# Jupiter_Ace_build026.net
KiCad netlist of a schematic drawn in EAGLE
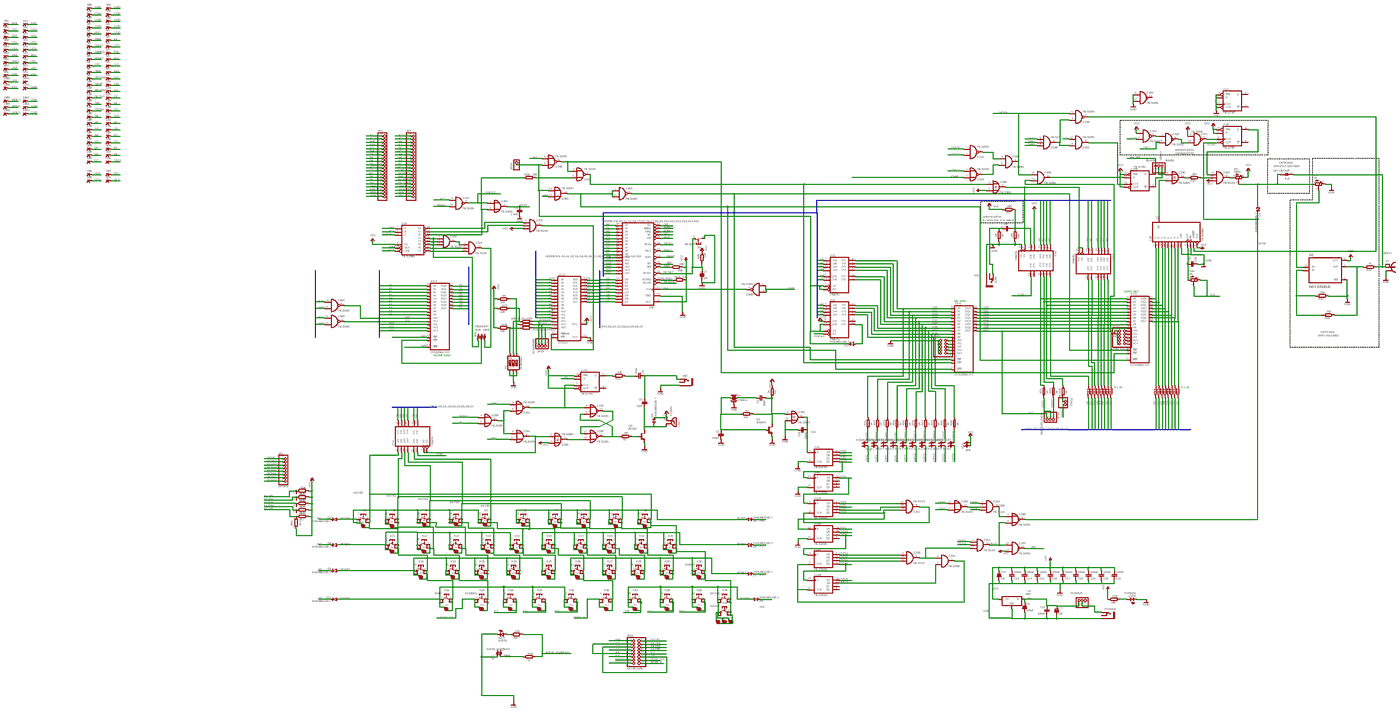
[diagram p0: schematic, sheet 1, overview]
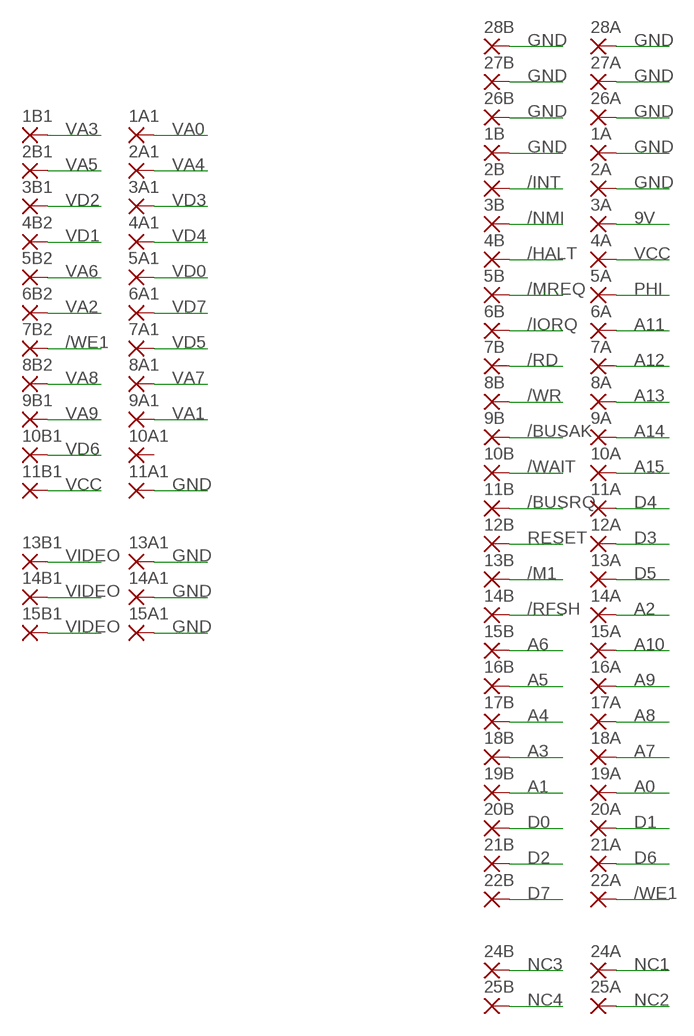
[diagram p1: schematic, sheet 1, part 1 of 4]
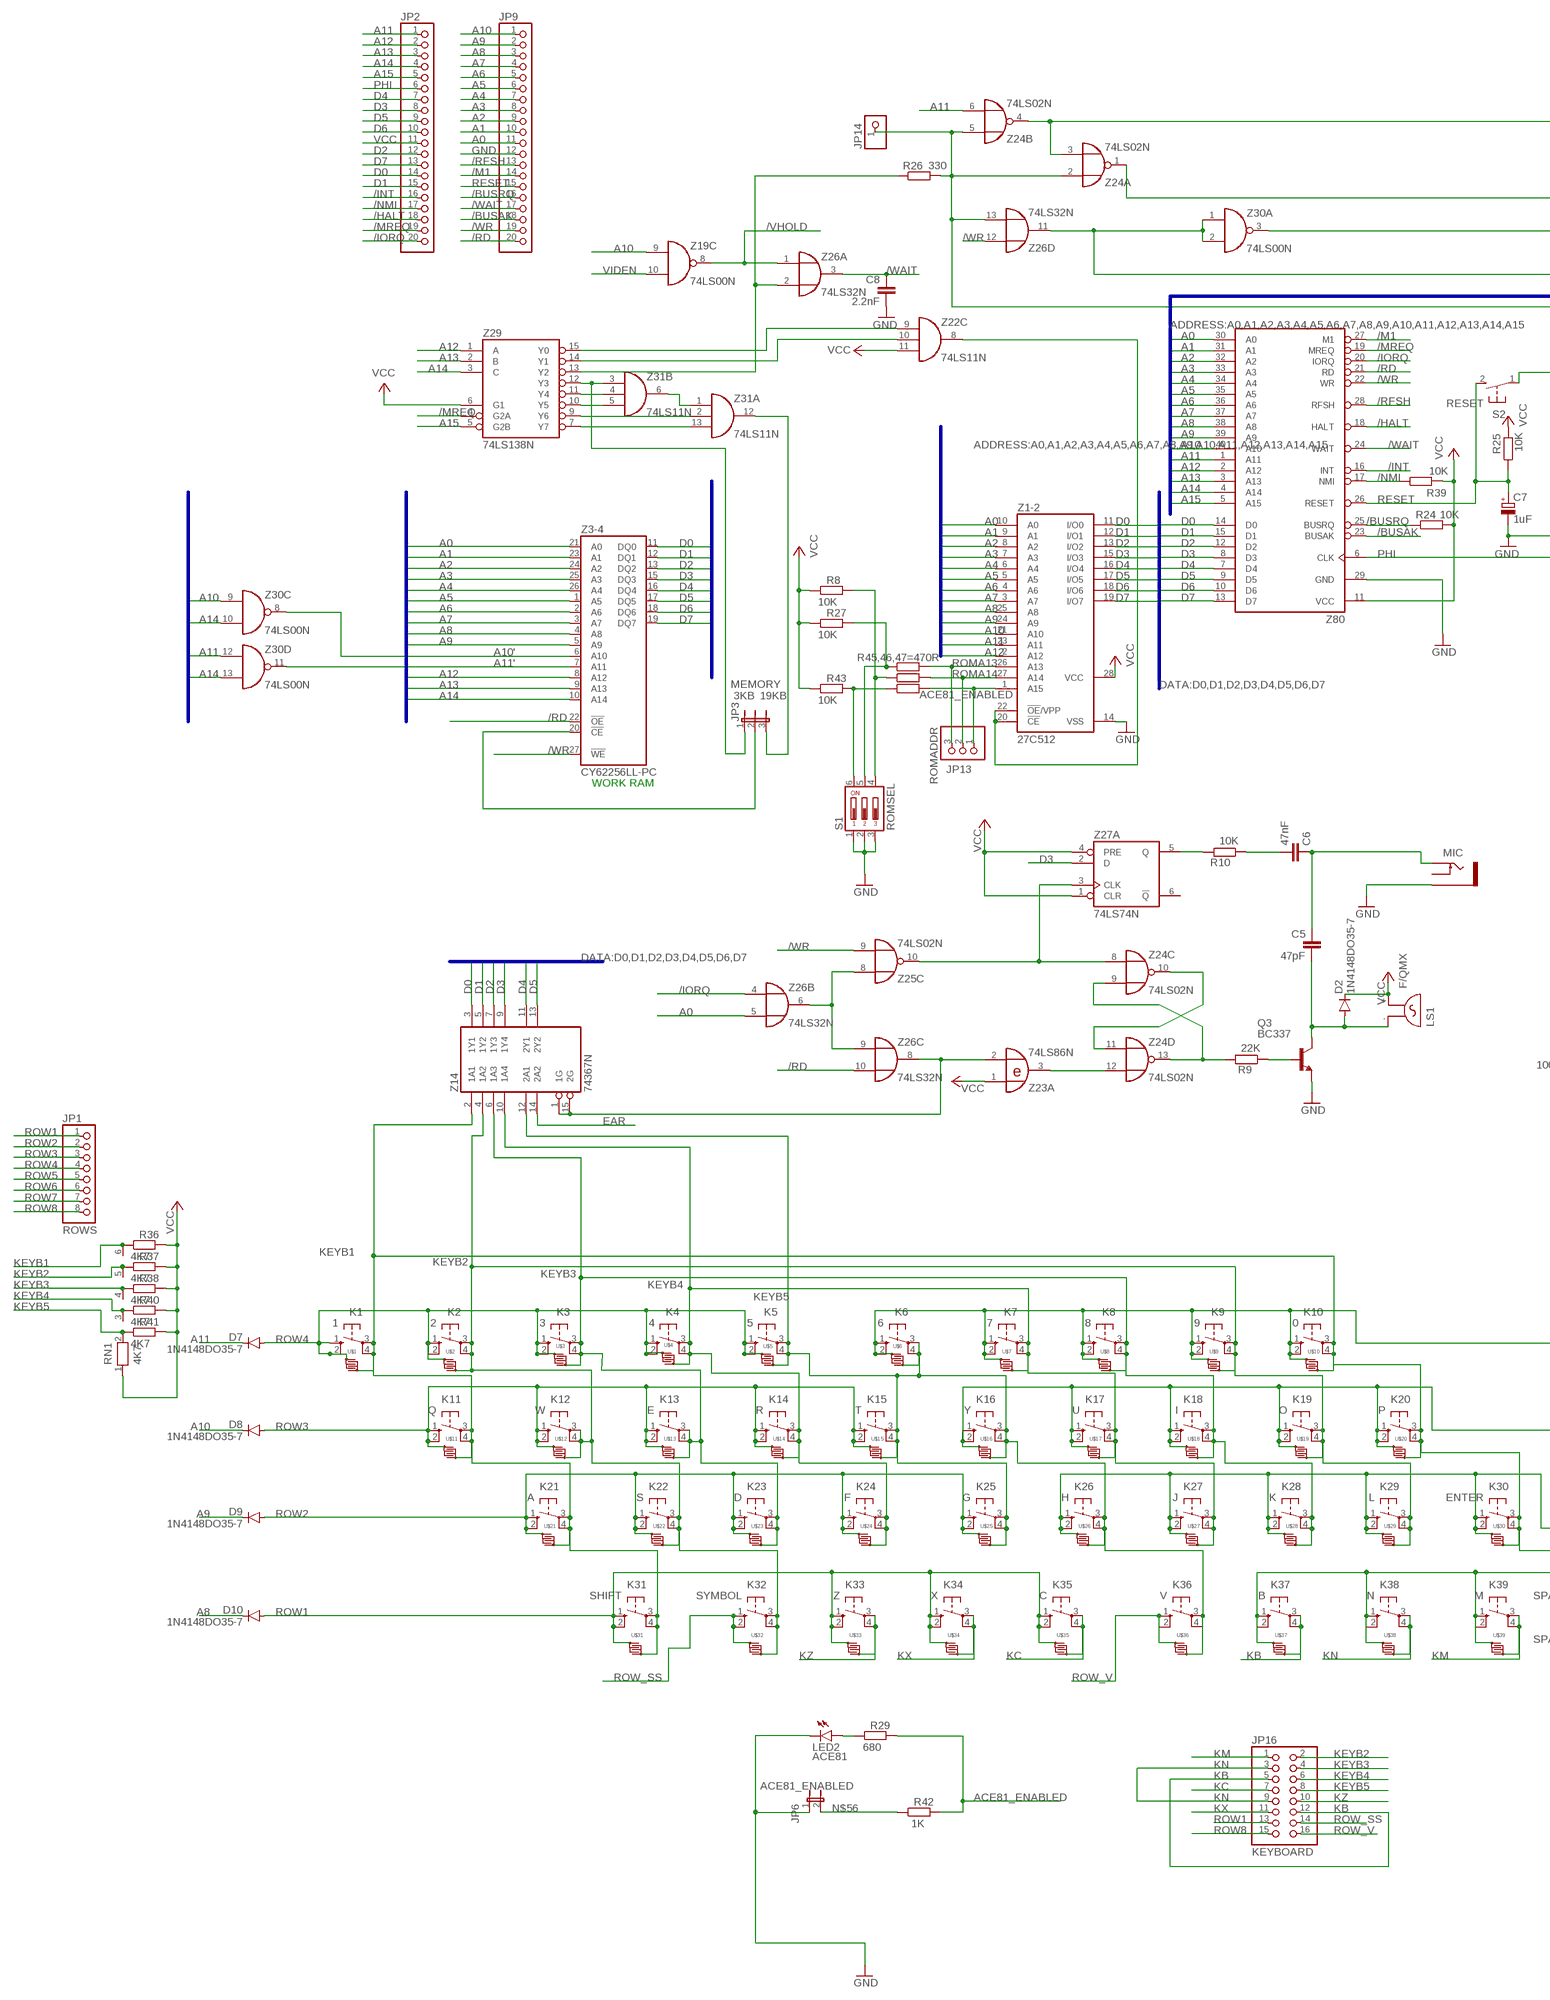
[diagram p2: schematic, sheet 1, part 2 of 4]
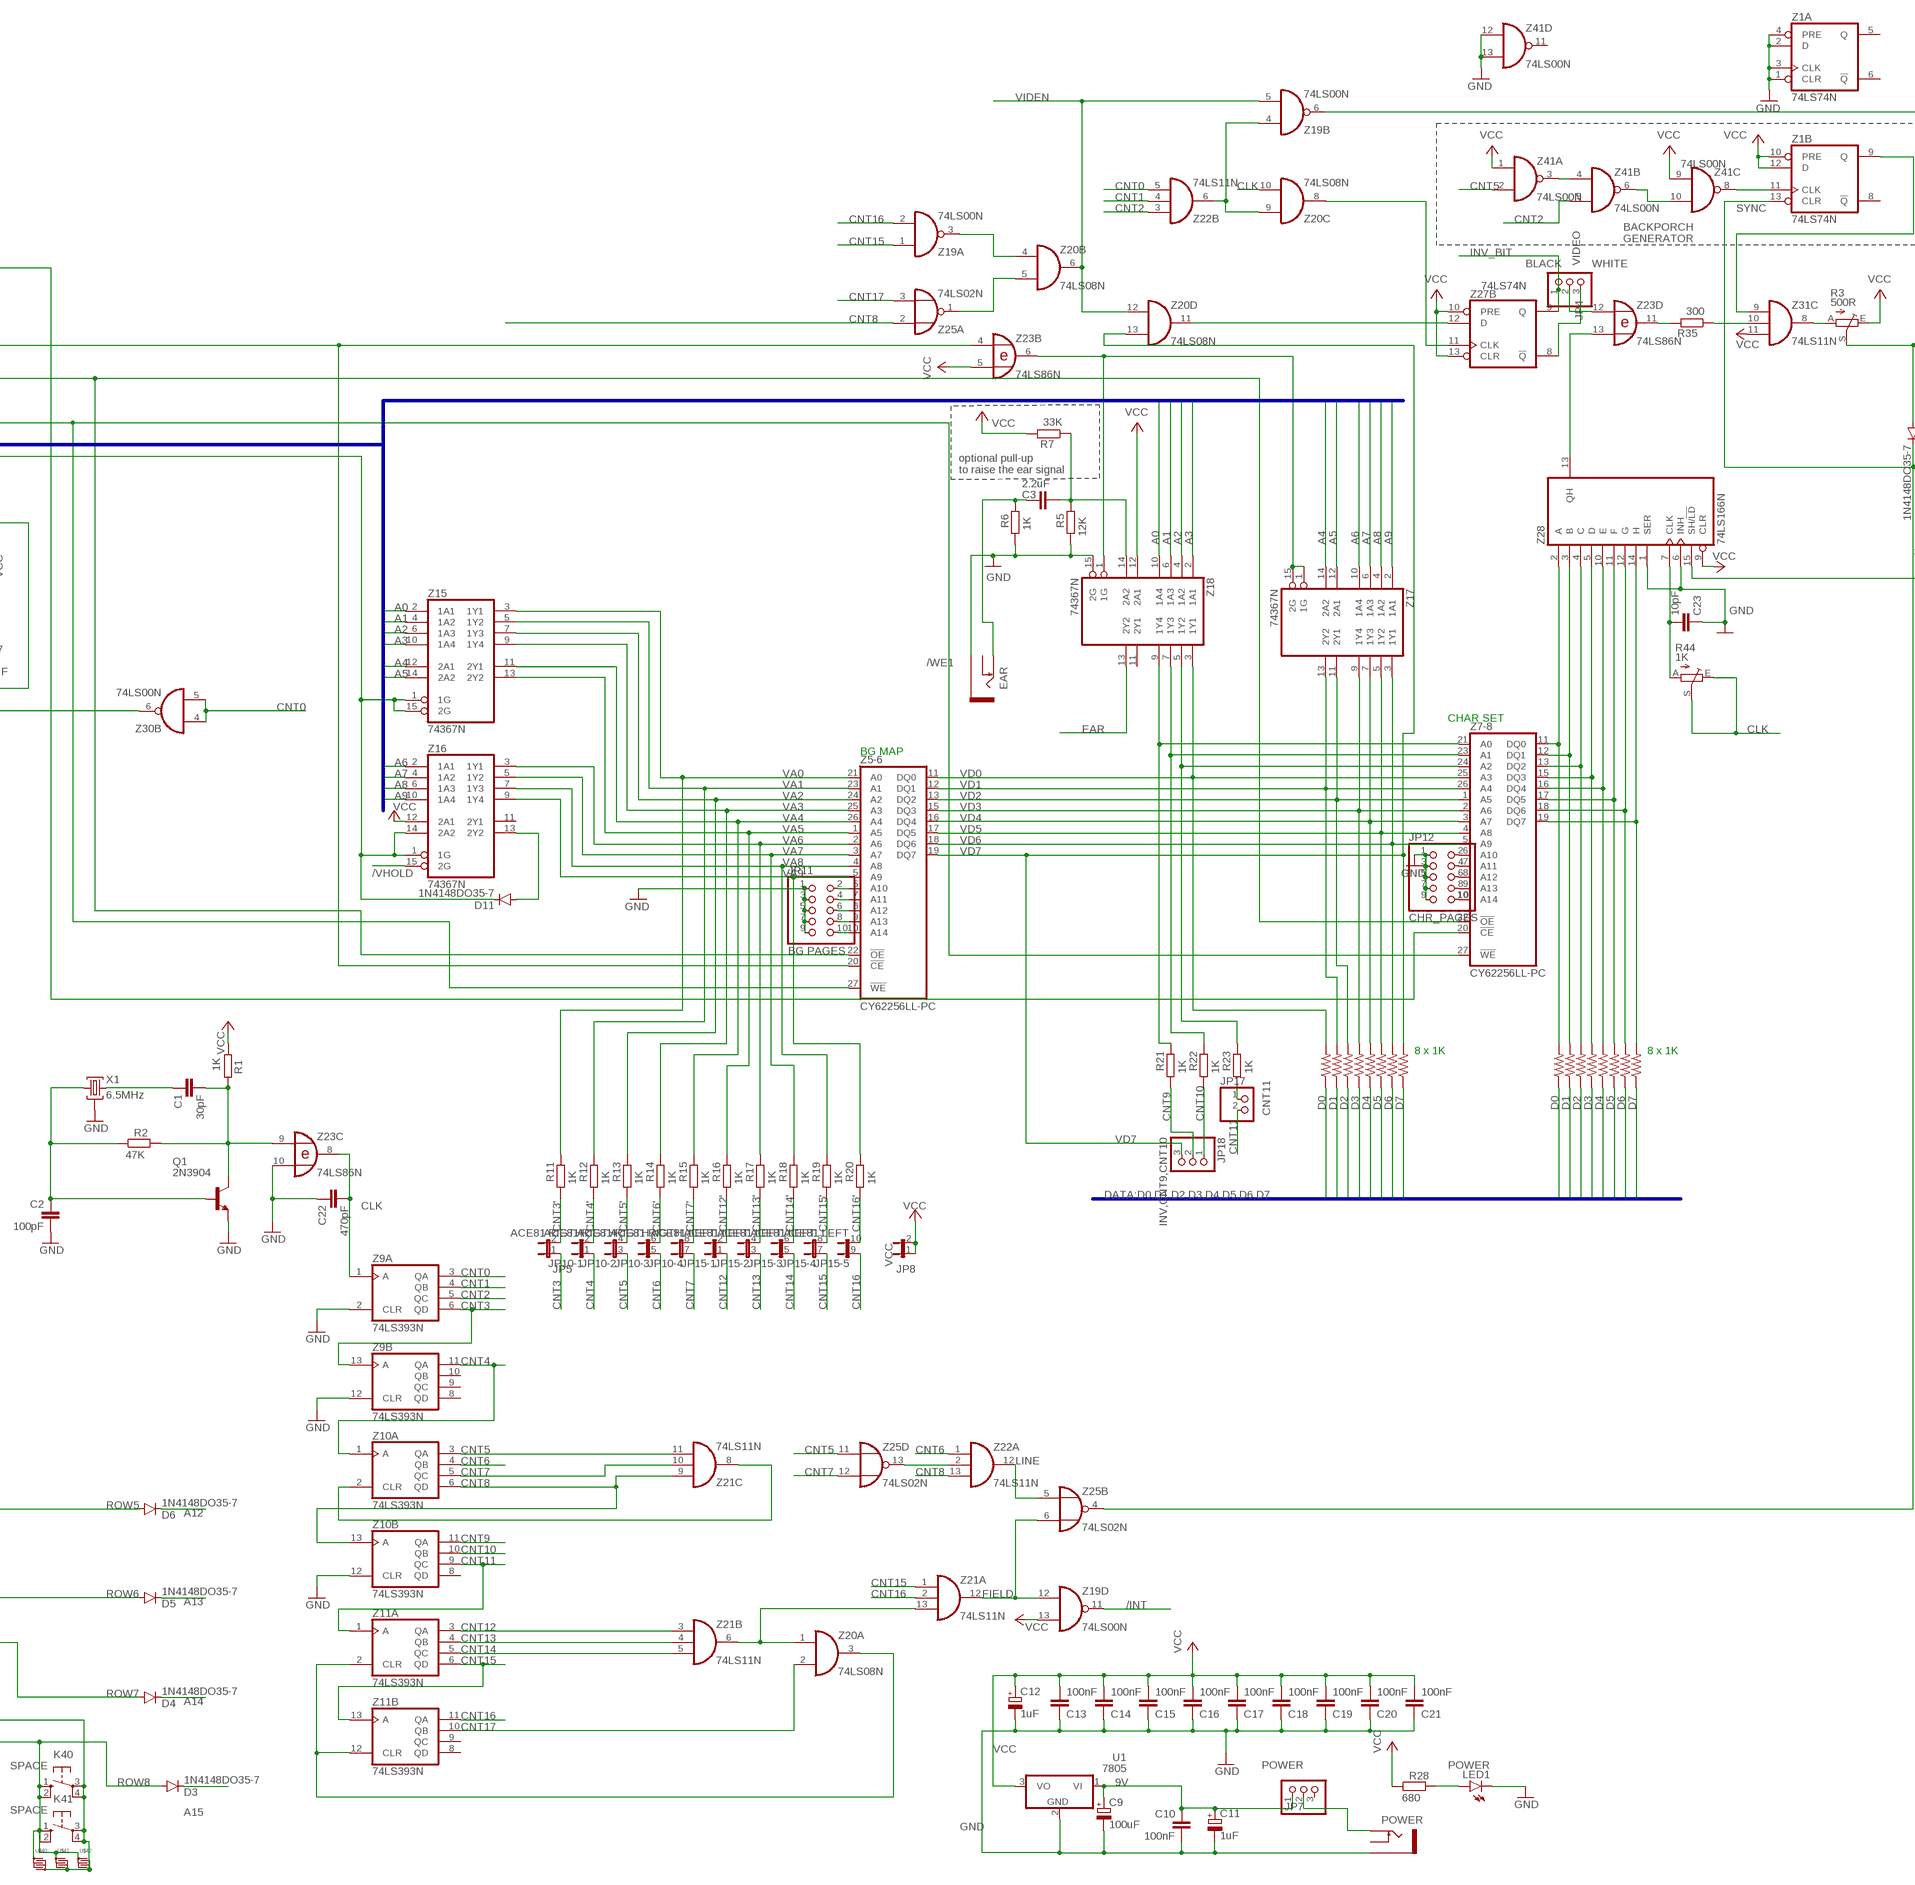
[diagram p3: schematic, sheet 1, part 3 of 4]
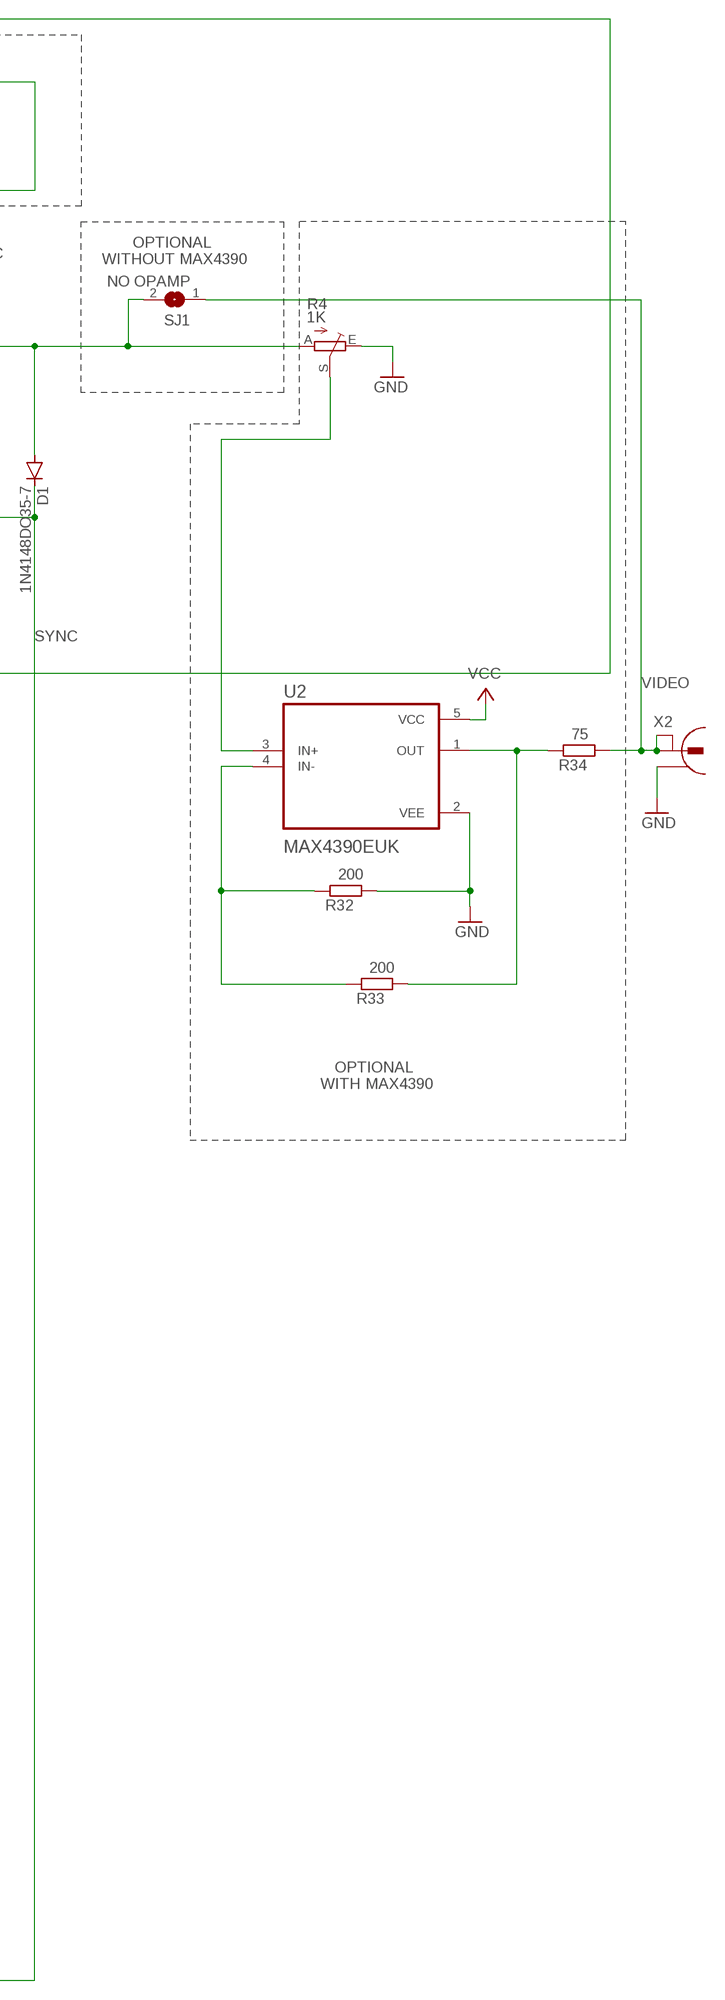
[diagram p4: schematic, sheet 1, part 4 of 4]

(export (version "E")
  (design (tool "Eeschema 10.0.6"))
  (components
    (comp (ref "1A")
      (value "SMD2EDGEPIN")
      (footprint "eagle-import:EDGEPIN")
      (libsource (lib "eagle-import") (part "SMD2EDGEPIN"))
    )
    (comp (ref "1A1")
      (value "SMD2EDGEPIN")
      (footprint "eagle-import:EDGEPIN")
      (libsource (lib "eagle-import") (part "SMD2EDGEPIN"))
    )
    (comp (ref "1B")
      (value "SMD2EDGEPIN")
      (footprint "eagle-import:EDGEPIN")
      (libsource (lib "eagle-import") (part "SMD2EDGEPIN"))
    )
    (comp (ref "1B1")
      (value "SMD2EDGEPIN")
      (footprint "eagle-import:EDGEPIN")
      (libsource (lib "eagle-import") (part "SMD2EDGEPIN"))
    )
    (comp (ref "2A")
      (value "SMD2EDGEPIN")
      (footprint "eagle-import:EDGEPIN")
      (libsource (lib "eagle-import") (part "SMD2EDGEPIN"))
    )
    (comp (ref "2A1")
      (value "SMD2EDGEPIN")
      (footprint "eagle-import:EDGEPIN")
      (libsource (lib "eagle-import") (part "SMD2EDGEPIN"))
    )
    (comp (ref "2B")
      (value "SMD2EDGEPIN")
      (footprint "eagle-import:EDGEPIN")
      (libsource (lib "eagle-import") (part "SMD2EDGEPIN"))
    )
    (comp (ref "2B1")
      (value "SMD2EDGEPIN")
      (footprint "eagle-import:EDGEPIN")
      (libsource (lib "eagle-import") (part "SMD2EDGEPIN"))
    )
    (comp (ref "3A")
      (value "SMD2EDGEPIN")
      (footprint "eagle-import:EDGEPIN")
      (libsource (lib "eagle-import") (part "SMD2EDGEPIN"))
    )
    (comp (ref "3A1")
      (value "SMD2EDGEPIN")
      (footprint "eagle-import:EDGEPIN")
      (libsource (lib "eagle-import") (part "SMD2EDGEPIN"))
    )
    (comp (ref "3B")
      (value "SMD2EDGEPIN")
      (footprint "eagle-import:EDGEPIN")
      (libsource (lib "eagle-import") (part "SMD2EDGEPIN"))
    )
    (comp (ref "3B1")
      (value "SMD2EDGEPIN")
      (footprint "eagle-import:EDGEPIN")
      (libsource (lib "eagle-import") (part "SMD2EDGEPIN"))
    )
    (comp (ref "4A")
      (value "SMD2EDGEPIN")
      (footprint "eagle-import:EDGEPIN")
      (libsource (lib "eagle-import") (part "SMD2EDGEPIN"))
    )
    (comp (ref "4A1")
      (value "SMD2EDGEPIN")
      (footprint "eagle-import:EDGEPIN")
      (libsource (lib "eagle-import") (part "SMD2EDGEPIN"))
    )
    (comp (ref "4B")
      (value "SMD2EDGEPIN")
      (footprint "eagle-import:EDGEPIN")
      (libsource (lib "eagle-import") (part "SMD2EDGEPIN"))
    )
    (comp (ref "4B2")
      (value "SMD2EDGEPIN")
      (footprint "eagle-import:EDGEPIN")
      (libsource (lib "eagle-import") (part "SMD2EDGEPIN"))
    )
    (comp (ref "5A")
      (value "SMD2EDGEPIN")
      (footprint "eagle-import:EDGEPIN")
      (libsource (lib "eagle-import") (part "SMD2EDGEPIN"))
    )
    (comp (ref "5A1")
      (value "SMD2EDGEPIN")
      (footprint "eagle-import:EDGEPIN")
      (libsource (lib "eagle-import") (part "SMD2EDGEPIN"))
    )
    (comp (ref "5B")
      (value "SMD2EDGEPIN")
      (footprint "eagle-import:EDGEPIN")
      (libsource (lib "eagle-import") (part "SMD2EDGEPIN"))
    )
    (comp (ref "5B2")
      (value "SMD2EDGEPIN")
      (footprint "eagle-import:EDGEPIN")
      (libsource (lib "eagle-import") (part "SMD2EDGEPIN"))
    )
    (comp (ref "6A")
      (value "SMD2EDGEPIN")
      (footprint "eagle-import:EDGEPIN")
      (libsource (lib "eagle-import") (part "SMD2EDGEPIN"))
    )
    (comp (ref "6A1")
      (value "SMD2EDGEPIN")
      (footprint "eagle-import:EDGEPIN")
      (libsource (lib "eagle-import") (part "SMD2EDGEPIN"))
    )
    (comp (ref "6B")
      (value "SMD2EDGEPIN")
      (footprint "eagle-import:EDGEPIN")
      (libsource (lib "eagle-import") (part "SMD2EDGEPIN"))
    )
    (comp (ref "6B2")
      (value "SMD2EDGEPIN")
      (footprint "eagle-import:EDGEPIN")
      (libsource (lib "eagle-import") (part "SMD2EDGEPIN"))
    )
    (comp (ref "7A")
      (value "SMD2EDGEPIN")
      (footprint "eagle-import:EDGEPIN")
      (libsource (lib "eagle-import") (part "SMD2EDGEPIN"))
    )
    (comp (ref "7A1")
      (value "SMD2EDGEPIN")
      (footprint "eagle-import:EDGEPIN")
      (libsource (lib "eagle-import") (part "SMD2EDGEPIN"))
    )
    (comp (ref "7B")
      (value "SMD2EDGEPIN")
      (footprint "eagle-import:EDGEPIN")
      (libsource (lib "eagle-import") (part "SMD2EDGEPIN"))
    )
    (comp (ref "7B2")
      (value "SMD2EDGEPIN")
      (footprint "eagle-import:EDGEPIN")
      (libsource (lib "eagle-import") (part "SMD2EDGEPIN"))
    )
    (comp (ref "8A")
      (value "SMD2EDGEPIN")
      (footprint "eagle-import:EDGEPIN")
      (libsource (lib "eagle-import") (part "SMD2EDGEPIN"))
    )
    (comp (ref "8A1")
      (value "SMD2EDGEPIN")
      (footprint "eagle-import:EDGEPIN")
      (libsource (lib "eagle-import") (part "SMD2EDGEPIN"))
    )
    (comp (ref "8B")
      (value "SMD2EDGEPIN")
      (footprint "eagle-import:EDGEPIN")
      (libsource (lib "eagle-import") (part "SMD2EDGEPIN"))
    )
    (comp (ref "8B2")
      (value "SMD2EDGEPIN")
      (footprint "eagle-import:EDGEPIN")
      (libsource (lib "eagle-import") (part "SMD2EDGEPIN"))
    )
    (comp (ref "9A")
      (value "SMD2EDGEPIN")
      (footprint "eagle-import:EDGEPIN")
      (libsource (lib "eagle-import") (part "SMD2EDGEPIN"))
    )
    (comp (ref "9A1")
      (value "SMD2EDGEPIN")
      (footprint "eagle-import:EDGEPIN")
      (libsource (lib "eagle-import") (part "SMD2EDGEPIN"))
    )
    (comp (ref "9B")
      (value "SMD2EDGEPIN")
      (footprint "eagle-import:EDGEPIN")
      (libsource (lib "eagle-import") (part "SMD2EDGEPIN"))
    )
    (comp (ref "9B1")
      (value "SMD2EDGEPIN")
      (footprint "eagle-import:EDGEPIN")
      (libsource (lib "eagle-import") (part "SMD2EDGEPIN"))
    )
    (comp (ref "10A")
      (value "SMD2EDGEPIN")
      (footprint "eagle-import:EDGEPIN")
      (libsource (lib "eagle-import") (part "SMD2EDGEPIN"))
    )
    (comp (ref "10A1")
      (value "SMD2EDGEPIN")
      (footprint "eagle-import:EDGEPIN")
      (libsource (lib "eagle-import") (part "SMD2EDGEPIN"))
    )
    (comp (ref "10B")
      (value "SMD2EDGEPIN")
      (footprint "eagle-import:EDGEPIN")
      (libsource (lib "eagle-import") (part "SMD2EDGEPIN"))
    )
    (comp (ref "10B1")
      (value "SMD2EDGEPIN")
      (footprint "eagle-import:EDGEPIN")
      (libsource (lib "eagle-import") (part "SMD2EDGEPIN"))
    )
    (comp (ref "11A")
      (value "SMD2EDGEPIN")
      (footprint "eagle-import:EDGEPIN")
      (libsource (lib "eagle-import") (part "SMD2EDGEPIN"))
    )
    (comp (ref "11A1")
      (value "SMD2EDGEPIN")
      (footprint "eagle-import:EDGEPIN")
      (libsource (lib "eagle-import") (part "SMD2EDGEPIN"))
    )
    (comp (ref "11B")
      (value "SMD2EDGEPIN")
      (footprint "eagle-import:EDGEPIN")
      (libsource (lib "eagle-import") (part "SMD2EDGEPIN"))
    )
    (comp (ref "11B1")
      (value "SMD2EDGEPIN")
      (footprint "eagle-import:EDGEPIN")
      (libsource (lib "eagle-import") (part "SMD2EDGEPIN"))
    )
    (comp (ref "12A")
      (value "SMD2EDGEPIN")
      (footprint "eagle-import:EDGEPIN")
      (libsource (lib "eagle-import") (part "SMD2EDGEPIN"))
    )
    (comp (ref "12B")
      (value "SMD2EDGEPIN")
      (footprint "eagle-import:EDGEPIN")
      (libsource (lib "eagle-import") (part "SMD2EDGEPIN"))
    )
    (comp (ref "13A")
      (value "SMD2EDGEPIN")
      (footprint "eagle-import:EDGEPIN")
      (libsource (lib "eagle-import") (part "SMD2EDGEPIN"))
    )
    (comp (ref "13A1")
      (value "SMD2EDGEPIN")
      (footprint "eagle-import:EDGEPIN")
      (libsource (lib "eagle-import") (part "SMD2EDGEPIN"))
    )
    (comp (ref "13B")
      (value "SMD2EDGEPIN")
      (footprint "eagle-import:EDGEPIN")
      (libsource (lib "eagle-import") (part "SMD2EDGEPIN"))
    )
    (comp (ref "13B1")
      (value "SMD2EDGEPIN")
      (footprint "eagle-import:EDGEPIN")
      (libsource (lib "eagle-import") (part "SMD2EDGEPIN"))
    )
    (comp (ref "14A")
      (value "SMD2EDGEPIN")
      (footprint "eagle-import:EDGEPIN")
      (libsource (lib "eagle-import") (part "SMD2EDGEPIN"))
    )
    (comp (ref "14A1")
      (value "SMD2EDGEPIN")
      (footprint "eagle-import:EDGEPIN")
      (libsource (lib "eagle-import") (part "SMD2EDGEPIN"))
    )
    (comp (ref "14B")
      (value "SMD2EDGEPIN")
      (footprint "eagle-import:EDGEPIN")
      (libsource (lib "eagle-import") (part "SMD2EDGEPIN"))
    )
    (comp (ref "14B1")
      (value "SMD2EDGEPIN")
      (footprint "eagle-import:EDGEPIN")
      (libsource (lib "eagle-import") (part "SMD2EDGEPIN"))
    )
    (comp (ref "15A")
      (value "SMD2EDGEPIN")
      (footprint "eagle-import:EDGEPIN")
      (libsource (lib "eagle-import") (part "SMD2EDGEPIN"))
    )
    (comp (ref "15A1")
      (value "SMD2EDGEPIN")
      (footprint "eagle-import:EDGEPIN")
      (libsource (lib "eagle-import") (part "SMD2EDGEPIN"))
    )
    (comp (ref "15B")
      (value "SMD2EDGEPIN")
      (footprint "eagle-import:EDGEPIN")
      (libsource (lib "eagle-import") (part "SMD2EDGEPIN"))
    )
    (comp (ref "15B1")
      (value "SMD2EDGEPIN")
      (footprint "eagle-import:EDGEPIN")
      (libsource (lib "eagle-import") (part "SMD2EDGEPIN"))
    )
    (comp (ref "16A")
      (value "SMD2EDGEPIN")
      (footprint "eagle-import:EDGEPIN")
      (libsource (lib "eagle-import") (part "SMD2EDGEPIN"))
    )
    (comp (ref "16B")
      (value "SMD2EDGEPIN")
      (footprint "eagle-import:EDGEPIN")
      (libsource (lib "eagle-import") (part "SMD2EDGEPIN"))
    )
    (comp (ref "17A")
      (value "SMD2EDGEPIN")
      (footprint "eagle-import:EDGEPIN")
      (libsource (lib "eagle-import") (part "SMD2EDGEPIN"))
    )
    (comp (ref "17B")
      (value "SMD2EDGEPIN")
      (footprint "eagle-import:EDGEPIN")
      (libsource (lib "eagle-import") (part "SMD2EDGEPIN"))
    )
    (comp (ref "18A")
      (value "SMD2EDGEPIN")
      (footprint "eagle-import:EDGEPIN")
      (libsource (lib "eagle-import") (part "SMD2EDGEPIN"))
    )
    (comp (ref "18B")
      (value "SMD2EDGEPIN")
      (footprint "eagle-import:EDGEPIN")
      (libsource (lib "eagle-import") (part "SMD2EDGEPIN"))
    )
    (comp (ref "19A")
      (value "SMD2EDGEPIN")
      (footprint "eagle-import:EDGEPIN")
      (libsource (lib "eagle-import") (part "SMD2EDGEPIN"))
    )
    (comp (ref "19B")
      (value "SMD2EDGEPIN")
      (footprint "eagle-import:EDGEPIN")
      (libsource (lib "eagle-import") (part "SMD2EDGEPIN"))
    )
    (comp (ref "20A")
      (value "SMD2EDGEPIN")
      (footprint "eagle-import:EDGEPIN")
      (libsource (lib "eagle-import") (part "SMD2EDGEPIN"))
    )
    (comp (ref "20B")
      (value "SMD2EDGEPIN")
      (footprint "eagle-import:EDGEPIN")
      (libsource (lib "eagle-import") (part "SMD2EDGEPIN"))
    )
    (comp (ref "21A")
      (value "SMD2EDGEPIN")
      (footprint "eagle-import:EDGEPIN")
      (libsource (lib "eagle-import") (part "SMD2EDGEPIN"))
    )
    (comp (ref "21B")
      (value "SMD2EDGEPIN")
      (footprint "eagle-import:EDGEPIN")
      (libsource (lib "eagle-import") (part "SMD2EDGEPIN"))
    )
    (comp (ref "22A")
      (value "SMD2EDGEPIN")
      (footprint "eagle-import:EDGEPIN")
      (libsource (lib "eagle-import") (part "SMD2EDGEPIN"))
    )
    (comp (ref "22B")
      (value "SMD2EDGEPIN")
      (footprint "eagle-import:EDGEPIN")
      (libsource (lib "eagle-import") (part "SMD2EDGEPIN"))
    )
    (comp (ref "24A")
      (value "SMD2EDGEPIN")
      (footprint "eagle-import:EDGEPIN")
      (libsource (lib "eagle-import") (part "SMD2EDGEPIN"))
    )
    (comp (ref "24B")
      (value "SMD2EDGEPIN")
      (footprint "eagle-import:EDGEPIN")
      (libsource (lib "eagle-import") (part "SMD2EDGEPIN"))
    )
    (comp (ref "25A")
      (value "SMD2EDGEPIN")
      (footprint "eagle-import:EDGEPIN")
      (libsource (lib "eagle-import") (part "SMD2EDGEPIN"))
    )
    (comp (ref "25B")
      (value "SMD2EDGEPIN")
      (footprint "eagle-import:EDGEPIN")
      (libsource (lib "eagle-import") (part "SMD2EDGEPIN"))
    )
    (comp (ref "26A")
      (value "SMD2EDGEPIN")
      (footprint "eagle-import:EDGEPIN")
      (libsource (lib "eagle-import") (part "SMD2EDGEPIN"))
    )
    (comp (ref "26B")
      (value "SMD2EDGEPIN")
      (footprint "eagle-import:EDGEPIN")
      (libsource (lib "eagle-import") (part "SMD2EDGEPIN"))
    )
    (comp (ref "27A")
      (value "SMD2EDGEPIN")
      (footprint "eagle-import:EDGEPIN")
      (libsource (lib "eagle-import") (part "SMD2EDGEPIN"))
    )
    (comp (ref "27B")
      (value "SMD2EDGEPIN")
      (footprint "eagle-import:EDGEPIN")
      (libsource (lib "eagle-import") (part "SMD2EDGEPIN"))
    )
    (comp (ref "28A")
      (value "SMD2EDGEPIN")
      (footprint "eagle-import:EDGEPIN")
      (libsource (lib "eagle-import") (part "SMD2EDGEPIN"))
    )
    (comp (ref "28B")
      (value "SMD2EDGEPIN")
      (footprint "eagle-import:EDGEPIN")
      (libsource (lib "eagle-import") (part "SMD2EDGEPIN"))
    )
    (comp (ref "C1")
      (value "30pF")
      (footprint "eagle-import:C025-025X050")
      (libsource (lib "eagle-import") (part "C-EU025-025X050"))
    )
    (comp (ref "C2")
      (value "100pF")
      (footprint "eagle-import:C025-025X050")
      (libsource (lib "eagle-import") (part "C-EU025-025X050"))
    )
    (comp (ref "C3")
      (value "2.2uF")
      (footprint "eagle-import:C025-025X050")
      (libsource (lib "eagle-import") (part "C-EU025-025X050"))
    )
    (comp (ref "C5")
      (value "47pF")
      (footprint "eagle-import:C025-025X050")
      (libsource (lib "eagle-import") (part "C-EU025-025X050"))
    )
    (comp (ref "C6")
      (value "47nF")
      (footprint "eagle-import:C025-025X050")
      (libsource (lib "eagle-import") (part "C-EU025-025X050"))
    )
    (comp (ref "C7")
      (value "1uF")
      (footprint "eagle-import:E1,8-4")
      (libsource (lib "eagle-import") (part "CPOL-EUE1.8-4"))
    )
    (comp (ref "C8")
      (value "2.2nF")
      (footprint "eagle-import:C025-025X050")
      (libsource (lib "eagle-import") (part "C-EU025-025X050"))
    )
    (comp (ref "C9")
      (value "100uF")
      (footprint "eagle-import:E1,8-4")
      (libsource (lib "eagle-import") (part "CPOL-EUE1.8-4"))
    )
    (comp (ref "C10")
      (value "100nF")
      (footprint "eagle-import:C025-025X050")
      (libsource (lib "eagle-import") (part "C-EU025-025X050"))
    )
    (comp (ref "C11")
      (value "1uF")
      (footprint "eagle-import:E1,8-4")
      (libsource (lib "eagle-import") (part "CPOL-EUE1.8-4"))
    )
    (comp (ref "C12")
      (value "1uF")
      (footprint "eagle-import:E1,8-4")
      (libsource (lib "eagle-import") (part "CPOL-EUE1.8-4"))
    )
    (comp (ref "C13")
      (value "100nF")
      (footprint "eagle-import:C025-025X050")
      (libsource (lib "eagle-import") (part "C-EU025-025X050"))
    )
    (comp (ref "C14")
      (value "100nF")
      (footprint "eagle-import:C025-025X050")
      (libsource (lib "eagle-import") (part "C-EU025-025X050"))
    )
    (comp (ref "C15")
      (value "100nF")
      (footprint "eagle-import:C025-025X050")
      (libsource (lib "eagle-import") (part "C-EU025-025X050"))
    )
    (comp (ref "C16")
      (value "100nF")
      (footprint "eagle-import:C025-025X050")
      (libsource (lib "eagle-import") (part "C-EU025-025X050"))
    )
    (comp (ref "C17")
      (value "100nF")
      (footprint "eagle-import:C025-025X050")
      (libsource (lib "eagle-import") (part "C-EU025-025X050"))
    )
    (comp (ref "C18")
      (value "100nF")
      (footprint "eagle-import:C025-025X050")
      (libsource (lib "eagle-import") (part "C-EU025-025X050"))
    )
    (comp (ref "C19")
      (value "100nF")
      (footprint "eagle-import:C025-025X050")
      (libsource (lib "eagle-import") (part "C-EU025-025X050"))
    )
    (comp (ref "C20")
      (value "100nF")
      (footprint "eagle-import:C025-025X050")
      (libsource (lib "eagle-import") (part "C-EU025-025X050"))
    )
    (comp (ref "C21")
      (value "100nF")
      (footprint "eagle-import:C025-025X050")
      (libsource (lib "eagle-import") (part "C-EU025-025X050"))
    )
    (comp (ref "C22")
      (value "470pF")
      (footprint "eagle-import:C025-025X050")
      (libsource (lib "eagle-import") (part "C-EU025-025X050"))
    )
    (comp (ref "C23")
      (value "10pF")
      (footprint "eagle-import:C025-025X050")
      (libsource (lib "eagle-import") (part "C-EU025-025X050"))
    )
    (comp (ref "D1")
      (value "1N4148DO35-7")
      (footprint "eagle-import:DO35-7")
      (libsource (lib "eagle-import") (part "1N4148DO35-7"))
    )
    (comp (ref "D2")
      (value "1N4148DO35-7")
      (footprint "eagle-import:DO35-7")
      (libsource (lib "eagle-import") (part "1N4148DO35-7"))
    )
    (comp (ref "D3")
      (value "1N4148DO35-7")
      (footprint "eagle-import:DO35-7")
      (libsource (lib "eagle-import") (part "1N4148DO35-7"))
    )
    (comp (ref "D4")
      (value "1N4148DO35-7")
      (footprint "eagle-import:DO35-7")
      (libsource (lib "eagle-import") (part "1N4148DO35-7"))
    )
    (comp (ref "D5")
      (value "1N4148DO35-7")
      (footprint "eagle-import:DO35-7")
      (libsource (lib "eagle-import") (part "1N4148DO35-7"))
    )
    (comp (ref "D6")
      (value "1N4148DO35-7")
      (footprint "eagle-import:DO35-7")
      (libsource (lib "eagle-import") (part "1N4148DO35-7"))
    )
    (comp (ref "D7")
      (value "1N4148DO35-7")
      (footprint "eagle-import:DO35-7")
      (libsource (lib "eagle-import") (part "1N4148DO35-7"))
    )
    (comp (ref "D8")
      (value "1N4148DO35-7")
      (footprint "eagle-import:DO35-7")
      (libsource (lib "eagle-import") (part "1N4148DO35-7"))
    )
    (comp (ref "D9")
      (value "1N4148DO35-7")
      (footprint "eagle-import:DO35-7")
      (libsource (lib "eagle-import") (part "1N4148DO35-7"))
    )
    (comp (ref "D10")
      (value "1N4148DO35-7")
      (footprint "eagle-import:DO35-7")
      (libsource (lib "eagle-import") (part "1N4148DO35-7"))
    )
    (comp (ref "D11")
      (value "1N4148DO35-7")
      (footprint "eagle-import:DO35-7")
      (libsource (lib "eagle-import") (part "1N4148DO35-7"))
    )
    (comp (ref "EAR")
      (value "PJ302M")
      (footprint "eagle-import:PJ302M")
      (libsource (lib "eagle-import") (part "PJ302M"))
    )
    (comp (ref "JP1")
      (value "ROWS")
      (footprint "eagle-import:1X08")
      (libsource (lib "eagle-import") (part "PINHD-1X8"))
    )
    (comp (ref "JP2")
      (value "PINHD-1X20")
      (footprint "eagle-import:1X20")
      (libsource (lib "eagle-import") (part "PINHD-1X20"))
    )
    (comp (ref "JP3")
      (value "MEMORY")
      (footprint "eagle-import:JP2")
      (libsource (lib "eagle-import") (part "JP2E"))
    )
    (comp (ref "JP4")
      (value "VIDEO")
      (footprint "eagle-import:1X03")
      (libsource (lib "eagle-import") (part "PINHD-1X3"))
    )
    (comp (ref "JP5")
      (value "JP1E1Q")
      (footprint "eagle-import:JP1Q")
      (libsource (lib "eagle-import") (part "JP1E1Q"))
    )
    (comp (ref "JP6")
      (value "ACE81_ENABLED")
      (footprint "eagle-import:JP1Q")
      (libsource (lib "eagle-import") (part "JP1E1Q"))
    )
    (comp (ref "JP7")
      (value "POWER")
      (footprint "eagle-import:1X03")
      (libsource (lib "eagle-import") (part "PINHD-1X3"))
    )
    (comp (ref "JP8")
      (value "VCC")
      (footprint "eagle-import:JP1Q")
      (libsource (lib "eagle-import") (part "JP1E1Q"))
    )
    (comp (ref "JP9")
      (value "PINHD-1X20")
      (footprint "eagle-import:1X20")
      (libsource (lib "eagle-import") (part "PINHD-1X20"))
    )
    (comp (ref "JP10")
      (value "ACE81 RIGTH")
      (footprint "eagle-import:JP4Q")
      (libsource (lib "eagle-import") (part "JP4QE"))
    )
    (comp (ref "JP11")
      (value "BG PAGES")
      (footprint "eagle-import:2X05")
      (libsource (lib "eagle-import") (part "PINHD-2X5"))
    )
    (comp (ref "JP12")
      (value "CHR_PAGES")
      (footprint "eagle-import:2X05")
      (libsource (lib "eagle-import") (part "PINHD-2X5"))
    )
    (comp (ref "JP13")
      (value "ROMADDR")
      (footprint "eagle-import:1X03")
      (libsource (lib "eagle-import") (part "PINHD-1X3"))
    )
    (comp (ref "JP14")
      (value "PINHD-1X1")
      (footprint "eagle-import:1X01")
      (libsource (lib "eagle-import") (part "PINHD-1X1"))
    )
    (comp (ref "JP15")
      (value "ACE81 LEFT")
      (footprint "eagle-import:JP5Q")
      (libsource (lib "eagle-import") (part "JP5QE"))
    )
    (comp (ref "JP16")
      (value "KEYBOARD")
      (footprint "eagle-import:2X08")
      (libsource (lib "eagle-import") (part "PINHD-2X8"))
    )
    (comp (ref "JP17")
      (value "CNT11")
      (footprint "eagle-import:1X02")
      (libsource (lib "eagle-import") (part "PINHD-1X2"))
    )
    (comp (ref "JP18")
      (value "INV,CNT9,CNT10")
      (footprint "eagle-import:1X03")
      (libsource (lib "eagle-import") (part "pinhead_44166543_PINHD-1X3"))
    )
    (comp (ref "K1")
      (value "1")
      (footprint "eagle-import:B3F-40XXNOHOLE")
      (libsource (lib "eagle-import") (part "40-XXNOHOLES"))
    )
    (comp (ref "K2")
      (value "2")
      (footprint "eagle-import:B3F-40XXNOHOLE")
      (libsource (lib "eagle-import") (part "40-XXNOHOLES"))
    )
    (comp (ref "K3")
      (value "3")
      (footprint "eagle-import:B3F-40XXNOHOLE")
      (libsource (lib "eagle-import") (part "40-XXNOHOLES"))
    )
    (comp (ref "K4")
      (value "4")
      (footprint "eagle-import:B3F-40XXNOHOLE")
      (libsource (lib "eagle-import") (part "40-XXNOHOLES"))
    )
    (comp (ref "K5")
      (value "5")
      (footprint "eagle-import:B3F-40XXNOHOLE")
      (libsource (lib "eagle-import") (part "40-XXNOHOLES"))
    )
    (comp (ref "K6")
      (value "6")
      (footprint "eagle-import:B3F-40XXNOHOLE")
      (libsource (lib "eagle-import") (part "40-XXNOHOLES"))
    )
    (comp (ref "K7")
      (value "7")
      (footprint "eagle-import:B3F-40XXNOHOLE")
      (libsource (lib "eagle-import") (part "40-XXNOHOLES"))
    )
    (comp (ref "K8")
      (value "8")
      (footprint "eagle-import:B3F-40XXNOHOLE")
      (libsource (lib "eagle-import") (part "40-XXNOHOLES"))
    )
    (comp (ref "K9")
      (value "9")
      (footprint "eagle-import:B3F-40XXNOHOLE")
      (libsource (lib "eagle-import") (part "40-XXNOHOLES"))
    )
    (comp (ref "K10")
      (value "0")
      (footprint "eagle-import:B3F-40XXNOHOLE")
      (libsource (lib "eagle-import") (part "40-XXNOHOLES"))
    )
    (comp (ref "K11")
      (value "Q")
      (footprint "eagle-import:B3F-40XXNOHOLE")
      (libsource (lib "eagle-import") (part "40-XXNOHOLES"))
    )
    (comp (ref "K12")
      (value "W")
      (footprint "eagle-import:B3F-40XXNOHOLE")
      (libsource (lib "eagle-import") (part "40-XXNOHOLES"))
    )
    (comp (ref "K13")
      (value "E")
      (footprint "eagle-import:B3F-40XXNOHOLE")
      (libsource (lib "eagle-import") (part "40-XXNOHOLES"))
    )
    (comp (ref "K14")
      (value "R")
      (footprint "eagle-import:B3F-40XXNOHOLE")
      (libsource (lib "eagle-import") (part "40-XXNOHOLES"))
    )
    (comp (ref "K15")
      (value "T")
      (footprint "eagle-import:B3F-40XXNOHOLE")
      (libsource (lib "eagle-import") (part "40-XXNOHOLES"))
    )
    (comp (ref "K16")
      (value "Y")
      (footprint "eagle-import:B3F-40XXNOHOLE")
      (libsource (lib "eagle-import") (part "40-XXNOHOLES"))
    )
    (comp (ref "K17")
      (value "U")
      (footprint "eagle-import:B3F-40XXNOHOLE")
      (libsource (lib "eagle-import") (part "40-XXNOHOLES"))
    )
    (comp (ref "K18")
      (value "I")
      (footprint "eagle-import:B3F-40XXNOHOLE")
      (libsource (lib "eagle-import") (part "40-XXNOHOLES"))
    )
    (comp (ref "K19")
      (value "O")
      (footprint "eagle-import:B3F-40XXNOHOLE")
      (libsource (lib "eagle-import") (part "40-XXNOHOLES"))
    )
    (comp (ref "K20")
      (value "P")
      (footprint "eagle-import:B3F-40XXNOHOLE")
      (libsource (lib "eagle-import") (part "40-XXNOHOLES"))
    )
    (comp (ref "K21")
      (value "A")
      (footprint "eagle-import:B3F-40XXNOHOLE")
      (libsource (lib "eagle-import") (part "40-XXNOHOLES"))
    )
    (comp (ref "K22")
      (value "S")
      (footprint "eagle-import:B3F-40XXNOHOLE")
      (libsource (lib "eagle-import") (part "40-XXNOHOLES"))
    )
    (comp (ref "K23")
      (value "D")
      (footprint "eagle-import:B3F-40XXNOHOLE")
      (libsource (lib "eagle-import") (part "40-XXNOHOLES"))
    )
    (comp (ref "K24")
      (value "F")
      (footprint "eagle-import:B3F-40XXNOHOLE")
      (libsource (lib "eagle-import") (part "40-XXNOHOLES"))
    )
    (comp (ref "K25")
      (value "G")
      (footprint "eagle-import:B3F-40XXNOHOLE")
      (libsource (lib "eagle-import") (part "40-XXNOHOLES"))
    )
    (comp (ref "K26")
      (value "H")
      (footprint "eagle-import:B3F-40XXNOHOLE")
      (libsource (lib "eagle-import") (part "40-XXNOHOLES"))
    )
    (comp (ref "K27")
      (value "J")
      (footprint "eagle-import:B3F-40XXNOHOLE")
      (libsource (lib "eagle-import") (part "40-XXNOHOLES"))
    )
    (comp (ref "K28")
      (value "K")
      (footprint "eagle-import:B3F-40XXNOHOLE")
      (libsource (lib "eagle-import") (part "40-XXNOHOLES"))
    )
    (comp (ref "K29")
      (value "L")
      (footprint "eagle-import:B3F-40XXNOHOLE")
      (libsource (lib "eagle-import") (part "40-XXNOHOLES"))
    )
    (comp (ref "K30")
      (value "ENTER")
      (footprint "eagle-import:B3F-40XXNOHOLE")
      (libsource (lib "eagle-import") (part "40-XXNOHOLES"))
    )
    (comp (ref "K31")
      (value "SHIFT")
      (footprint "eagle-import:B3F-40XXNOHOLE")
      (libsource (lib "eagle-import") (part "40-XXNOHOLES"))
    )
    (comp (ref "K32")
      (value "SYMBOL")
      (footprint "eagle-import:B3F-40XXNOHOLE")
      (libsource (lib "eagle-import") (part "40-XXNOHOLES"))
    )
    (comp (ref "K33")
      (value "Z")
      (footprint "eagle-import:B3F-40XXNOHOLE")
      (libsource (lib "eagle-import") (part "40-XXNOHOLES"))
    )
    (comp (ref "K34")
      (value "X")
      (footprint "eagle-import:B3F-40XXNOHOLE")
      (libsource (lib "eagle-import") (part "40-XXNOHOLES"))
    )
    (comp (ref "K35")
      (value "C")
      (footprint "eagle-import:B3F-40XXNOHOLE")
      (libsource (lib "eagle-import") (part "40-XXNOHOLES"))
    )
    (comp (ref "K36")
      (value "V")
      (footprint "eagle-import:B3F-40XXNOHOLE")
      (libsource (lib "eagle-import") (part "40-XXNOHOLES"))
    )
    (comp (ref "K37")
      (value "B")
      (footprint "eagle-import:B3F-40XXNOHOLE")
      (libsource (lib "eagle-import") (part "40-XXNOHOLES"))
    )
    (comp (ref "K38")
      (value "N")
      (footprint "eagle-import:B3F-40XXNOHOLE")
      (libsource (lib "eagle-import") (part "40-XXNOHOLES"))
    )
    (comp (ref "K39")
      (value "M")
      (footprint "eagle-import:B3F-40XXNOHOLE")
      (libsource (lib "eagle-import") (part "40-XXNOHOLES"))
    )
    (comp (ref "K40")
      (value "SPACE")
      (footprint "eagle-import:B3F-40XXNOHOLE")
      (libsource (lib "eagle-import") (part "40-XXNOHOLES"))
    )
    (comp (ref "K41")
      (value "SPACE")
      (footprint "eagle-import:B3F-40XXNOHOLE")
      (libsource (lib "eagle-import") (part "40-XXNOHOLES"))
    )
    (comp (ref "LED1")
      (value "POWER")
      (footprint "eagle-import:LED3MM")
      (libsource (lib "eagle-import") (part "LED3MM"))
    )
    (comp (ref "LED2")
      (value "ACE81")
      (footprint "eagle-import:LED3MM")
      (libsource (lib "eagle-import") (part "LED3MM"))
    )
    (comp (ref "LS1")
      (value "F/QMX")
      (footprint "eagle-import:F_QMX")
      (libsource (lib "eagle-import") (part "F/QMX"))
    )
    (comp (ref "MIC")
      (value "PJ302M")
      (footprint "eagle-import:PJ302M")
      (libsource (lib "eagle-import") (part "PJ302M"))
    )
    (comp (ref "POWER")
      (value "PJ302M")
      (footprint "eagle-import:PJ302M")
      (libsource (lib "eagle-import") (part "PJ302M"))
    )
    (comp (ref "Q1")
      (value "2N3904")
      (footprint "eagle-import:TO92")
      (libsource (lib "eagle-import") (part "2N3904"))
    )
    (comp (ref "Q3")
      (value "BC337")
      (footprint "eagle-import:TO92")
      (libsource (lib "eagle-import") (part "BC337"))
    )
    (comp (ref "R1")
      (value "1K")
      (footprint "eagle-import:0204_7")
      (libsource (lib "eagle-import") (part "R-EU_0204/7"))
    )
    (comp (ref "R2")
      (value "47K")
      (footprint "eagle-import:0204_7")
      (libsource (lib "eagle-import") (part "R-EU_0204/7"))
    )
    (comp (ref "R3")
      (value "500R")
      (footprint "eagle-import:B25P")
      (libsource (lib "eagle-import") (part "TRIM_EU-B25P"))
    )
    (comp (ref "R4")
      (value "1K")
      (footprint "eagle-import:B25P")
      (libsource (lib "eagle-import") (part "TRIM_EU-B25P"))
    )
    (comp (ref "R5")
      (value "12K")
      (footprint "eagle-import:0204_7")
      (libsource (lib "eagle-import") (part "R-EU_0204/7"))
    )
    (comp (ref "R6")
      (value "1K")
      (footprint "eagle-import:0204_7")
      (libsource (lib "eagle-import") (part "R-EU_0204/7"))
    )
    (comp (ref "R7")
      (value "33K")
      (footprint "eagle-import:0204_7")
      (libsource (lib "eagle-import") (part "R-EU_0204/7"))
    )
    (comp (ref "R8")
      (value "10K")
      (footprint "eagle-import:0204_7")
      (libsource (lib "eagle-import") (part "R-EU_0204/7"))
    )
    (comp (ref "R9")
      (value "22K")
      (footprint "eagle-import:0204_7")
      (libsource (lib "eagle-import") (part "R-EU_0204/7"))
    )
    (comp (ref "R10")
      (value "10K")
      (footprint "eagle-import:0204_7")
      (libsource (lib "eagle-import") (part "R-EU_0204/7"))
    )
    (comp (ref "R11")
      (value "1K")
      (footprint "eagle-import:0204_7")
      (libsource (lib "eagle-import") (part "R-EU_0204/7"))
    )
    (comp (ref "R12")
      (value "1K")
      (footprint "eagle-import:0204_7")
      (libsource (lib "eagle-import") (part "R-EU_0204/7"))
    )
    (comp (ref "R13")
      (value "1K")
      (footprint "eagle-import:0204_7")
      (libsource (lib "eagle-import") (part "R-EU_0204/7"))
    )
    (comp (ref "R14")
      (value "1K")
      (footprint "eagle-import:0204_7")
      (libsource (lib "eagle-import") (part "R-EU_0204/7"))
    )
    (comp (ref "R15")
      (value "1K")
      (footprint "eagle-import:0204_7")
      (libsource (lib "eagle-import") (part "R-EU_0204/7"))
    )
    (comp (ref "R16")
      (value "1K")
      (footprint "eagle-import:0204_7")
      (libsource (lib "eagle-import") (part "R-EU_0204/7"))
    )
    (comp (ref "R17")
      (value "1K")
      (footprint "eagle-import:0204_7")
      (libsource (lib "eagle-import") (part "R-EU_0204/7"))
    )
    (comp (ref "R18")
      (value "1K")
      (footprint "eagle-import:0204_7")
      (libsource (lib "eagle-import") (part "R-EU_0204/7"))
    )
    (comp (ref "R19")
      (value "1K")
      (footprint "eagle-import:0204_7")
      (libsource (lib "eagle-import") (part "R-EU_0204/7"))
    )
    (comp (ref "R20")
      (value "1K")
      (footprint "eagle-import:0204_7")
      (libsource (lib "eagle-import") (part "R-EU_0204/7"))
    )
    (comp (ref "R21")
      (value "1K")
      (footprint "eagle-import:0204V")
      (libsource (lib "eagle-import") (part "R-EU_0204/2V"))
    )
    (comp (ref "R22")
      (value "1K")
      (footprint "eagle-import:0204V")
      (libsource (lib "eagle-import") (part "R-EU_0204/2V"))
    )
    (comp (ref "R23")
      (value "1K")
      (footprint "eagle-import:0204V")
      (libsource (lib "eagle-import") (part "R-EU_0204/2V"))
    )
    (comp (ref "R24")
      (value "10K")
      (footprint "eagle-import:0204_7")
      (libsource (lib "eagle-import") (part "R-EU_0204/7"))
    )
    (comp (ref "R25")
      (value "10K")
      (footprint "eagle-import:0204_7")
      (libsource (lib "eagle-import") (part "R-EU_0204/7"))
    )
    (comp (ref "R26")
      (value "330")
      (footprint "eagle-import:0204_7")
      (libsource (lib "eagle-import") (part "R-EU_0204/7"))
    )
    (comp (ref "R27")
      (value "10K")
      (footprint "eagle-import:0204_7")
      (libsource (lib "eagle-import") (part "R-EU_0204/7"))
    )
    (comp (ref "R28")
      (value "680")
      (footprint "eagle-import:0204_7")
      (libsource (lib "eagle-import") (part "R-EU_0204/7"))
    )
    (comp (ref "R29")
      (value "680")
      (footprint "eagle-import:0204_7")
      (libsource (lib "eagle-import") (part "R-EU_0204/7"))
    )
    (comp (ref "R32")
      (value "200")
      (footprint "eagle-import:0204_7")
      (libsource (lib "eagle-import") (part "R-EU_0204/7"))
    )
    (comp (ref "R33")
      (value "200")
      (footprint "eagle-import:0204_7")
      (libsource (lib "eagle-import") (part "R-EU_0204/7"))
    )
    (comp (ref "R34")
      (value "75")
      (footprint "eagle-import:0204_7")
      (libsource (lib "eagle-import") (part "R-EU_0204/7"))
    )
    (comp (ref "R35")
      (value "300")
      (footprint "eagle-import:0204_7")
      (libsource (lib "eagle-import") (part "R-EU_0204/7"))
    )
    (comp (ref "R36")
      (value "4K7")
      (footprint "eagle-import:0207_10")
      (libsource (lib "eagle-import") (part "R-EU_0207/10"))
    )
    (comp (ref "R37")
      (value "4K7")
      (footprint "eagle-import:0207_10")
      (libsource (lib "eagle-import") (part "R-EU_0207/10"))
    )
    (comp (ref "R38")
      (value "4K7")
      (footprint "eagle-import:0207_10")
      (libsource (lib "eagle-import") (part "R-EU_0207/10"))
    )
    (comp (ref "R39")
      (value "10K")
      (footprint "eagle-import:0204_7")
      (libsource (lib "eagle-import") (part "R-EU_0204/7"))
    )
    (comp (ref "R40")
      (value "4K7")
      (footprint "eagle-import:0207_10")
      (libsource (lib "eagle-import") (part "R-EU_0207/10"))
    )
    (comp (ref "R41")
      (value "4K7")
      (footprint "eagle-import:0207_10")
      (libsource (lib "eagle-import") (part "R-EU_0207/10"))
    )
    (comp (ref "R42")
      (value "1K")
      (footprint "eagle-import:0204_7")
      (libsource (lib "eagle-import") (part "R-EU_0204/7"))
    )
    (comp (ref "R43")
      (value "10K")
      (footprint "eagle-import:0204_7")
      (libsource (lib "eagle-import") (part "R-EU_0204/7"))
    )
    (comp (ref "R44")
      (value "1K")
      (footprint "eagle-import:B25P")
      (libsource (lib "eagle-import") (part "TRIM_EU-B25P"))
    )
    (comp (ref "R45")
      (value "470R")
      (footprint "eagle-import:0204_7")
      (libsource (lib "eagle-import") (part "R-EU_0204/7"))
    )
    (comp (ref "R46")
      (value "470R")
      (footprint "eagle-import:0204_7")
      (libsource (lib "eagle-import") (part "R-EU_0204/7"))
    )
    (comp (ref "R47")
      (value "470R")
      (footprint "eagle-import:0204_7")
      (libsource (lib "eagle-import") (part "R-EU_0204/7"))
    )
    (comp (ref "R100")
      (value "1K")
      (footprint "eagle-import:0204V")
      (libsource (lib "eagle-import") (part "R-US_0204/2V"))
    )
    (comp (ref "R101")
      (value "1K")
      (footprint "eagle-import:0204V")
      (libsource (lib "eagle-import") (part "R-US_0204/2V"))
    )
    (comp (ref "R102")
      (value "1K")
      (footprint "eagle-import:0204V")
      (libsource (lib "eagle-import") (part "R-US_0204/2V"))
    )
    (comp (ref "R103")
      (value "1K")
      (footprint "eagle-import:0204V")
      (libsource (lib "eagle-import") (part "R-US_0204/2V"))
    )
    (comp (ref "R104")
      (value "1K")
      (footprint "eagle-import:0204V")
      (libsource (lib "eagle-import") (part "R-US_0204/2V"))
    )
    (comp (ref "R105")
      (value "1K")
      (footprint "eagle-import:0204V")
      (libsource (lib "eagle-import") (part "R-US_0204/2V"))
    )
    (comp (ref "R106")
      (value "1K")
      (footprint "eagle-import:0204V")
      (libsource (lib "eagle-import") (part "R-US_0204/2V"))
    )
    (comp (ref "R107")
      (value "1K")
      (footprint "eagle-import:0204V")
      (libsource (lib "eagle-import") (part "R-US_0204/2V"))
    )
    (comp (ref "R200")
      (value "1K")
      (footprint "eagle-import:0204V")
      (libsource (lib "eagle-import") (part "R-US_0204/2V"))
    )
    (comp (ref "R201")
      (value "1K")
      (footprint "eagle-import:0204V")
      (libsource (lib "eagle-import") (part "R-US_0204/2V"))
    )
    (comp (ref "R202")
      (value "1K")
      (footprint "eagle-import:0204V")
      (libsource (lib "eagle-import") (part "R-US_0204/2V"))
    )
    (comp (ref "R203")
      (value "1K")
      (footprint "eagle-import:0204V")
      (libsource (lib "eagle-import") (part "R-US_0204/2V"))
    )
    (comp (ref "R204")
      (value "1K")
      (footprint "eagle-import:0204V")
      (libsource (lib "eagle-import") (part "R-US_0204/2V"))
    )
    (comp (ref "R205")
      (value "1K")
      (footprint "eagle-import:0204V")
      (libsource (lib "eagle-import") (part "R-US_0204/2V"))
    )
    (comp (ref "R206")
      (value "1K")
      (footprint "eagle-import:0204V")
      (libsource (lib "eagle-import") (part "R-US_0204/2V"))
    )
    (comp (ref "R207")
      (value "1K")
      (footprint "eagle-import:0204V")
      (libsource (lib "eagle-import") (part "R-US_0204/2V"))
    )
    (comp (ref "RN1")
      (value "4K7")
      (footprint "eagle-import:RN-6")
      (libsource (lib "eagle-import") (part "RN05"))
    )
    (comp (ref "S1")
      (value "ROMSEL")
      (footprint "eagle-import:DP-03")
      (fields (field (name "MPN") "MCDP03"))
      (libsource (lib "eagle-import") (part "DP03"))
    )
    (comp (ref "S2")
      (value "RESET")
      (footprint "eagle-import:B3F-31XX")
      (fields (field (name "MPN") "B3F-3100"))
      (libsource (lib "eagle-import") (part "31-XX"))
    )
    (comp (ref "SJ1")
      (value "NO OPAMP")
      (footprint "eagle-import:SJ")
      (libsource (lib "eagle-import") (part "SJ"))
    )
    (comp (ref "U$1")
      (value "40-XX-CARBON")
      (footprint "eagle-import:CARBONB3F")
      (libsource (lib "eagle-import") (part "40-XX-CARBON"))
    )
    (comp (ref "U$2")
      (value "40-XX-CARBON")
      (footprint "eagle-import:CARBONB3F")
      (libsource (lib "eagle-import") (part "40-XX-CARBON"))
    )
    (comp (ref "U$3")
      (value "40-XX-CARBON")
      (footprint "eagle-import:CARBONB3F")
      (libsource (lib "eagle-import") (part "40-XX-CARBON"))
    )
    (comp (ref "U$4")
      (value "40-XX-CARBON")
      (footprint "eagle-import:CARBONB3F")
      (libsource (lib "eagle-import") (part "40-XX-CARBON"))
    )
    (comp (ref "U$5")
      (value "40-XX-CARBON")
      (footprint "eagle-import:CARBONB3F")
      (libsource (lib "eagle-import") (part "40-XX-CARBON"))
    )
    (comp (ref "U$6")
      (value "40-XX-CARBON")
      (footprint "eagle-import:CARBONB3F")
      (libsource (lib "eagle-import") (part "40-XX-CARBON"))
    )
    (comp (ref "U$7")
      (value "40-XX-CARBON")
      (footprint "eagle-import:CARBONB3F")
      (libsource (lib "eagle-import") (part "40-XX-CARBON"))
    )
    (comp (ref "U$8")
      (value "40-XX-CARBON")
      (footprint "eagle-import:CARBONB3F")
      (libsource (lib "eagle-import") (part "40-XX-CARBON"))
    )
    (comp (ref "U$9")
      (value "40-XX-CARBON")
      (footprint "eagle-import:CARBONB3F")
      (libsource (lib "eagle-import") (part "40-XX-CARBON"))
    )
    (comp (ref "U$10")
      (value "40-XX-CARBON")
      (footprint "eagle-import:CARBONB3F")
      (libsource (lib "eagle-import") (part "40-XX-CARBON"))
    )
    (comp (ref "U$11")
      (value "40-XX-CARBON")
      (footprint "eagle-import:CARBONB3F")
      (libsource (lib "eagle-import") (part "40-XX-CARBON"))
    )
    (comp (ref "U$12")
      (value "40-XX-CARBON")
      (footprint "eagle-import:CARBONB3F")
      (libsource (lib "eagle-import") (part "40-XX-CARBON"))
    )
    (comp (ref "U$13")
      (value "40-XX-CARBON")
      (footprint "eagle-import:CARBONB3F")
      (libsource (lib "eagle-import") (part "40-XX-CARBON"))
    )
    (comp (ref "U$14")
      (value "40-XX-CARBON")
      (footprint "eagle-import:CARBONB3F")
      (libsource (lib "eagle-import") (part "40-XX-CARBON"))
    )
    (comp (ref "U$15")
      (value "40-XX-CARBON")
      (footprint "eagle-import:CARBONB3F")
      (libsource (lib "eagle-import") (part "40-XX-CARBON"))
    )
    (comp (ref "U$16")
      (value "40-XX-CARBON")
      (footprint "eagle-import:CARBONB3F")
      (libsource (lib "eagle-import") (part "40-XX-CARBON"))
    )
    (comp (ref "U$17")
      (value "40-XX-CARBON")
      (footprint "eagle-import:CARBONB3F")
      (libsource (lib "eagle-import") (part "40-XX-CARBON"))
    )
    (comp (ref "U$18")
      (value "40-XX-CARBON")
      (footprint "eagle-import:CARBONB3F")
      (libsource (lib "eagle-import") (part "40-XX-CARBON"))
    )
    (comp (ref "U$19")
      (value "40-XX-CARBON")
      (footprint "eagle-import:CARBONB3F")
      (libsource (lib "eagle-import") (part "40-XX-CARBON"))
    )
    (comp (ref "U$20")
      (value "40-XX-CARBON")
      (footprint "eagle-import:CARBONB3F")
      (libsource (lib "eagle-import") (part "40-XX-CARBON"))
    )
    (comp (ref "U$21")
      (value "40-XX-CARBON")
      (footprint "eagle-import:CARBONB3F")
      (libsource (lib "eagle-import") (part "40-XX-CARBON"))
    )
    (comp (ref "U$22")
      (value "40-XX-CARBON")
      (footprint "eagle-import:CARBONB3F")
      (libsource (lib "eagle-import") (part "40-XX-CARBON"))
    )
    (comp (ref "U$23")
      (value "40-XX-CARBON")
      (footprint "eagle-import:CARBONB3F")
      (libsource (lib "eagle-import") (part "40-XX-CARBON"))
    )
    (comp (ref "U$24")
      (value "40-XX-CARBON")
      (footprint "eagle-import:CARBONB3F")
      (libsource (lib "eagle-import") (part "40-XX-CARBON"))
    )
    (comp (ref "U$25")
      (value "40-XX-CARBON")
      (footprint "eagle-import:CARBONB3F")
      (libsource (lib "eagle-import") (part "40-XX-CARBON"))
    )
    (comp (ref "U$26")
      (value "40-XX-CARBON")
      (footprint "eagle-import:CARBONB3F")
      (libsource (lib "eagle-import") (part "40-XX-CARBON"))
    )
    (comp (ref "U$27")
      (value "40-XX-CARBON")
      (footprint "eagle-import:CARBONB3F")
      (libsource (lib "eagle-import") (part "40-XX-CARBON"))
    )
    (comp (ref "U$28")
      (value "40-XX-CARBON")
      (footprint "eagle-import:CARBONB3F")
      (libsource (lib "eagle-import") (part "40-XX-CARBON"))
    )
    (comp (ref "U$29")
      (value "40-XX-CARBON")
      (footprint "eagle-import:CARBONB3F")
      (libsource (lib "eagle-import") (part "40-XX-CARBON"))
    )
    (comp (ref "U$30")
      (value "40-XX-CARBON")
      (footprint "eagle-import:CARBONB3F")
      (libsource (lib "eagle-import") (part "40-XX-CARBON"))
    )
    (comp (ref "U$31")
      (value "40-XX-CARBON")
      (footprint "eagle-import:CARBONB3F")
      (libsource (lib "eagle-import") (part "40-XX-CARBON"))
    )
    (comp (ref "U$32")
      (value "40-XX-CARBON")
      (footprint "eagle-import:CARBONB3F")
      (libsource (lib "eagle-import") (part "40-XX-CARBON"))
    )
    (comp (ref "U$33")
      (value "40-XX-CARBON")
      (footprint "eagle-import:CARBONB3F")
      (libsource (lib "eagle-import") (part "40-XX-CARBON"))
    )
    (comp (ref "U$34")
      (value "40-XX-CARBON")
      (footprint "eagle-import:CARBONB3F")
      (libsource (lib "eagle-import") (part "40-XX-CARBON"))
    )
    (comp (ref "U$35")
      (value "40-XX-CARBON")
      (footprint "eagle-import:CARBONB3F")
      (libsource (lib "eagle-import") (part "40-XX-CARBON"))
    )
    (comp (ref "U$36")
      (value "40-XX-CARBON")
      (footprint "eagle-import:CARBONB3F")
      (libsource (lib "eagle-import") (part "40-XX-CARBON"))
    )
    (comp (ref "U$37")
      (value "40-XX-CARBON")
      (footprint "eagle-import:CARBONB3F")
      (libsource (lib "eagle-import") (part "40-XX-CARBON"))
    )
    (comp (ref "U$38")
      (value "40-XX-CARBON")
      (footprint "eagle-import:CARBONB3F")
      (libsource (lib "eagle-import") (part "40-XX-CARBON"))
    )
    (comp (ref "U$39")
      (value "40-XX-CARBON")
      (footprint "eagle-import:CARBONB3F")
      (libsource (lib "eagle-import") (part "40-XX-CARBON"))
    )
    (comp (ref "U$40")
      (value "40-XX-CARBON")
      (footprint "eagle-import:CARBONB3F")
      (libsource (lib "eagle-import") (part "40-XX-CARBON"))
    )
    (comp (ref "U$41")
      (value "40-XX-CARBON")
      (footprint "eagle-import:CARBONB3F")
      (libsource (lib "eagle-import") (part "40-XX-CARBON"))
    )
    (comp (ref "U$42")
      (value "40-XX-CARBON")
      (footprint "eagle-import:CARBONB3F")
      (libsource (lib "eagle-import") (part "40-XX-CARBON"))
    )
    (comp (ref "U1")
      (value "7805")
      (footprint "eagle-import:TO220V")
      (libsource (lib "eagle-import") (part "78TV05"))
    )
    (comp (ref "U2")
      (value "MAX4390EUK")
      (footprint "eagle-import:SOT95P280X145-5N")
      (fields (field (name "MF") "Maxim Integrated") (field (name "MP") "MAX4390EUK+T"))
      (libsource (lib "eagle-import") (part "MAX4390EUK"))
    )
    (comp (ref "X1")
      (value "6.5MHz")
      (footprint "eagle-import:HC49U")
      (libsource (lib "eagle-import") (part "8M10AHC49T"))
    )
    (comp (ref "X2")
      (value "CON-CONRAD_736880-49")
      (footprint "eagle-import:CON-CONRAD_736880-49")
      (libsource (lib "eagle-import") (part "CON-CONRAD_736880-49"))
    )
    (comp (ref "Z0")
      (value "Z80")
      (footprint "eagle-import:DIL40")
      (libsource (lib "eagle-import") (part "Z80CPU"))
    )
    (comp (ref "Z1")
      (value "74LS74N")
      (footprint "eagle-import:DIL14")
      (libsource (lib "eagle-import") (part "7474NLS"))
    )
    (comp (ref "Z1-2")
      (value "27C512")
      (footprint "eagle-import:DIL28-6")
      (libsource (lib "eagle-import") (part "27512G"))
    )
    (comp (ref "Z3-4")
      (value "CY62256LL-PC")
      (footprint "eagle-import:DIL28-6")
      (libsource (lib "eagle-import") (part "CY62256LL-?PC"))
    )
    (comp (ref "Z5-6")
      (value "CY62256LL-PC")
      (footprint "eagle-import:DIL28-6")
      (libsource (lib "eagle-import") (part "CY62256LL-?PC"))
    )
    (comp (ref "Z7-8")
      (value "CY62256LL-PC")
      (footprint "eagle-import:DIL28-6")
      (libsource (lib "eagle-import") (part "CY62256LL-?PC"))
    )
    (comp (ref "Z9")
      (value "74LS393N")
      (footprint "eagle-import:DIL14")
      (libsource (lib "eagle-import") (part "74393NLS"))
    )
    (comp (ref "Z10")
      (value "74LS393N")
      (footprint "eagle-import:DIL14")
      (libsource (lib "eagle-import") (part "74393NLS"))
    )
    (comp (ref "Z11")
      (value "74LS393N")
      (footprint "eagle-import:DIL14")
      (libsource (lib "eagle-import") (part "74393NLS"))
    )
    (comp (ref "Z14")
      (value "74367N")
      (footprint "eagle-import:DIL16")
      (libsource (lib "eagle-import") (part "74367N"))
    )
    (comp (ref "Z15")
      (value "74367N")
      (footprint "eagle-import:DIL16")
      (libsource (lib "eagle-import") (part "74367N"))
    )
    (comp (ref "Z16")
      (value "74367N")
      (footprint "eagle-import:DIL16")
      (libsource (lib "eagle-import") (part "74367N"))
    )
    (comp (ref "Z17")
      (value "74367N")
      (footprint "eagle-import:DIL16")
      (libsource (lib "eagle-import") (part "74367N"))
    )
    (comp (ref "Z18")
      (value "74367N")
      (footprint "eagle-import:DIL16")
      (libsource (lib "eagle-import") (part "74367N"))
    )
    (comp (ref "Z19")
      (value "74LS00N")
      (footprint "eagle-import:DIL14")
      (libsource (lib "eagle-import") (part "7400NLS"))
    )
    (comp (ref "Z20")
      (value "74LS08N")
      (footprint "eagle-import:DIL14")
      (libsource (lib "eagle-import") (part "7408NLS"))
    )
    (comp (ref "Z21")
      (value "74LS11N")
      (footprint "eagle-import:DIL14")
      (libsource (lib "eagle-import") (part "7411NLS"))
    )
    (comp (ref "Z22")
      (value "74LS11N")
      (footprint "eagle-import:DIL14")
      (libsource (lib "eagle-import") (part "7411NLS"))
    )
    (comp (ref "Z23")
      (value "74LS86N")
      (footprint "eagle-import:DIL14")
      (libsource (lib "eagle-import") (part "7486NLS"))
    )
    (comp (ref "Z24")
      (value "74LS02N")
      (footprint "eagle-import:DIL14")
      (libsource (lib "eagle-import") (part "7402NLS"))
    )
    (comp (ref "Z25")
      (value "74LS02N")
      (footprint "eagle-import:DIL14")
      (libsource (lib "eagle-import") (part "7402NLS"))
    )
    (comp (ref "Z26")
      (value "74LS32N")
      (footprint "eagle-import:DIL14")
      (libsource (lib "eagle-import") (part "7432NLS"))
    )
    (comp (ref "Z27")
      (value "74LS74N")
      (footprint "eagle-import:DIL14")
      (libsource (lib "eagle-import") (part "7474NLS"))
    )
    (comp (ref "Z28")
      (value "74LS166N")
      (footprint "eagle-import:DIL16")
      (libsource (lib "eagle-import") (part "74166NLS"))
    )
    (comp (ref "Z29")
      (value "74LS138N")
      (footprint "eagle-import:DIL16")
      (libsource (lib "eagle-import") (part "74138NLS"))
    )
    (comp (ref "Z30")
      (value "74LS00N")
      (footprint "eagle-import:DIL14")
      (libsource (lib "eagle-import") (part "7400NLS"))
    )
    (comp (ref "Z31")
      (value "74LS11N")
      (footprint "eagle-import:DIL14")
      (libsource (lib "eagle-import") (part "7411NLS"))
    )
    (comp (ref "Z41")
      (value "74LS00N")
      (footprint "eagle-import:DIL14")
      (libsource (lib "eagle-import") (part "7400NLS"))
    )
  )
  (nets
    (net (code "3") (name "/9V") (class "Default")
      (node (ref "3A") (pin "1") (pinfunction "P_1") (pintype "passive"))
      (node (ref "C10") (pin "1") (pinfunction "1_1") (pintype "passive"))
      (node (ref "C11") (pin "+") (pinfunction "+_+") (pintype "passive"))
      (node (ref "C9") (pin "+") (pinfunction "+_+") (pintype "passive"))
      (node (ref "JP7") (pin "1") (pinfunction "1_1") (pintype "passive"))
      (node (ref "U1") (pin "1") (pinfunction "VI_1") (pintype "input"))
    )
    (net (code "4") (name "/A0") (class "Default")
      (node (ref "19A") (pin "1") (pinfunction "P_1") (pintype "passive"))
      (node (ref "JP9") (pin "11") (pinfunction "11_11") (pintype "passive"))
      (node (ref "Z0") (pin "30") (pinfunction "A0_30") (pintype "output"))
      (node (ref "Z1-2") (pin "10") (pinfunction "A0_10") (pintype "input"))
      (node (ref "Z15") (pin "2") (pinfunction "1A1_2") (pintype "input"))
      (node (ref "Z18") (pin "10") (pinfunction "1A4_10") (pintype "input"))
      (node (ref "Z26") (pin "5") (pinfunction "I1_5") (pintype "input"))
      (node (ref "Z3-4") (pin "21") (pinfunction "A0_21") (pintype "input"))
    )
    (net (code "5") (name "/A1") (class "Default")
      (node (ref "19B") (pin "1") (pinfunction "P_1") (pintype "passive"))
      (node (ref "JP9") (pin "10") (pinfunction "10_10") (pintype "passive"))
      (node (ref "Z0") (pin "31") (pinfunction "A1_31") (pintype "output"))
      (node (ref "Z1-2") (pin "9") (pinfunction "A1_9") (pintype "input"))
      (node (ref "Z15") (pin "4") (pinfunction "1A2_4") (pintype "input"))
      (node (ref "Z18") (pin "6") (pinfunction "1A3_6") (pintype "input"))
      (node (ref "Z3-4") (pin "23") (pinfunction "A1_23") (pintype "input"))
    )
    (net (code "6") (name "/A2") (class "Default")
      (node (ref "14A") (pin "1") (pinfunction "P_1") (pintype "passive"))
      (node (ref "JP9") (pin "9") (pinfunction "9_9") (pintype "passive"))
      (node (ref "Z0") (pin "32") (pinfunction "A2_32") (pintype "output"))
      (node (ref "Z1-2") (pin "8") (pinfunction "A2_8") (pintype "input"))
      (node (ref "Z15") (pin "6") (pinfunction "1A3_6") (pintype "input"))
      (node (ref "Z18") (pin "4") (pinfunction "1A2_4") (pintype "input"))
      (node (ref "Z3-4") (pin "24") (pinfunction "A2_24") (pintype "input"))
    )
    (net (code "7") (name "/A3") (class "Default")
      (node (ref "18B") (pin "1") (pinfunction "P_1") (pintype "passive"))
      (node (ref "JP9") (pin "8") (pinfunction "8_8") (pintype "passive"))
      (node (ref "Z0") (pin "33") (pinfunction "A3_33") (pintype "output"))
      (node (ref "Z1-2") (pin "7") (pinfunction "A3_7") (pintype "input"))
      (node (ref "Z15") (pin "10") (pinfunction "1A4_10") (pintype "input"))
      (node (ref "Z18") (pin "2") (pinfunction "1A1_2") (pintype "input"))
      (node (ref "Z3-4") (pin "25") (pinfunction "A3_25") (pintype "input"))
    )
    (net (code "8") (name "/A4") (class "Default")
      (node (ref "17B") (pin "1") (pinfunction "P_1") (pintype "passive"))
      (node (ref "JP9") (pin "7") (pinfunction "7_7") (pintype "passive"))
      (node (ref "Z0") (pin "34") (pinfunction "A4_34") (pintype "output"))
      (node (ref "Z1-2") (pin "6") (pinfunction "A4_6") (pintype "input"))
      (node (ref "Z15") (pin "12") (pinfunction "2A1_12") (pintype "input"))
      (node (ref "Z17") (pin "14") (pinfunction "2A2_14") (pintype "input"))
      (node (ref "Z3-4") (pin "26") (pinfunction "A4_26") (pintype "input"))
    )
    (net (code "9") (name "/A5") (class "Default")
      (node (ref "16B") (pin "1") (pinfunction "P_1") (pintype "passive"))
      (node (ref "JP9") (pin "6") (pinfunction "6_6") (pintype "passive"))
      (node (ref "Z0") (pin "35") (pinfunction "A5_35") (pintype "output"))
      (node (ref "Z1-2") (pin "5") (pinfunction "A5_5") (pintype "input"))
      (node (ref "Z15") (pin "14") (pinfunction "2A2_14") (pintype "input"))
      (node (ref "Z17") (pin "12") (pinfunction "2A1_12") (pintype "input"))
      (node (ref "Z3-4") (pin "1") (pinfunction "A5_1") (pintype "input"))
    )
    (net (code "10") (name "/A6") (class "Default")
      (node (ref "15B") (pin "1") (pinfunction "P_1") (pintype "passive"))
      (node (ref "JP9") (pin "5") (pinfunction "5_5") (pintype "passive"))
      (node (ref "Z0") (pin "36") (pinfunction "A6_36") (pintype "output"))
      (node (ref "Z1-2") (pin "4") (pinfunction "A6_4") (pintype "input"))
      (node (ref "Z16") (pin "2") (pinfunction "1A1_2") (pintype "input"))
      (node (ref "Z17") (pin "10") (pinfunction "1A4_10") (pintype "input"))
      (node (ref "Z3-4") (pin "2") (pinfunction "A6_2") (pintype "input"))
    )
    (net (code "11") (name "/A7") (class "Default")
      (node (ref "18A") (pin "1") (pinfunction "P_1") (pintype "passive"))
      (node (ref "JP9") (pin "4") (pinfunction "4_4") (pintype "passive"))
      (node (ref "Z0") (pin "37") (pinfunction "A7_37") (pintype "output"))
      (node (ref "Z1-2") (pin "3") (pinfunction "A7_3") (pintype "input"))
      (node (ref "Z16") (pin "4") (pinfunction "1A2_4") (pintype "input"))
      (node (ref "Z17") (pin "6") (pinfunction "1A3_6") (pintype "input"))
      (node (ref "Z3-4") (pin "3") (pinfunction "A7_3") (pintype "input"))
    )
    (net (code "12") (name "/A8") (class "Default")
      (node (ref "17A") (pin "1") (pinfunction "P_1") (pintype "passive"))
      (node (ref "D10") (pin "C") (pinfunction "C_C") (pintype "passive"))
      (node (ref "JP9") (pin "3") (pinfunction "3_3") (pintype "passive"))
      (node (ref "Z0") (pin "38") (pinfunction "A8_38") (pintype "output"))
      (node (ref "Z1-2") (pin "25") (pinfunction "A8_25") (pintype "input"))
      (node (ref "Z16") (pin "6") (pinfunction "1A3_6") (pintype "input"))
      (node (ref "Z17") (pin "4") (pinfunction "1A2_4") (pintype "input"))
      (node (ref "Z3-4") (pin "4") (pinfunction "A8_4") (pintype "input"))
    )
    (net (code "13") (name "/A9") (class "Default")
      (node (ref "16A") (pin "1") (pinfunction "P_1") (pintype "passive"))
      (node (ref "D9") (pin "C") (pinfunction "C_C") (pintype "passive"))
      (node (ref "JP9") (pin "2") (pinfunction "2_2") (pintype "passive"))
      (node (ref "Z0") (pin "39") (pinfunction "A9_39") (pintype "output"))
      (node (ref "Z1-2") (pin "24") (pinfunction "A9_24") (pintype "input"))
      (node (ref "Z16") (pin "10") (pinfunction "1A4_10") (pintype "input"))
      (node (ref "Z17") (pin "2") (pinfunction "1A1_2") (pintype "input"))
      (node (ref "Z3-4") (pin "5") (pinfunction "A9_5") (pintype "input"))
    )
    (net (code "14") (name "/A10") (class "Default")
      (node (ref "15A") (pin "1") (pinfunction "P_1") (pintype "passive"))
      (node (ref "D8") (pin "C") (pinfunction "C_C") (pintype "passive"))
      (node (ref "JP9") (pin "1") (pinfunction "1_1") (pintype "passive"))
      (node (ref "Z0") (pin "40") (pinfunction "A10_40") (pintype "output"))
      (node (ref "Z1-2") (pin "21") (pinfunction "A10_21") (pintype "input"))
      (node (ref "Z19") (pin "9") (pinfunction "I0_9") (pintype "input"))
      (node (ref "Z30") (pin "9") (pinfunction "I0_9") (pintype "input"))
    )
    (net (code "15") (name "/A10'") (class "Default")
      (node (ref "Z3-4") (pin "6") (pinfunction "A10_6") (pintype "input"))
      (node (ref "Z30") (pin "8") (pinfunction "O_8") (pintype "output"))
    )
    (net (code "16") (name "/A11") (class "Default")
      (node (ref "6A") (pin "1") (pinfunction "P_1") (pintype "passive"))
      (node (ref "D7") (pin "C") (pinfunction "C_C") (pintype "passive"))
      (node (ref "JP2") (pin "1") (pinfunction "1_1") (pintype "passive"))
      (node (ref "Z0") (pin "1") (pinfunction "A11_1") (pintype "output"))
      (node (ref "Z1-2") (pin "23") (pinfunction "A11_23") (pintype "input"))
      (node (ref "Z24") (pin "6") (pinfunction "I1_6") (pintype "input"))
      (node (ref "Z30") (pin "12") (pinfunction "I0_12") (pintype "input"))
    )
    (net (code "17") (name "/A11'") (class "Default")
      (node (ref "Z3-4") (pin "7") (pinfunction "A11_7") (pintype "input"))
      (node (ref "Z30") (pin "11") (pinfunction "O_11") (pintype "output"))
    )
    (net (code "18") (name "/A12") (class "Default")
      (node (ref "7A") (pin "1") (pinfunction "P_1") (pintype "passive"))
      (node (ref "D6") (pin "C") (pinfunction "C_C") (pintype "passive"))
      (node (ref "JP2") (pin "2") (pinfunction "2_2") (pintype "passive"))
      (node (ref "Z0") (pin "2") (pinfunction "A12_2") (pintype "output"))
      (node (ref "Z1-2") (pin "2") (pinfunction "A12_2") (pintype "input"))
      (node (ref "Z29") (pin "1") (pinfunction "A_1") (pintype "input"))
      (node (ref "Z3-4") (pin "8") (pinfunction "A12_8") (pintype "input"))
    )
    (net (code "19") (name "/A13") (class "Default")
      (node (ref "8A") (pin "1") (pinfunction "P_1") (pintype "passive"))
      (node (ref "D5") (pin "C") (pinfunction "C_C") (pintype "passive"))
      (node (ref "JP2") (pin "3") (pinfunction "3_3") (pintype "passive"))
      (node (ref "Z0") (pin "3") (pinfunction "A13_3") (pintype "output"))
      (node (ref "Z29") (pin "2") (pinfunction "B_2") (pintype "input"))
      (node (ref "Z3-4") (pin "9") (pinfunction "A13_9") (pintype "input"))
    )
    (net (code "20") (name "/A14") (class "Default")
      (node (ref "9A") (pin "1") (pinfunction "P_1") (pintype "passive"))
      (node (ref "D4") (pin "C") (pinfunction "C_C") (pintype "passive"))
      (node (ref "JP2") (pin "4") (pinfunction "4_4") (pintype "passive"))
      (node (ref "Z0") (pin "4") (pinfunction "A14_4") (pintype "output"))
      (node (ref "Z29") (pin "3") (pinfunction "C_3") (pintype "input"))
      (node (ref "Z3-4") (pin "10") (pinfunction "A14_10") (pintype "input"))
      (node (ref "Z30") (pin "10") (pinfunction "I1_10") (pintype "input"))
      (node (ref "Z30") (pin "13") (pinfunction "I1_13") (pintype "input"))
    )
    (net (code "21") (name "/A15") (class "Default")
      (node (ref "10A") (pin "1") (pinfunction "P_1") (pintype "passive"))
      (node (ref "D3") (pin "C") (pinfunction "C_C") (pintype "passive"))
      (node (ref "JP2") (pin "5") (pinfunction "5_5") (pintype "passive"))
      (node (ref "Z0") (pin "5") (pinfunction "A15_5") (pintype "output"))
      (node (ref "Z29") (pin "5") (pinfunction "G2B_5") (pintype "input"))
    )
    (net (code "22") (name "/ACE81_ENABLED") (class "Default")
      (node (ref "JP13") (pin "1") (pinfunction "1_1") (pintype "passive"))
      (node (ref "R29") (pin "2") (pinfunction "2_2") (pintype "passive"))
      (node (ref "R42") (pin "2") (pinfunction "2_2") (pintype "passive"))
      (node (ref "R47") (pin "2") (pinfunction "2_2") (pintype "passive"))
      (node (ref "Z1-2") (pin "1") (pinfunction "A15_1") (pintype "input"))
    )
    (net (code "23") (name "/CLK") (class "Default")
      (node (ref "C22") (pin "2") (pinfunction "2_2") (pintype "passive"))
      (node (ref "R44") (pin "E") (pinfunction "E_E") (pintype "passive"))
      (node (ref "R44") (pin "S") (pinfunction "S_S") (pintype "passive"))
      (node (ref "Z20") (pin "10") (pinfunction "I1_10") (pintype "input"))
      (node (ref "Z23") (pin "8") (pinfunction "O_8") (pintype "output"))
      (node (ref "Z9") (pin "1") (pinfunction "A_1") (pintype "input"))
    )
    (net (code "24") (name "/CNT0") (class "Default")
      (node (ref "Z22") (pin "5") (pinfunction "I2_5") (pintype "input"))
      (node (ref "Z30") (pin "4") (pinfunction "I0_4") (pintype "input"))
      (node (ref "Z30") (pin "5") (pinfunction "I1_5") (pintype "input"))
      (node (ref "Z9") (pin "3") (pinfunction "QA_3") (pintype "output"))
    )
    (net (code "25") (name "/CNT1") (class "Default")
      (node (ref "Z22") (pin "4") (pinfunction "I1_4") (pintype "input"))
      (node (ref "Z9") (pin "4") (pinfunction "QB_4") (pintype "output"))
    )
    (net (code "26") (name "/CNT2") (class "Default")
      (node (ref "Z22") (pin "3") (pinfunction "I0_3") (pintype "input"))
      (node (ref "Z41") (pin "5") (pinfunction "I1_5") (pintype "input"))
      (node (ref "Z9") (pin "5") (pinfunction "QC_5") (pintype "output"))
    )
    (net (code "27") (name "/CNT3") (class "Default")
      (node (ref "JP5") (pin "1") (pinfunction "1_1") (pintype "passive"))
      (node (ref "Z9") (pin "13") (pinfunction "A_13") (pintype "input"))
      (node (ref "Z9") (pin "6") (pinfunction "QD_6") (pintype "output"))
    )
    (net (code "28") (name "/CNT3'") (class "Default")
      (node (ref "JP5") (pin "2") (pinfunction "2_2") (pintype "passive"))
      (node (ref "R11") (pin "1") (pinfunction "1_1") (pintype "passive"))
    )
    (net (code "29") (name "/CNT4") (class "Default")
      (node (ref "JP10") (pin "1") (pinfunction "1_1") (pintype "passive"))
      (node (ref "Z10") (pin "1") (pinfunction "A_1") (pintype "input"))
      (node (ref "Z9") (pin "11") (pinfunction "QA_11") (pintype "output"))
    )
    (net (code "30") (name "/CNT4'") (class "Default")
      (node (ref "JP10") (pin "2") (pinfunction "2_2") (pintype "passive"))
      (node (ref "R12") (pin "1") (pinfunction "1_1") (pintype "passive"))
    )
    (net (code "31") (name "/CNT5") (class "Default")
      (node (ref "JP10") (pin "3") (pinfunction "1_3") (pintype "passive"))
      (node (ref "Z10") (pin "3") (pinfunction "QA_3") (pintype "output"))
      (node (ref "Z21") (pin "11") (pinfunction "I2_11") (pintype "input"))
      (node (ref "Z25") (pin "11") (pinfunction "I0_11") (pintype "input"))
      (node (ref "Z41") (pin "2") (pinfunction "I1_2") (pintype "input"))
    )
    (net (code "32") (name "/CNT5'") (class "Default")
      (node (ref "JP10") (pin "4") (pinfunction "2_4") (pintype "passive"))
      (node (ref "R13") (pin "1") (pinfunction "1_1") (pintype "passive"))
    )
    (net (code "33") (name "/CNT6") (class "Default")
      (node (ref "JP10") (pin "5") (pinfunction "1_5") (pintype "passive"))
      (node (ref "Z10") (pin "4") (pinfunction "QB_4") (pintype "output"))
      (node (ref "Z22") (pin "1") (pinfunction "I0_1") (pintype "input"))
    )
    (net (code "34") (name "/CNT6'") (class "Default")
      (node (ref "JP10") (pin "6") (pinfunction "2_6") (pintype "passive"))
      (node (ref "R14") (pin "1") (pinfunction "1_1") (pintype "passive"))
    )
    (net (code "35") (name "/CNT7") (class "Default")
      (node (ref "JP10") (pin "7") (pinfunction "1_7") (pintype "passive"))
      (node (ref "Z10") (pin "5") (pinfunction "QC_5") (pintype "output"))
      (node (ref "Z21") (pin "10") (pinfunction "I1_10") (pintype "input"))
      (node (ref "Z25") (pin "12") (pinfunction "I1_12") (pintype "input"))
    )
    (net (code "36") (name "/CNT7'") (class "Default")
      (node (ref "JP10") (pin "8") (pinfunction "2_8") (pintype "passive"))
      (node (ref "R15") (pin "1") (pinfunction "1_1") (pintype "passive"))
    )
    (net (code "37") (name "/CNT8") (class "Default")
      (node (ref "Z10") (pin "13") (pinfunction "A_13") (pintype "input"))
      (node (ref "Z10") (pin "6") (pinfunction "QD_6") (pintype "output"))
      (node (ref "Z21") (pin "9") (pinfunction "I0_9") (pintype "input"))
      (node (ref "Z22") (pin "13") (pinfunction "I2_13") (pintype "input"))
      (node (ref "Z25") (pin "2") (pinfunction "I0_2") (pintype "input"))
    )
    (net (code "38") (name "/CNT9") (class "Default")
      (node (ref "JP18") (pin "2") (pinfunction "2_2") (pintype "passive"))
      (node (ref "R21") (pin "1") (pinfunction "1_1") (pintype "passive"))
      (node (ref "Z10") (pin "11") (pinfunction "QA_11") (pintype "output"))
    )
    (net (code "39") (name "/CNT10") (class "Default")
      (node (ref "JP18") (pin "1") (pinfunction "1_1") (pintype "passive"))
      (node (ref "R22") (pin "1") (pinfunction "1_1") (pintype "passive"))
      (node (ref "Z10") (pin "10") (pinfunction "QB_10") (pintype "output"))
    )
    (net (code "40") (name "/CNT11") (class "Default")
      (node (ref "JP17") (pin "2") (pinfunction "2_2") (pintype "passive"))
      (node (ref "Z10") (pin "9") (pinfunction "QC_9") (pintype "output"))
      (node (ref "Z11") (pin "1") (pinfunction "A_1") (pintype "input"))
    )
    (net (code "41") (name "/CNT12") (class "Default")
      (node (ref "JP15") (pin "1") (pinfunction "1_1") (pintype "passive"))
      (node (ref "Z11") (pin "3") (pinfunction "QA_3") (pintype "output"))
      (node (ref "Z21") (pin "3") (pinfunction "I0_3") (pintype "input"))
    )
    (net (code "42") (name "/CNT12'") (class "Default")
      (node (ref "JP15") (pin "2") (pinfunction "2_2") (pintype "passive"))
      (node (ref "R16") (pin "1") (pinfunction "1_1") (pintype "passive"))
    )
    (net (code "43") (name "/CNT13") (class "Default")
      (node (ref "JP15") (pin "3") (pinfunction "1_3") (pintype "passive"))
      (node (ref "Z11") (pin "4") (pinfunction "QB_4") (pintype "output"))
      (node (ref "Z21") (pin "4") (pinfunction "I1_4") (pintype "input"))
    )
    (net (code "44") (name "/CNT13'") (class "Default")
      (node (ref "JP15") (pin "4") (pinfunction "2_4") (pintype "passive"))
      (node (ref "R17") (pin "1") (pinfunction "1_1") (pintype "passive"))
    )
    (net (code "45") (name "/CNT14") (class "Default")
      (node (ref "JP15") (pin "5") (pinfunction "1_5") (pintype "passive"))
      (node (ref "Z11") (pin "5") (pinfunction "QC_5") (pintype "output"))
      (node (ref "Z21") (pin "5") (pinfunction "I2_5") (pintype "input"))
    )
    (net (code "46") (name "/CNT14'") (class "Default")
      (node (ref "JP15") (pin "6") (pinfunction "2_6") (pintype "passive"))
      (node (ref "R18") (pin "1") (pinfunction "1_1") (pintype "passive"))
    )
    (net (code "47") (name "/CNT15") (class "Default")
      (node (ref "JP15") (pin "7") (pinfunction "1_7") (pintype "passive"))
      (node (ref "Z11") (pin "13") (pinfunction "A_13") (pintype "input"))
      (node (ref "Z11") (pin "6") (pinfunction "QD_6") (pintype "output"))
      (node (ref "Z19") (pin "1") (pinfunction "I0_1") (pintype "input"))
      (node (ref "Z21") (pin "1") (pinfunction "I0_1") (pintype "input"))
    )
    (net (code "48") (name "/CNT15'") (class "Default")
      (node (ref "JP15") (pin "8") (pinfunction "2_8") (pintype "passive"))
      (node (ref "R19") (pin "1") (pinfunction "1_1") (pintype "passive"))
    )
    (net (code "49") (name "/CNT16") (class "Default")
      (node (ref "JP15") (pin "9") (pinfunction "1_9") (pintype "passive"))
      (node (ref "Z11") (pin "11") (pinfunction "QA_11") (pintype "output"))
      (node (ref "Z19") (pin "2") (pinfunction "I1_2") (pintype "input"))
      (node (ref "Z21") (pin "2") (pinfunction "I1_2") (pintype "input"))
    )
    (net (code "50") (name "/CNT16'") (class "Default")
      (node (ref "JP15") (pin "10") (pinfunction "2_10") (pintype "passive"))
      (node (ref "R20") (pin "1") (pinfunction "1_1") (pintype "passive"))
    )
    (net (code "51") (name "/CNT17") (class "Default")
      (node (ref "Z11") (pin "10") (pinfunction "QB_10") (pintype "output"))
      (node (ref "Z20") (pin "2") (pinfunction "I1_2") (pintype "input"))
      (node (ref "Z25") (pin "3") (pinfunction "I1_3") (pintype "input"))
    )
    (net (code "52") (name "/D0") (class "Default")
      (node (ref "20B") (pin "1") (pinfunction "P_1") (pintype "passive"))
      (node (ref "JP2") (pin "14") (pinfunction "14_14") (pintype "passive"))
      (node (ref "R100") (pin "1") (pinfunction "1_1") (pintype "passive"))
      (node (ref "R200") (pin "1") (pinfunction "1_1") (pintype "passive"))
      (node (ref "Z0") (pin "14") (pinfunction "D0_14") (pintype "bidirectional"))
      (node (ref "Z1-2") (pin "11") (pinfunction "I/O0_11") (pintype "tri_state"))
      (node (ref "Z14") (pin "3") (pinfunction "1Y1_3") (pintype "tri_state"))
      (node (ref "Z3-4") (pin "11") (pinfunction "DQ0_11") (pintype "bidirectional"))
    )
    (net (code "53") (name "/D1") (class "Default")
      (node (ref "20A") (pin "1") (pinfunction "P_1") (pintype "passive"))
      (node (ref "JP2") (pin "15") (pinfunction "15_15") (pintype "passive"))
      (node (ref "R101") (pin "1") (pinfunction "1_1") (pintype "passive"))
      (node (ref "R201") (pin "1") (pinfunction "1_1") (pintype "passive"))
      (node (ref "Z0") (pin "15") (pinfunction "D1_15") (pintype "bidirectional"))
      (node (ref "Z1-2") (pin "12") (pinfunction "I/O1_12") (pintype "tri_state"))
      (node (ref "Z14") (pin "5") (pinfunction "1Y2_5") (pintype "tri_state"))
      (node (ref "Z3-4") (pin "12") (pinfunction "DQ1_12") (pintype "bidirectional"))
    )
    (net (code "54") (name "/D2") (class "Default")
      (node (ref "21B") (pin "1") (pinfunction "P_1") (pintype "passive"))
      (node (ref "JP2") (pin "12") (pinfunction "12_12") (pintype "passive"))
      (node (ref "R102") (pin "1") (pinfunction "1_1") (pintype "passive"))
      (node (ref "R202") (pin "1") (pinfunction "1_1") (pintype "passive"))
      (node (ref "Z0") (pin "12") (pinfunction "D2_12") (pintype "bidirectional"))
      (node (ref "Z1-2") (pin "13") (pinfunction "I/O2_13") (pintype "tri_state"))
      (node (ref "Z14") (pin "7") (pinfunction "1Y3_7") (pintype "tri_state"))
      (node (ref "Z3-4") (pin "13") (pinfunction "DQ2_13") (pintype "bidirectional"))
    )
    (net (code "55") (name "/D3") (class "Default")
      (node (ref "12A") (pin "1") (pinfunction "P_1") (pintype "passive"))
      (node (ref "JP2") (pin "8") (pinfunction "8_8") (pintype "passive"))
      (node (ref "R103") (pin "1") (pinfunction "1_1") (pintype "passive"))
      (node (ref "R203") (pin "1") (pinfunction "1_1") (pintype "passive"))
      (node (ref "Z0") (pin "8") (pinfunction "D3_8") (pintype "bidirectional"))
      (node (ref "Z1-2") (pin "15") (pinfunction "I/O3_15") (pintype "tri_state"))
      (node (ref "Z14") (pin "9") (pinfunction "1Y4_9") (pintype "tri_state"))
      (node (ref "Z27") (pin "2") (pinfunction "D_2") (pintype "input"))
      (node (ref "Z3-4") (pin "15") (pinfunction "DQ3_15") (pintype "bidirectional"))
    )
    (net (code "56") (name "/D4") (class "Default")
      (node (ref "11A") (pin "1") (pinfunction "P_1") (pintype "passive"))
      (node (ref "JP2") (pin "7") (pinfunction "7_7") (pintype "passive"))
      (node (ref "R104") (pin "1") (pinfunction "1_1") (pintype "passive"))
      (node (ref "R204") (pin "1") (pinfunction "1_1") (pintype "passive"))
      (node (ref "Z0") (pin "7") (pinfunction "D4_7") (pintype "bidirectional"))
      (node (ref "Z1-2") (pin "16") (pinfunction "I/O4_16") (pintype "tri_state"))
      (node (ref "Z14") (pin "11") (pinfunction "2Y1_11") (pintype "tri_state"))
      (node (ref "Z3-4") (pin "16") (pinfunction "DQ4_16") (pintype "bidirectional"))
    )
    (net (code "57") (name "/D5") (class "Default")
      (node (ref "13A") (pin "1") (pinfunction "P_1") (pintype "passive"))
      (node (ref "JP2") (pin "9") (pinfunction "9_9") (pintype "passive"))
      (node (ref "R105") (pin "1") (pinfunction "1_1") (pintype "passive"))
      (node (ref "R205") (pin "1") (pinfunction "1_1") (pintype "passive"))
      (node (ref "Z0") (pin "9") (pinfunction "D5_9") (pintype "bidirectional"))
      (node (ref "Z1-2") (pin "17") (pinfunction "I/O5_17") (pintype "tri_state"))
      (node (ref "Z14") (pin "13") (pinfunction "2Y2_13") (pintype "tri_state"))
      (node (ref "Z3-4") (pin "17") (pinfunction "DQ5_17") (pintype "bidirectional"))
    )
    (net (code "58") (name "/D6") (class "Default")
      (node (ref "21A") (pin "1") (pinfunction "P_1") (pintype "passive"))
      (node (ref "JP2") (pin "10") (pinfunction "10_10") (pintype "passive"))
      (node (ref "R106") (pin "1") (pinfunction "1_1") (pintype "passive"))
      (node (ref "R206") (pin "1") (pinfunction "1_1") (pintype "passive"))
      (node (ref "Z0") (pin "10") (pinfunction "D6_10") (pintype "bidirectional"))
      (node (ref "Z1-2") (pin "18") (pinfunction "I/O6_18") (pintype "tri_state"))
      (node (ref "Z3-4") (pin "18") (pinfunction "DQ6_18") (pintype "bidirectional"))
    )
    (net (code "59") (name "/D7") (class "Default")
      (node (ref "22B") (pin "1") (pinfunction "P_1") (pintype "passive"))
      (node (ref "JP2") (pin "13") (pinfunction "13_13") (pintype "passive"))
      (node (ref "R107") (pin "1") (pinfunction "1_1") (pintype "passive"))
      (node (ref "R207") (pin "1") (pinfunction "1_1") (pintype "passive"))
      (node (ref "Z0") (pin "13") (pinfunction "D7_13") (pintype "bidirectional"))
      (node (ref "Z1-2") (pin "19") (pinfunction "I/O7_19") (pintype "tri_state"))
      (node (ref "Z3-4") (pin "19") (pinfunction "DQ7_19") (pintype "bidirectional"))
    )
    (net (code "60") (name "/EAR") (class "Default")
      (node (ref "Z14") (pin "14") (pinfunction "2A2_14") (pintype "input"))
      (node (ref "Z18") (pin "13") (pinfunction "2Y2_13") (pintype "tri_state"))
    )
    (net (code "61") (name "/FIELD") (class "Default")
      (node (ref "Z19") (pin "12") (pinfunction "I0_12") (pintype "input"))
      (node (ref "Z21") (pin "12") (pinfunction "O_12") (pintype "output"))
      (node (ref "Z25") (pin "6") (pinfunction "I1_6") (pintype "input"))
    )
    (net (code "62") (name "/INV_BIT") (class "Default")
      (node (ref "JP4") (pin "1") (pinfunction "1_1") (pintype "passive"))
      (node (ref "Z27") (pin "9") (pinfunction "Q_9") (pintype "output"))
    )
    (net (code "63") (name "/KB") (class "Default")
      (node (ref "JP16") (pin "12") (pinfunction "12_12") (pintype "passive"))
      (node (ref "JP16") (pin "5") (pinfunction "5_5") (pintype "passive"))
      (node (ref "K37") (pin "3") (pinfunction "P_3") (pintype "passive"))
      (node (ref "K37") (pin "4") (pinfunction "P1_4") (pintype "passive"))
      (node (ref "U$37") (pin "P$2") (pinfunction "2_P$2") (pintype "passive"))
    )
    (net (code "64") (name "/KC") (class "Default")
      (node (ref "JP16") (pin "7") (pinfunction "7_7") (pintype "passive"))
      (node (ref "K35") (pin "3") (pinfunction "P_3") (pintype "passive"))
      (node (ref "K35") (pin "4") (pinfunction "P1_4") (pintype "passive"))
      (node (ref "U$35") (pin "P$2") (pinfunction "2_P$2") (pintype "passive"))
    )
    (net (code "65") (name "/KEYB1") (class "Default")
      (node (ref "K1") (pin "3") (pinfunction "P_3") (pintype "passive"))
      (node (ref "K1") (pin "4") (pinfunction "P1_4") (pintype "passive"))
      (node (ref "K10") (pin "3") (pinfunction "P_3") (pintype "passive"))
      (node (ref "K10") (pin "4") (pinfunction "P1_4") (pintype "passive"))
      (node (ref "K11") (pin "3") (pinfunction "P_3") (pintype "passive"))
      (node (ref "K11") (pin "4") (pinfunction "P1_4") (pintype "passive"))
      (node (ref "K20") (pin "3") (pinfunction "P_3") (pintype "passive"))
      (node (ref "K20") (pin "4") (pinfunction "P1_4") (pintype "passive"))
      (node (ref "K21") (pin "3") (pinfunction "P_3") (pintype "passive"))
      (node (ref "K21") (pin "4") (pinfunction "P1_4") (pintype "passive"))
      (node (ref "K30") (pin "3") (pinfunction "P_3") (pintype "passive"))
      (node (ref "K30") (pin "4") (pinfunction "P1_4") (pintype "passive"))
      (node (ref "K31") (pin "3") (pinfunction "P_3") (pintype "passive"))
      (node (ref "K31") (pin "4") (pinfunction "P1_4") (pintype "passive"))
      (node (ref "K40") (pin "3") (pinfunction "P_3") (pintype "passive"))
      (node (ref "K40") (pin "4") (pinfunction "P1_4") (pintype "passive"))
      (node (ref "K41") (pin "3") (pinfunction "P_3") (pintype "passive"))
      (node (ref "K41") (pin "4") (pinfunction "P1_4") (pintype "passive"))
      (node (ref "R36") (pin "1") (pinfunction "1_1") (pintype "passive"))
      (node (ref "RN1") (pin "6") (pinfunction "6_6") (pintype "passive"))
      (node (ref "U$1") (pin "P$2") (pinfunction "2_P$2") (pintype "passive"))
      (node (ref "U$10") (pin "P$2") (pinfunction "2_P$2") (pintype "passive"))
      (node (ref "U$11") (pin "P$2") (pinfunction "2_P$2") (pintype "passive"))
      (node (ref "U$20") (pin "P$2") (pinfunction "2_P$2") (pintype "passive"))
      (node (ref "U$21") (pin "P$2") (pinfunction "2_P$2") (pintype "passive"))
      (node (ref "U$30") (pin "P$2") (pinfunction "2_P$2") (pintype "passive"))
      (node (ref "U$31") (pin "P$2") (pinfunction "2_P$2") (pintype "passive"))
      (node (ref "U$40") (pin "P$2") (pinfunction "2_P$2") (pintype "passive"))
      (node (ref "U$41") (pin "P$2") (pinfunction "2_P$2") (pintype "passive"))
      (node (ref "U$42") (pin "P$2") (pinfunction "2_P$2") (pintype "passive"))
      (node (ref "Z14") (pin "2") (pinfunction "1A1_2") (pintype "input"))
    )
    (net (code "66") (name "/KEYB2") (class "Default")
      (node (ref "JP16") (pin "2") (pinfunction "2_2") (pintype "passive"))
      (node (ref "K12") (pin "3") (pinfunction "P_3") (pintype "passive"))
      (node (ref "K12") (pin "4") (pinfunction "P1_4") (pintype "passive"))
      (node (ref "K19") (pin "3") (pinfunction "P_3") (pintype "passive"))
      (node (ref "K19") (pin "4") (pinfunction "P1_4") (pintype "passive"))
      (node (ref "K2") (pin "3") (pinfunction "P_3") (pintype "passive"))
      (node (ref "K2") (pin "4") (pinfunction "P1_4") (pintype "passive"))
      (node (ref "K22") (pin "3") (pinfunction "P_3") (pintype "passive"))
      (node (ref "K22") (pin "4") (pinfunction "P1_4") (pintype "passive"))
      (node (ref "K29") (pin "3") (pinfunction "P_3") (pintype "passive"))
      (node (ref "K29") (pin "4") (pinfunction "P1_4") (pintype "passive"))
      (node (ref "K32") (pin "3") (pinfunction "P_3") (pintype "passive"))
      (node (ref "K32") (pin "4") (pinfunction "P1_4") (pintype "passive"))
      (node (ref "K9") (pin "3") (pinfunction "P_3") (pintype "passive"))
      (node (ref "K9") (pin "4") (pinfunction "P1_4") (pintype "passive"))
      (node (ref "R37") (pin "1") (pinfunction "1_1") (pintype "passive"))
      (node (ref "RN1") (pin "5") (pinfunction "5_5") (pintype "passive"))
      (node (ref "U$12") (pin "P$2") (pinfunction "2_P$2") (pintype "passive"))
      (node (ref "U$19") (pin "P$2") (pinfunction "2_P$2") (pintype "passive"))
      (node (ref "U$2") (pin "P$2") (pinfunction "2_P$2") (pintype "passive"))
      (node (ref "U$22") (pin "P$2") (pinfunction "2_P$2") (pintype "passive"))
      (node (ref "U$29") (pin "P$2") (pinfunction "2_P$2") (pintype "passive"))
      (node (ref "U$32") (pin "P$2") (pinfunction "2_P$2") (pintype "passive"))
      (node (ref "U$9") (pin "P$2") (pinfunction "2_P$2") (pintype "passive"))
      (node (ref "Z14") (pin "4") (pinfunction "1A2_4") (pintype "input"))
    )
    (net (code "67") (name "/KEYB3") (class "Default")
      (node (ref "JP16") (pin "4") (pinfunction "4_4") (pintype "passive"))
      (node (ref "K13") (pin "3") (pinfunction "P_3") (pintype "passive"))
      (node (ref "K13") (pin "4") (pinfunction "P1_4") (pintype "passive"))
      (node (ref "K18") (pin "3") (pinfunction "P_3") (pintype "passive"))
      (node (ref "K18") (pin "4") (pinfunction "P1_4") (pintype "passive"))
      (node (ref "K23") (pin "3") (pinfunction "P_3") (pintype "passive"))
      (node (ref "K23") (pin "4") (pinfunction "P1_4") (pintype "passive"))
      (node (ref "K28") (pin "3") (pinfunction "P_3") (pintype "passive"))
      (node (ref "K28") (pin "4") (pinfunction "P1_4") (pintype "passive"))
      (node (ref "K3") (pin "3") (pinfunction "P_3") (pintype "passive"))
      (node (ref "K3") (pin "4") (pinfunction "P1_4") (pintype "passive"))
      (node (ref "K8") (pin "3") (pinfunction "P_3") (pintype "passive"))
      (node (ref "K8") (pin "4") (pinfunction "P1_4") (pintype "passive"))
      (node (ref "R38") (pin "1") (pinfunction "1_1") (pintype "passive"))
      (node (ref "RN1") (pin "4") (pinfunction "4_4") (pintype "passive"))
      (node (ref "U$13") (pin "P$2") (pinfunction "2_P$2") (pintype "passive"))
      (node (ref "U$18") (pin "P$2") (pinfunction "2_P$2") (pintype "passive"))
      (node (ref "U$23") (pin "P$2") (pinfunction "2_P$2") (pintype "passive"))
      (node (ref "U$28") (pin "P$2") (pinfunction "2_P$2") (pintype "passive"))
      (node (ref "U$3") (pin "P$2") (pinfunction "2_P$2") (pintype "passive"))
      (node (ref "U$8") (pin "P$2") (pinfunction "2_P$2") (pintype "passive"))
      (node (ref "Z14") (pin "6") (pinfunction "1A3_6") (pintype "input"))
    )
    (net (code "68") (name "/KEYB4") (class "Default")
      (node (ref "JP16") (pin "6") (pinfunction "6_6") (pintype "passive"))
      (node (ref "K14") (pin "3") (pinfunction "P_3") (pintype "passive"))
      (node (ref "K14") (pin "4") (pinfunction "P1_4") (pintype "passive"))
      (node (ref "K17") (pin "3") (pinfunction "P_3") (pintype "passive"))
      (node (ref "K17") (pin "4") (pinfunction "P1_4") (pintype "passive"))
      (node (ref "K24") (pin "3") (pinfunction "P_3") (pintype "passive"))
      (node (ref "K24") (pin "4") (pinfunction "P1_4") (pintype "passive"))
      (node (ref "K27") (pin "3") (pinfunction "P_3") (pintype "passive"))
      (node (ref "K27") (pin "4") (pinfunction "P1_4") (pintype "passive"))
      (node (ref "K4") (pin "3") (pinfunction "P_3") (pintype "passive"))
      (node (ref "K4") (pin "4") (pinfunction "P1_4") (pintype "passive"))
      (node (ref "K7") (pin "3") (pinfunction "P_3") (pintype "passive"))
      (node (ref "K7") (pin "4") (pinfunction "P1_4") (pintype "passive"))
      (node (ref "R40") (pin "1") (pinfunction "1_1") (pintype "passive"))
      (node (ref "RN1") (pin "3") (pinfunction "3_3") (pintype "passive"))
      (node (ref "U$14") (pin "P$2") (pinfunction "2_P$2") (pintype "passive"))
      (node (ref "U$17") (pin "P$2") (pinfunction "2_P$2") (pintype "passive"))
      (node (ref "U$24") (pin "P$2") (pinfunction "2_P$2") (pintype "passive"))
      (node (ref "U$27") (pin "P$2") (pinfunction "2_P$2") (pintype "passive"))
      (node (ref "U$4") (pin "P$2") (pinfunction "2_P$2") (pintype "passive"))
      (node (ref "U$7") (pin "P$2") (pinfunction "2_P$2") (pintype "passive"))
      (node (ref "Z14") (pin "10") (pinfunction "1A4_10") (pintype "input"))
    )
    (net (code "69") (name "/KEYB5") (class "Default")
      (node (ref "JP16") (pin "8") (pinfunction "8_8") (pintype "passive"))
      (node (ref "K15") (pin "3") (pinfunction "P_3") (pintype "passive"))
      (node (ref "K15") (pin "4") (pinfunction "P1_4") (pintype "passive"))
      (node (ref "K16") (pin "3") (pinfunction "P_3") (pintype "passive"))
      (node (ref "K16") (pin "4") (pinfunction "P1_4") (pintype "passive"))
      (node (ref "K25") (pin "3") (pinfunction "P_3") (pintype "passive"))
      (node (ref "K25") (pin "4") (pinfunction "P1_4") (pintype "passive"))
      (node (ref "K26") (pin "3") (pinfunction "P_3") (pintype "passive"))
      (node (ref "K26") (pin "4") (pinfunction "P1_4") (pintype "passive"))
      (node (ref "K36") (pin "3") (pinfunction "P_3") (pintype "passive"))
      (node (ref "K36") (pin "4") (pinfunction "P1_4") (pintype "passive"))
      (node (ref "K5") (pin "3") (pinfunction "P_3") (pintype "passive"))
      (node (ref "K5") (pin "4") (pinfunction "P1_4") (pintype "passive"))
      (node (ref "K6") (pin "3") (pinfunction "P_3") (pintype "passive"))
      (node (ref "K6") (pin "4") (pinfunction "P1_4") (pintype "passive"))
      (node (ref "R41") (pin "1") (pinfunction "1_1") (pintype "passive"))
      (node (ref "RN1") (pin "2") (pinfunction "2_2") (pintype "passive"))
      (node (ref "U$15") (pin "P$2") (pinfunction "2_P$2") (pintype "passive"))
      (node (ref "U$16") (pin "P$2") (pinfunction "2_P$2") (pintype "passive"))
      (node (ref "U$25") (pin "P$2") (pinfunction "2_P$2") (pintype "passive"))
      (node (ref "U$26") (pin "P$2") (pinfunction "2_P$2") (pintype "passive"))
      (node (ref "U$36") (pin "P$2") (pinfunction "2_P$2") (pintype "passive"))
      (node (ref "U$5") (pin "P$2") (pinfunction "2_P$2") (pintype "passive"))
      (node (ref "U$6") (pin "P$2") (pinfunction "2_P$2") (pintype "passive"))
      (node (ref "Z14") (pin "12") (pinfunction "2A1_12") (pintype "input"))
    )
    (net (code "70") (name "/KM") (class "Default")
      (node (ref "JP16") (pin "1") (pinfunction "1_1") (pintype "passive"))
      (node (ref "K39") (pin "3") (pinfunction "P_3") (pintype "passive"))
      (node (ref "K39") (pin "4") (pinfunction "P1_4") (pintype "passive"))
      (node (ref "U$39") (pin "P$2") (pinfunction "2_P$2") (pintype "passive"))
    )
    (net (code "71") (name "/KN") (class "Default")
      (node (ref "JP16") (pin "3") (pinfunction "3_3") (pintype "passive"))
      (node (ref "JP16") (pin "9") (pinfunction "9_9") (pintype "passive"))
      (node (ref "K38") (pin "3") (pinfunction "P_3") (pintype "passive"))
      (node (ref "K38") (pin "4") (pinfunction "P1_4") (pintype "passive"))
      (node (ref "U$38") (pin "P$2") (pinfunction "2_P$2") (pintype "passive"))
    )
    (net (code "72") (name "/KX") (class "Default")
      (node (ref "JP16") (pin "11") (pinfunction "11_11") (pintype "passive"))
      (node (ref "K34") (pin "3") (pinfunction "P_3") (pintype "passive"))
      (node (ref "K34") (pin "4") (pinfunction "P1_4") (pintype "passive"))
      (node (ref "U$34") (pin "P$2") (pinfunction "2_P$2") (pintype "passive"))
    )
    (net (code "73") (name "/KZ") (class "Default")
      (node (ref "JP16") (pin "10") (pinfunction "10_10") (pintype "passive"))
      (node (ref "K33") (pin "3") (pinfunction "P_3") (pintype "passive"))
      (node (ref "K33") (pin "4") (pinfunction "P1_4") (pintype "passive"))
      (node (ref "U$33") (pin "P$2") (pinfunction "2_P$2") (pintype "passive"))
    )
    (net (code "74") (name "/LINE") (class "Default")
      (node (ref "Z22") (pin "12") (pinfunction "O_12") (pintype "output"))
      (node (ref "Z25") (pin "5") (pinfunction "I0_5") (pintype "input"))
    )
    (net (code "75") (name "/N$56") (class "Default")
      (node (ref "JP6") (pin "2") (pinfunction "2_2") (pintype "passive"))
      (node (ref "R42") (pin "1") (pinfunction "1_1") (pintype "passive"))
    )
    (net (code "76") (name "/NC1") (class "Default")
      (node (ref "24A") (pin "1") (pinfunction "P_1") (pintype "passive"))
    )
    (net (code "77") (name "/NC2") (class "Default")
      (node (ref "25A") (pin "1") (pinfunction "P_1") (pintype "passive"))
    )
    (net (code "78") (name "/NC3") (class "Default")
      (node (ref "24B") (pin "1") (pinfunction "P_1") (pintype "passive"))
    )
    (net (code "79") (name "/NC4") (class "Default")
      (node (ref "25B") (pin "1") (pinfunction "P_1") (pintype "passive"))
    )
    (net (code "80") (name "/PHI") (class "Default")
      (node (ref "5A") (pin "1") (pinfunction "P_1") (pintype "passive"))
      (node (ref "JP2") (pin "6") (pinfunction "6_6") (pintype "passive"))
      (node (ref "Z0") (pin "6") (pinfunction "CLK_6") (pintype "input"))
      (node (ref "Z30") (pin "6") (pinfunction "O_6") (pintype "output"))
    )
    (net (code "81") (name "/RESET") (class "Default")
      (node (ref "12B") (pin "1") (pinfunction "P_1") (pintype "passive"))
      (node (ref "C7") (pin "+") (pinfunction "+_+") (pintype "passive"))
      (node (ref "JP9") (pin "15") (pinfunction "15_15") (pintype "passive"))
      (node (ref "R25") (pin "1") (pinfunction "1_1") (pintype "passive"))
      (node (ref "S2") (pin "2") (pinfunction "S_2") (pintype "passive"))
      (node (ref "Z0") (pin "26") (pinfunction "RESET_26") (pintype "input"))
    )
    (net (code "82") (name "/ROMA13") (class "Default")
      (node (ref "JP13") (pin "3") (pinfunction "3_3") (pintype "passive"))
      (node (ref "R45") (pin "2") (pinfunction "2_2") (pintype "passive"))
      (node (ref "Z1-2") (pin "26") (pinfunction "A13_26") (pintype "input"))
    )
    (net (code "83") (name "/ROMA14") (class "Default")
      (node (ref "JP13") (pin "2") (pinfunction "2_2") (pintype "passive"))
      (node (ref "R46") (pin "2") (pinfunction "2_2") (pintype "passive"))
      (node (ref "Z1-2") (pin "27") (pinfunction "A14_27") (pintype "input"))
    )
    (net (code "84") (name "/ROW1") (class "Default")
      (node (ref "D10") (pin "A") (pinfunction "A_A") (pintype "passive"))
      (node (ref "JP1") (pin "1") (pinfunction "1_1") (pintype "passive"))
      (node (ref "JP16") (pin "13") (pinfunction "13_13") (pintype "passive"))
      (node (ref "K31") (pin "1") (pinfunction "S_1") (pintype "passive"))
      (node (ref "K31") (pin "2") (pinfunction "S1_2") (pintype "passive"))
      (node (ref "K33") (pin "1") (pinfunction "S_1") (pintype "passive"))
      (node (ref "K33") (pin "2") (pinfunction "S1_2") (pintype "passive"))
      (node (ref "K34") (pin "1") (pinfunction "S_1") (pintype "passive"))
      (node (ref "K34") (pin "2") (pinfunction "S1_2") (pintype "passive"))
      (node (ref "K35") (pin "1") (pinfunction "S_1") (pintype "passive"))
      (node (ref "K35") (pin "2") (pinfunction "S1_2") (pintype "passive"))
      (node (ref "U$31") (pin "P$1") (pinfunction "1_P$1") (pintype "passive"))
      (node (ref "U$33") (pin "P$1") (pinfunction "1_P$1") (pintype "passive"))
      (node (ref "U$34") (pin "P$1") (pinfunction "1_P$1") (pintype "passive"))
      (node (ref "U$35") (pin "P$1") (pinfunction "1_P$1") (pintype "passive"))
    )
    (net (code "85") (name "/ROW2") (class "Default")
      (node (ref "D9") (pin "A") (pinfunction "A_A") (pintype "passive"))
      (node (ref "JP1") (pin "2") (pinfunction "2_2") (pintype "passive"))
      (node (ref "K21") (pin "1") (pinfunction "S_1") (pintype "passive"))
      (node (ref "K21") (pin "2") (pinfunction "S1_2") (pintype "passive"))
      (node (ref "K22") (pin "1") (pinfunction "S_1") (pintype "passive"))
      (node (ref "K22") (pin "2") (pinfunction "S1_2") (pintype "passive"))
      (node (ref "K23") (pin "1") (pinfunction "S_1") (pintype "passive"))
      (node (ref "K23") (pin "2") (pinfunction "S1_2") (pintype "passive"))
      (node (ref "K24") (pin "1") (pinfunction "S_1") (pintype "passive"))
      (node (ref "K24") (pin "2") (pinfunction "S1_2") (pintype "passive"))
      (node (ref "K25") (pin "1") (pinfunction "S_1") (pintype "passive"))
      (node (ref "K25") (pin "2") (pinfunction "S1_2") (pintype "passive"))
      (node (ref "U$21") (pin "P$1") (pinfunction "1_P$1") (pintype "passive"))
      (node (ref "U$22") (pin "P$1") (pinfunction "1_P$1") (pintype "passive"))
      (node (ref "U$23") (pin "P$1") (pinfunction "1_P$1") (pintype "passive"))
      (node (ref "U$24") (pin "P$1") (pinfunction "1_P$1") (pintype "passive"))
      (node (ref "U$25") (pin "P$1") (pinfunction "1_P$1") (pintype "passive"))
    )
    (net (code "86") (name "/ROW3") (class "Default")
      (node (ref "D8") (pin "A") (pinfunction "A_A") (pintype "passive"))
      (node (ref "JP1") (pin "3") (pinfunction "3_3") (pintype "passive"))
      (node (ref "K11") (pin "1") (pinfunction "S_1") (pintype "passive"))
      (node (ref "K11") (pin "2") (pinfunction "S1_2") (pintype "passive"))
      (node (ref "K12") (pin "1") (pinfunction "S_1") (pintype "passive"))
      (node (ref "K12") (pin "2") (pinfunction "S1_2") (pintype "passive"))
      (node (ref "K13") (pin "1") (pinfunction "S_1") (pintype "passive"))
      (node (ref "K13") (pin "2") (pinfunction "S1_2") (pintype "passive"))
      (node (ref "K14") (pin "1") (pinfunction "S_1") (pintype "passive"))
      (node (ref "K14") (pin "2") (pinfunction "S1_2") (pintype "passive"))
      (node (ref "K15") (pin "1") (pinfunction "S_1") (pintype "passive"))
      (node (ref "K15") (pin "2") (pinfunction "S1_2") (pintype "passive"))
      (node (ref "U$11") (pin "P$1") (pinfunction "1_P$1") (pintype "passive"))
      (node (ref "U$12") (pin "P$1") (pinfunction "1_P$1") (pintype "passive"))
      (node (ref "U$13") (pin "P$1") (pinfunction "1_P$1") (pintype "passive"))
      (node (ref "U$14") (pin "P$1") (pinfunction "1_P$1") (pintype "passive"))
      (node (ref "U$15") (pin "P$1") (pinfunction "1_P$1") (pintype "passive"))
    )
    (net (code "87") (name "/ROW4") (class "Default")
      (node (ref "D7") (pin "A") (pinfunction "A_A") (pintype "passive"))
      (node (ref "JP1") (pin "4") (pinfunction "4_4") (pintype "passive"))
      (node (ref "K1") (pin "1") (pinfunction "S_1") (pintype "passive"))
      (node (ref "K1") (pin "2") (pinfunction "S1_2") (pintype "passive"))
      (node (ref "K2") (pin "1") (pinfunction "S_1") (pintype "passive"))
      (node (ref "K2") (pin "2") (pinfunction "S1_2") (pintype "passive"))
      (node (ref "K3") (pin "1") (pinfunction "S_1") (pintype "passive"))
      (node (ref "K3") (pin "2") (pinfunction "S1_2") (pintype "passive"))
      (node (ref "K4") (pin "1") (pinfunction "S_1") (pintype "passive"))
      (node (ref "K4") (pin "2") (pinfunction "S1_2") (pintype "passive"))
      (node (ref "K5") (pin "1") (pinfunction "S_1") (pintype "passive"))
      (node (ref "K5") (pin "2") (pinfunction "S1_2") (pintype "passive"))
      (node (ref "U$1") (pin "P$1") (pinfunction "1_P$1") (pintype "passive"))
      (node (ref "U$2") (pin "P$1") (pinfunction "1_P$1") (pintype "passive"))
      (node (ref "U$3") (pin "P$1") (pinfunction "1_P$1") (pintype "passive"))
      (node (ref "U$4") (pin "P$1") (pinfunction "1_P$1") (pintype "passive"))
      (node (ref "U$5") (pin "P$1") (pinfunction "1_P$1") (pintype "passive"))
    )
    (net (code "88") (name "/ROW5") (class "Default")
      (node (ref "D6") (pin "A") (pinfunction "A_A") (pintype "passive"))
      (node (ref "JP1") (pin "5") (pinfunction "5_5") (pintype "passive"))
      (node (ref "K10") (pin "1") (pinfunction "S_1") (pintype "passive"))
      (node (ref "K10") (pin "2") (pinfunction "S1_2") (pintype "passive"))
      (node (ref "K6") (pin "1") (pinfunction "S_1") (pintype "passive"))
      (node (ref "K6") (pin "2") (pinfunction "S1_2") (pintype "passive"))
      (node (ref "K7") (pin "1") (pinfunction "S_1") (pintype "passive"))
      (node (ref "K7") (pin "2") (pinfunction "S1_2") (pintype "passive"))
      (node (ref "K8") (pin "1") (pinfunction "S_1") (pintype "passive"))
      (node (ref "K8") (pin "2") (pinfunction "S1_2") (pintype "passive"))
      (node (ref "K9") (pin "1") (pinfunction "S_1") (pintype "passive"))
      (node (ref "K9") (pin "2") (pinfunction "S1_2") (pintype "passive"))
      (node (ref "U$10") (pin "P$1") (pinfunction "1_P$1") (pintype "passive"))
      (node (ref "U$6") (pin "P$1") (pinfunction "1_P$1") (pintype "passive"))
      (node (ref "U$7") (pin "P$1") (pinfunction "1_P$1") (pintype "passive"))
      (node (ref "U$8") (pin "P$1") (pinfunction "1_P$1") (pintype "passive"))
      (node (ref "U$9") (pin "P$1") (pinfunction "1_P$1") (pintype "passive"))
    )
    (net (code "89") (name "/ROW6") (class "Default")
      (node (ref "D5") (pin "A") (pinfunction "A_A") (pintype "passive"))
      (node (ref "JP1") (pin "6") (pinfunction "6_6") (pintype "passive"))
      (node (ref "K16") (pin "1") (pinfunction "S_1") (pintype "passive"))
      (node (ref "K16") (pin "2") (pinfunction "S1_2") (pintype "passive"))
      (node (ref "K17") (pin "1") (pinfunction "S_1") (pintype "passive"))
      (node (ref "K17") (pin "2") (pinfunction "S1_2") (pintype "passive"))
      (node (ref "K18") (pin "1") (pinfunction "S_1") (pintype "passive"))
      (node (ref "K18") (pin "2") (pinfunction "S1_2") (pintype "passive"))
      (node (ref "K19") (pin "1") (pinfunction "S_1") (pintype "passive"))
      (node (ref "K19") (pin "2") (pinfunction "S1_2") (pintype "passive"))
      (node (ref "K20") (pin "1") (pinfunction "S_1") (pintype "passive"))
      (node (ref "K20") (pin "2") (pinfunction "S1_2") (pintype "passive"))
      (node (ref "U$16") (pin "P$1") (pinfunction "1_P$1") (pintype "passive"))
      (node (ref "U$17") (pin "P$1") (pinfunction "1_P$1") (pintype "passive"))
      (node (ref "U$18") (pin "P$1") (pinfunction "1_P$1") (pintype "passive"))
      (node (ref "U$19") (pin "P$1") (pinfunction "1_P$1") (pintype "passive"))
      (node (ref "U$20") (pin "P$1") (pinfunction "1_P$1") (pintype "passive"))
    )
    (net (code "90") (name "/ROW7") (class "Default")
      (node (ref "D4") (pin "A") (pinfunction "A_A") (pintype "passive"))
      (node (ref "JP1") (pin "7") (pinfunction "7_7") (pintype "passive"))
      (node (ref "K26") (pin "1") (pinfunction "S_1") (pintype "passive"))
      (node (ref "K26") (pin "2") (pinfunction "S1_2") (pintype "passive"))
      (node (ref "K27") (pin "1") (pinfunction "S_1") (pintype "passive"))
      (node (ref "K27") (pin "2") (pinfunction "S1_2") (pintype "passive"))
      (node (ref "K28") (pin "1") (pinfunction "S_1") (pintype "passive"))
      (node (ref "K28") (pin "2") (pinfunction "S1_2") (pintype "passive"))
      (node (ref "K29") (pin "1") (pinfunction "S_1") (pintype "passive"))
      (node (ref "K29") (pin "2") (pinfunction "S1_2") (pintype "passive"))
      (node (ref "K30") (pin "1") (pinfunction "S_1") (pintype "passive"))
      (node (ref "K30") (pin "2") (pinfunction "S1_2") (pintype "passive"))
      (node (ref "U$26") (pin "P$1") (pinfunction "1_P$1") (pintype "passive"))
      (node (ref "U$27") (pin "P$1") (pinfunction "1_P$1") (pintype "passive"))
      (node (ref "U$28") (pin "P$1") (pinfunction "1_P$1") (pintype "passive"))
      (node (ref "U$29") (pin "P$1") (pinfunction "1_P$1") (pintype "passive"))
      (node (ref "U$30") (pin "P$1") (pinfunction "1_P$1") (pintype "passive"))
    )
    (net (code "91") (name "/ROW8") (class "Default")
      (node (ref "D3") (pin "A") (pinfunction "A_A") (pintype "passive"))
      (node (ref "JP1") (pin "8") (pinfunction "8_8") (pintype "passive"))
      (node (ref "JP16") (pin "15") (pinfunction "15_15") (pintype "passive"))
      (node (ref "K37") (pin "1") (pinfunction "S_1") (pintype "passive"))
      (node (ref "K37") (pin "2") (pinfunction "S1_2") (pintype "passive"))
      (node (ref "K38") (pin "1") (pinfunction "S_1") (pintype "passive"))
      (node (ref "K38") (pin "2") (pinfunction "S1_2") (pintype "passive"))
      (node (ref "K39") (pin "1") (pinfunction "S_1") (pintype "passive"))
      (node (ref "K39") (pin "2") (pinfunction "S1_2") (pintype "passive"))
      (node (ref "K40") (pin "1") (pinfunction "S_1") (pintype "passive"))
      (node (ref "K40") (pin "2") (pinfunction "S1_2") (pintype "passive"))
      (node (ref "K41") (pin "1") (pinfunction "S_1") (pintype "passive"))
      (node (ref "K41") (pin "2") (pinfunction "S1_2") (pintype "passive"))
      (node (ref "U$37") (pin "P$1") (pinfunction "1_P$1") (pintype "passive"))
      (node (ref "U$38") (pin "P$1") (pinfunction "1_P$1") (pintype "passive"))
      (node (ref "U$39") (pin "P$1") (pinfunction "1_P$1") (pintype "passive"))
      (node (ref "U$40") (pin "P$1") (pinfunction "1_P$1") (pintype "passive"))
      (node (ref "U$41") (pin "P$1") (pinfunction "1_P$1") (pintype "passive"))
      (node (ref "U$42") (pin "P$1") (pinfunction "1_P$1") (pintype "passive"))
    )
    (net (code "92") (name "/ROW_SS") (class "Default")
      (node (ref "JP16") (pin "14") (pinfunction "14_14") (pintype "passive"))
      (node (ref "K32") (pin "1") (pinfunction "S_1") (pintype "passive"))
      (node (ref "K32") (pin "2") (pinfunction "S1_2") (pintype "passive"))
      (node (ref "U$32") (pin "P$1") (pinfunction "1_P$1") (pintype "passive"))
    )
    (net (code "93") (name "/ROW_V") (class "Default")
      (node (ref "JP16") (pin "16") (pinfunction "16_16") (pintype "passive"))
      (node (ref "K36") (pin "1") (pinfunction "S_1") (pintype "passive"))
      (node (ref "K36") (pin "2") (pinfunction "S1_2") (pintype "passive"))
      (node (ref "U$36") (pin "P$1") (pinfunction "1_P$1") (pintype "passive"))
    )
    (net (code "94") (name "/SYNC") (class "Default")
      (node (ref "D1") (pin "C") (pinfunction "C_C") (pintype "passive"))
      (node (ref "Z1") (pin "13") (pinfunction "CLR_13") (pintype "input"))
      (node (ref "Z25") (pin "4") (pinfunction "O_4") (pintype "output"))
    )
    (net (code "95") (name "/VA0") (class "Default")
      (node (ref "1A1") (pin "1") (pinfunction "P_1") (pintype "passive"))
      (node (ref "R11") (pin "2") (pinfunction "2_2") (pintype "passive"))
      (node (ref "Z15") (pin "3") (pinfunction "1Y1_3") (pintype "tri_state"))
      (node (ref "Z5-6") (pin "21") (pinfunction "A0_21") (pintype "input"))
    )
    (net (code "96") (name "/VA1") (class "Default")
      (node (ref "9A1") (pin "1") (pinfunction "P_1") (pintype "passive"))
      (node (ref "R12") (pin "2") (pinfunction "2_2") (pintype "passive"))
      (node (ref "Z15") (pin "5") (pinfunction "1Y2_5") (pintype "tri_state"))
      (node (ref "Z5-6") (pin "23") (pinfunction "A1_23") (pintype "input"))
    )
    (net (code "97") (name "/VA2") (class "Default")
      (node (ref "6B2") (pin "1") (pinfunction "P_1") (pintype "passive"))
      (node (ref "R13") (pin "2") (pinfunction "2_2") (pintype "passive"))
      (node (ref "Z15") (pin "7") (pinfunction "1Y3_7") (pintype "tri_state"))
      (node (ref "Z5-6") (pin "24") (pinfunction "A2_24") (pintype "input"))
    )
    (net (code "98") (name "/VA3") (class "Default")
      (node (ref "1B1") (pin "1") (pinfunction "P_1") (pintype "passive"))
      (node (ref "R14") (pin "2") (pinfunction "2_2") (pintype "passive"))
      (node (ref "Z15") (pin "9") (pinfunction "1Y4_9") (pintype "tri_state"))
      (node (ref "Z5-6") (pin "25") (pinfunction "A3_25") (pintype "input"))
    )
    (net (code "99") (name "/VA4") (class "Default")
      (node (ref "2A1") (pin "1") (pinfunction "P_1") (pintype "passive"))
      (node (ref "R15") (pin "2") (pinfunction "2_2") (pintype "passive"))
      (node (ref "Z15") (pin "11") (pinfunction "2Y1_11") (pintype "tri_state"))
      (node (ref "Z5-6") (pin "26") (pinfunction "A4_26") (pintype "input"))
    )
    (net (code "100") (name "/VA5") (class "Default")
      (node (ref "2B1") (pin "1") (pinfunction "P_1") (pintype "passive"))
      (node (ref "R16") (pin "2") (pinfunction "2_2") (pintype "passive"))
      (node (ref "Z15") (pin "13") (pinfunction "2Y2_13") (pintype "tri_state"))
      (node (ref "Z5-6") (pin "1") (pinfunction "A5_1") (pintype "input"))
    )
    (net (code "101") (name "/VA6") (class "Default")
      (node (ref "5B2") (pin "1") (pinfunction "P_1") (pintype "passive"))
      (node (ref "R17") (pin "2") (pinfunction "2_2") (pintype "passive"))
      (node (ref "Z16") (pin "3") (pinfunction "1Y1_3") (pintype "tri_state"))
      (node (ref "Z5-6") (pin "2") (pinfunction "A6_2") (pintype "input"))
    )
    (net (code "102") (name "/VA7") (class "Default")
      (node (ref "8A1") (pin "1") (pinfunction "P_1") (pintype "passive"))
      (node (ref "R18") (pin "2") (pinfunction "2_2") (pintype "passive"))
      (node (ref "Z16") (pin "5") (pinfunction "1Y2_5") (pintype "tri_state"))
      (node (ref "Z5-6") (pin "3") (pinfunction "A7_3") (pintype "input"))
    )
    (net (code "103") (name "/VA8") (class "Default")
      (node (ref "8B2") (pin "1") (pinfunction "P_1") (pintype "passive"))
      (node (ref "R19") (pin "2") (pinfunction "2_2") (pintype "passive"))
      (node (ref "Z16") (pin "7") (pinfunction "1Y3_7") (pintype "tri_state"))
      (node (ref "Z5-6") (pin "4") (pinfunction "A8_4") (pintype "input"))
    )
    (net (code "104") (name "/VA9") (class "Default")
      (node (ref "9B1") (pin "1") (pinfunction "P_1") (pintype "passive"))
      (node (ref "R20") (pin "2") (pinfunction "2_2") (pintype "passive"))
      (node (ref "Z16") (pin "9") (pinfunction "1Y4_9") (pintype "tri_state"))
      (node (ref "Z5-6") (pin "5") (pinfunction "A9_5") (pintype "input"))
    )
    (net (code "105") (name "/VD0") (class "Default")
      (node (ref "5A1") (pin "1") (pinfunction "P_1") (pintype "passive"))
      (node (ref "R100") (pin "2") (pinfunction "2_2") (pintype "passive"))
      (node (ref "Z18") (pin "3") (pinfunction "1Y1_3") (pintype "tri_state"))
      (node (ref "Z5-6") (pin "11") (pinfunction "DQ0_11") (pintype "bidirectional"))
      (node (ref "Z7-8") (pin "25") (pinfunction "A3_25") (pintype "input"))
    )
    (net (code "106") (name "/VD1") (class "Default")
      (node (ref "4B2") (pin "1") (pinfunction "P_1") (pintype "passive"))
      (node (ref "R101") (pin "2") (pinfunction "2_2") (pintype "passive"))
      (node (ref "Z17") (pin "13") (pinfunction "2Y2_13") (pintype "tri_state"))
      (node (ref "Z5-6") (pin "12") (pinfunction "DQ1_12") (pintype "bidirectional"))
      (node (ref "Z7-8") (pin "26") (pinfunction "A4_26") (pintype "input"))
    )
    (net (code "107") (name "/VD2") (class "Default")
      (node (ref "3B1") (pin "1") (pinfunction "P_1") (pintype "passive"))
      (node (ref "R102") (pin "2") (pinfunction "2_2") (pintype "passive"))
      (node (ref "Z17") (pin "11") (pinfunction "2Y1_11") (pintype "tri_state"))
      (node (ref "Z5-6") (pin "13") (pinfunction "DQ2_13") (pintype "bidirectional"))
      (node (ref "Z7-8") (pin "1") (pinfunction "A5_1") (pintype "input"))
    )
    (net (code "108") (name "/VD3") (class "Default")
      (node (ref "3A1") (pin "1") (pinfunction "P_1") (pintype "passive"))
      (node (ref "R103") (pin "2") (pinfunction "2_2") (pintype "passive"))
      (node (ref "Z17") (pin "9") (pinfunction "1Y4_9") (pintype "tri_state"))
      (node (ref "Z5-6") (pin "15") (pinfunction "DQ3_15") (pintype "bidirectional"))
      (node (ref "Z7-8") (pin "2") (pinfunction "A6_2") (pintype "input"))
    )
    (net (code "109") (name "/VD4") (class "Default")
      (node (ref "4A1") (pin "1") (pinfunction "P_1") (pintype "passive"))
      (node (ref "R104") (pin "2") (pinfunction "2_2") (pintype "passive"))
      (node (ref "Z17") (pin "7") (pinfunction "1Y3_7") (pintype "tri_state"))
      (node (ref "Z5-6") (pin "16") (pinfunction "DQ4_16") (pintype "bidirectional"))
      (node (ref "Z7-8") (pin "3") (pinfunction "A7_3") (pintype "input"))
    )
    (net (code "110") (name "/VD5") (class "Default")
      (node (ref "7A1") (pin "1") (pinfunction "P_1") (pintype "passive"))
      (node (ref "R105") (pin "2") (pinfunction "2_2") (pintype "passive"))
      (node (ref "Z17") (pin "5") (pinfunction "1Y2_5") (pintype "tri_state"))
      (node (ref "Z5-6") (pin "17") (pinfunction "DQ5_17") (pintype "bidirectional"))
      (node (ref "Z7-8") (pin "4") (pinfunction "A8_4") (pintype "input"))
    )
    (net (code "111") (name "/VD6") (class "Default")
      (node (ref "10B1") (pin "1") (pinfunction "P_1") (pintype "passive"))
      (node (ref "R106") (pin "2") (pinfunction "2_2") (pintype "passive"))
      (node (ref "Z17") (pin "3") (pinfunction "1Y1_3") (pintype "tri_state"))
      (node (ref "Z5-6") (pin "18") (pinfunction "DQ6_18") (pintype "bidirectional"))
      (node (ref "Z7-8") (pin "5") (pinfunction "A9_5") (pintype "input"))
    )
    (net (code "112") (name "/VD7") (class "Default")
      (node (ref "6A1") (pin "1") (pinfunction "P_1") (pintype "passive"))
      (node (ref "JP18") (pin "3") (pinfunction "3_3") (pintype "passive"))
      (node (ref "R107") (pin "2") (pinfunction "2_2") (pintype "passive"))
      (node (ref "Z20") (pin "13") (pinfunction "I1_13") (pintype "input"))
      (node (ref "Z5-6") (pin "19") (pinfunction "DQ7_19") (pintype "bidirectional"))
    )
    (net (code "113") (name "/VIDEN") (class "Default")
      (node (ref "Z19") (pin "10") (pinfunction "I1_10") (pintype "input"))
      (node (ref "Z19") (pin "5") (pinfunction "I1_5") (pintype "input"))
      (node (ref "Z20") (pin "12") (pinfunction "I0_12") (pintype "input"))
      (node (ref "Z20") (pin "6") (pinfunction "O_6") (pintype "output"))
    )
    (net (code "114") (name "/VIDEO") (class "Default")
      (node (ref "13B1") (pin "1") (pinfunction "P_1") (pintype "passive"))
      (node (ref "14B1") (pin "1") (pinfunction "P_1") (pintype "passive"))
      (node (ref "15B1") (pin "1") (pinfunction "P_1") (pintype "passive"))
      (node (ref "R34") (pin "1") (pinfunction "1_1") (pintype "passive"))
      (node (ref "SJ1") (pin "1") (pinfunction "1_1") (pintype "passive"))
      (node (ref "X2") (pin "2") (pinfunction "1_2") (pintype "passive"))
      (node (ref "X2") (pin "2@2") (pinfunction "2_2@2") (pintype "passive"))
    )
    (net (code "117") (name "/{slash}BUSAK") (class "Default")
      (node (ref "9B") (pin "1") (pinfunction "P_1") (pintype "passive"))
      (node (ref "JP9") (pin "18") (pinfunction "18_18") (pintype "passive"))
      (node (ref "Z0") (pin "23") (pinfunction "BUSAK_23") (pintype "output"))
    )
    (net (code "118") (name "/{slash}BUSRQ") (class "Default")
      (node (ref "11B") (pin "1") (pinfunction "P_1") (pintype "passive"))
      (node (ref "JP9") (pin "16") (pinfunction "16_16") (pintype "passive"))
      (node (ref "R24") (pin "1") (pinfunction "1_1") (pintype "passive"))
      (node (ref "Z0") (pin "25") (pinfunction "BUSRQ_25") (pintype "input"))
    )
    (net (code "119") (name "/{slash}HALT") (class "Default")
      (node (ref "4B") (pin "1") (pinfunction "P_1") (pintype "passive"))
      (node (ref "JP2") (pin "18") (pinfunction "18_18") (pintype "passive"))
      (node (ref "Z0") (pin "18") (pinfunction "HALT_18") (pintype "output"))
    )
    (net (code "120") (name "/{slash}INT") (class "Default")
      (node (ref "2B") (pin "1") (pinfunction "P_1") (pintype "passive"))
      (node (ref "JP2") (pin "16") (pinfunction "16_16") (pintype "passive"))
      (node (ref "Z0") (pin "16") (pinfunction "INT_16") (pintype "input"))
      (node (ref "Z19") (pin "11") (pinfunction "O_11") (pintype "output"))
    )
    (net (code "121") (name "/{slash}IORQ") (class "Default")
      (node (ref "6B") (pin "1") (pinfunction "P_1") (pintype "passive"))
      (node (ref "JP2") (pin "20") (pinfunction "20_20") (pintype "passive"))
      (node (ref "Z0") (pin "20") (pinfunction "IORQ_20") (pintype "output"))
      (node (ref "Z26") (pin "4") (pinfunction "I0_4") (pintype "input"))
    )
    (net (code "122") (name "/{slash}M1") (class "Default")
      (node (ref "13B") (pin "1") (pinfunction "P_1") (pintype "passive"))
      (node (ref "JP9") (pin "14") (pinfunction "14_14") (pintype "passive"))
      (node (ref "Z0") (pin "27") (pinfunction "M1_27") (pintype "output"))
    )
    (net (code "123") (name "/{slash}MREQ") (class "Default")
      (node (ref "5B") (pin "1") (pinfunction "P_1") (pintype "passive"))
      (node (ref "JP2") (pin "19") (pinfunction "19_19") (pintype "passive"))
      (node (ref "Z0") (pin "19") (pinfunction "MREQ_19") (pintype "output"))
      (node (ref "Z29") (pin "4") (pinfunction "G2A_4") (pintype "input"))
    )
    (net (code "124") (name "/{slash}NMI") (class "Default")
      (node (ref "3B") (pin "1") (pinfunction "P_1") (pintype "passive"))
      (node (ref "JP2") (pin "17") (pinfunction "17_17") (pintype "passive"))
      (node (ref "R39") (pin "1") (pinfunction "1_1") (pintype "passive"))
      (node (ref "Z0") (pin "17") (pinfunction "NMI_17") (pintype "input"))
    )
    (net (code "125") (name "/{slash}RD") (class "Default")
      (node (ref "7B") (pin "1") (pinfunction "P_1") (pintype "passive"))
      (node (ref "JP9") (pin "20") (pinfunction "20_20") (pintype "passive"))
      (node (ref "Z0") (pin "21") (pinfunction "RD_21") (pintype "output"))
      (node (ref "Z26") (pin "10") (pinfunction "I1_10") (pintype "input"))
      (node (ref "Z3-4") (pin "22") (pinfunction "~{OE}_22") (pintype "input"))
    )
    (net (code "126") (name "/{slash}RFSH") (class "Default")
      (node (ref "14B") (pin "1") (pinfunction "P_1") (pintype "passive"))
      (node (ref "JP9") (pin "13") (pinfunction "13_13") (pintype "passive"))
      (node (ref "Z0") (pin "28") (pinfunction "RFSH_28") (pintype "output"))
    )
    (net (code "127") (name "/{slash}VHOLD") (class "Default")
      (node (ref "Z16") (pin "15") (pinfunction "2G_15") (pintype "input"))
      (node (ref "Z19") (pin "8") (pinfunction "O_8") (pintype "output"))
      (node (ref "Z26") (pin "1") (pinfunction "I0_1") (pintype "input"))
    )
    (net (code "128") (name "/{slash}WAIT") (class "Default")
      (node (ref "10B") (pin "1") (pinfunction "P_1") (pintype "passive"))
      (node (ref "C8") (pin "1") (pinfunction "1_1") (pintype "passive"))
      (node (ref "JP9") (pin "17") (pinfunction "17_17") (pintype "passive"))
      (node (ref "Z0") (pin "24") (pinfunction "WAIT_24") (pintype "input"))
      (node (ref "Z26") (pin "3") (pinfunction "O_3") (pintype "output"))
    )
    (net (code "129") (name "/{slash}WE1") (class "Default")
      (node (ref "22A") (pin "1") (pinfunction "P_1") (pintype "passive"))
      (node (ref "7B2") (pin "1") (pinfunction "P_1") (pintype "passive"))
      (node (ref "Z26") (pin "11") (pinfunction "O_11") (pintype "output"))
      (node (ref "Z30") (pin "1") (pinfunction "I0_1") (pintype "input"))
      (node (ref "Z30") (pin "2") (pinfunction "I1_2") (pintype "input"))
      (node (ref "Z5-6") (pin "27") (pinfunction "~{WE}_27") (pintype "input"))
      (node (ref "Z7-8") (pin "27") (pinfunction "~{WE}_27") (pintype "input"))
    )
    (net (code "130") (name "/{slash}WR") (class "Default")
      (node (ref "8B") (pin "1") (pinfunction "P_1") (pintype "passive"))
      (node (ref "JP9") (pin "19") (pinfunction "19_19") (pintype "passive"))
      (node (ref "Z0") (pin "22") (pinfunction "WR_22") (pintype "output"))
      (node (ref "Z25") (pin "9") (pinfunction "I1_9") (pintype "input"))
      (node (ref "Z26") (pin "12") (pinfunction "I0_12") (pintype "input"))
      (node (ref "Z3-4") (pin "27") (pinfunction "~{WE}_27") (pintype "input"))
    )
    (net (code "131") (name "GND") (class "Default")
      (node (ref "11A1") (pin "1") (pinfunction "P_1") (pintype "passive"))
      (node (ref "13A1") (pin "1") (pinfunction "P_1") (pintype "passive"))
      (node (ref "14A1") (pin "1") (pinfunction "P_1") (pintype "passive"))
      (node (ref "15A1") (pin "1") (pinfunction "P_1") (pintype "passive"))
      (node (ref "1A") (pin "1") (pinfunction "P_1") (pintype "passive"))
      (node (ref "1B") (pin "1") (pinfunction "P_1") (pintype "passive"))
      (node (ref "26A") (pin "1") (pinfunction "P_1") (pintype "passive"))
      (node (ref "26B") (pin "1") (pinfunction "P_1") (pintype "passive"))
      (node (ref "27A") (pin "1") (pinfunction "P_1") (pintype "passive"))
      (node (ref "27B") (pin "1") (pinfunction "P_1") (pintype "passive"))
      (node (ref "28A") (pin "1") (pinfunction "P_1") (pintype "passive"))
      (node (ref "28B") (pin "1") (pinfunction "P_1") (pintype "passive"))
      (node (ref "2A") (pin "1") (pinfunction "P_1") (pintype "passive"))
      (node (ref "C10") (pin "2") (pinfunction "2_2") (pintype "passive"))
      (node (ref "C11") (pin "-") (pinfunction "-_-") (pintype "passive"))
      (node (ref "C12") (pin "-") (pinfunction "-_-") (pintype "passive"))
      (node (ref "C13") (pin "1") (pinfunction "1_1") (pintype "passive"))
      (node (ref "C14") (pin "1") (pinfunction "1_1") (pintype "passive"))
      (node (ref "C15") (pin "1") (pinfunction "1_1") (pintype "passive"))
      (node (ref "C16") (pin "1") (pinfunction "1_1") (pintype "passive"))
      (node (ref "C17") (pin "1") (pinfunction "1_1") (pintype "passive"))
      (node (ref "C18") (pin "1") (pinfunction "1_1") (pintype "passive"))
      (node (ref "C19") (pin "1") (pinfunction "1_1") (pintype "passive"))
      (node (ref "C2") (pin "2") (pinfunction "2_2") (pintype "passive"))
      (node (ref "C20") (pin "1") (pinfunction "1_1") (pintype "passive"))
      (node (ref "C21") (pin "1") (pinfunction "1_1") (pintype "passive"))
      (node (ref "C22") (pin "1") (pinfunction "1_1") (pintype "passive"))
      (node (ref "C23") (pin "1") (pinfunction "1_1") (pintype "passive"))
      (node (ref "C7") (pin "-") (pinfunction "-_-") (pintype "passive"))
      (node (ref "C8") (pin "2") (pinfunction "2_2") (pintype "passive"))
      (node (ref "C9") (pin "-") (pinfunction "-_-") (pintype "passive"))
      (node (ref "EAR") (pin "GND") (pinfunction "SLEEVE_GND") (pintype "passive"))
      (node (ref "JP11") (pin "1") (pinfunction "1_1") (pintype "passive"))
      (node (ref "JP11") (pin "3") (pinfunction "3_3") (pintype "passive"))
      (node (ref "JP11") (pin "5") (pinfunction "5_5") (pintype "passive"))
      (node (ref "JP11") (pin "7") (pinfunction "7_7") (pintype "passive"))
      (node (ref "JP11") (pin "9") (pinfunction "9_9") (pintype "passive"))
      (node (ref "JP12") (pin "1") (pinfunction "1_1") (pintype "passive"))
      (node (ref "JP12") (pin "3") (pinfunction "3_3") (pintype "passive"))
      (node (ref "JP12") (pin "5") (pinfunction "5_5") (pintype "passive"))
      (node (ref "JP12") (pin "7") (pinfunction "7_7") (pintype "passive"))
      (node (ref "JP12") (pin "9") (pinfunction "9_9") (pintype "passive"))
      (node (ref "JP6") (pin "1") (pinfunction "1_1") (pintype "passive"))
      (node (ref "JP9") (pin "12") (pinfunction "12_12") (pintype "passive"))
      (node (ref "LED1") (pin "K") (pinfunction "C_K") (pintype "passive"))
      (node (ref "LED2") (pin "K") (pinfunction "C_K") (pintype "passive"))
      (node (ref "MIC") (pin "GND") (pinfunction "SLEEVE_GND") (pintype "passive"))
      (node (ref "POWER") (pin "GND") (pinfunction "SLEEVE_GND") (pintype "passive"))
      (node (ref "Q1") (pin "3") (pinfunction "E_3") (pintype "passive"))
      (node (ref "Q3") (pin "1") (pinfunction "E_1") (pintype "passive"))
      (node (ref "R32") (pin "1") (pinfunction "1_1") (pintype "passive"))
      (node (ref "R4") (pin "E") (pinfunction "E_E") (pintype "passive"))
      (node (ref "R5") (pin "1") (pinfunction "1_1") (pintype "passive"))
      (node (ref "R6") (pin "1") (pinfunction "1_1") (pintype "passive"))
      (node (ref "S1") (pin "1") (pinfunction "1_1") (pintype "passive"))
      (node (ref "S1") (pin "2") (pinfunction "2_2") (pintype "passive"))
      (node (ref "S1") (pin "3") (pinfunction "3_3") (pintype "passive"))
      (node (ref "S2") (pin "1") (pinfunction "P_1") (pintype "passive"))
      (node (ref "U1") (pin "2") (pinfunction "GND_2") (pintype "passive"))
      (node (ref "U2") (pin "2") (pinfunction "VEE_2") (pintype "power_in"))
      (node (ref "X1") (pin "2") (pinfunction "2_2") (pintype "passive"))
      (node (ref "X2") (pin "1") (pinfunction "2_1") (pintype "passive"))
      (node (ref "Z0") (pin "29") (pinfunction "GND_29") (pintype "power_in"))
      (node (ref "Z1") (pin "1") (pinfunction "CLR_1") (pintype "input"))
      (node (ref "Z1") (pin "2") (pinfunction "D_2") (pintype "input"))
      (node (ref "Z1") (pin "3") (pinfunction "CLK_3") (pintype "input"))
      (node (ref "Z1") (pin "4") (pinfunction "PRE_4") (pintype "input"))
      (node (ref "Z1-2") (pin "14") (pinfunction "VSS_14") (pintype "power_in"))
      (node (ref "Z10") (pin "12") (pinfunction "CLR_12") (pintype "input"))
      (node (ref "Z18") (pin "15") (pinfunction "2G_15") (pintype "input"))
      (node (ref "Z23") (pin "10") (pinfunction "I1_10") (pintype "input"))
      (node (ref "Z28") (pin "1") (pinfunction "SER_1") (pintype "input"))
      (node (ref "Z28") (pin "6") (pinfunction "INH_6") (pintype "input"))
      (node (ref "Z41") (pin "12") (pinfunction "I0_12") (pintype "input"))
      (node (ref "Z41") (pin "13") (pinfunction "I1_13") (pintype "input"))
      (node (ref "Z9") (pin "12") (pinfunction "CLR_12") (pintype "input"))
      (node (ref "Z9") (pin "2") (pinfunction "CLR_2") (pintype "input"))
    )
    (net (code "132") (name "Net-(C1-Pad1)") (class "Default")
      (node (ref "C1") (pin "1") (pinfunction "1_1") (pintype "passive"))
      (node (ref "X1") (pin "3") (pinfunction "3_3") (pintype "passive"))
    )
    (net (code "133") (name "Net-(C3-Pad1)") (class "Default")
      (node (ref "C3") (pin "1") (pinfunction "1_1") (pintype "passive"))
      (node (ref "EAR") (pin "TIP") (pinfunction "TIP_TIP") (pintype "passive"))
      (node (ref "R6") (pin "2") (pinfunction "2_2") (pintype "passive"))
    )
    (net (code "134") (name "Net-(C5-Pad1)") (class "Default")
      (node (ref "C5") (pin "1") (pinfunction "1_1") (pintype "passive"))
      (node (ref "C6") (pin "1") (pinfunction "1_1") (pintype "passive"))
      (node (ref "MIC") (pin "TIP") (pinfunction "TIP_TIP") (pintype "passive"))
    )
    (net (code "135") (name "Net-(C6-Pad2)") (class "Default")
      (node (ref "C6") (pin "2") (pinfunction "2_2") (pintype "passive"))
      (node (ref "R10") (pin "1") (pinfunction "1_1") (pintype "passive"))
    )
    (net (code "136") (name "Net-(D1-PadA)") (class "Default")
      (node (ref "D1") (pin "A") (pinfunction "A_A") (pintype "passive"))
      (node (ref "R3") (pin "S") (pinfunction "S_S") (pintype "passive"))
      (node (ref "R4") (pin "A") (pinfunction "A_A") (pintype "passive"))
      (node (ref "SJ1") (pin "2") (pinfunction "2_2") (pintype "passive"))
    )
    (net (code "137") (name "Net-(JP7-Pad2)") (class "Default")
      (node (ref "JP7") (pin "2") (pinfunction "2_2") (pintype "passive"))
      (node (ref "POWER") (pin "TIP") (pinfunction "TIP_TIP") (pintype "passive"))
    )
    (net (code "138") (name "Net-(JP17-Pad1)") (class "Default")
      (node (ref "JP17") (pin "1") (pinfunction "1_1") (pintype "passive"))
      (node (ref "R23") (pin "1") (pinfunction "1_1") (pintype "passive"))
    )
    (net (code "139") (name "Net-(LED1-PadA)") (class "Default")
      (node (ref "LED1") (pin "A") (pinfunction "A_A") (pintype "passive"))
      (node (ref "R28") (pin "2") (pinfunction "2_2") (pintype "passive"))
    )
    (net (code "140") (name "Net-(LED2-PadA)") (class "Default")
      (node (ref "LED2") (pin "A") (pinfunction "A_A") (pintype "passive"))
      (node (ref "R29") (pin "1") (pinfunction "1_1") (pintype "passive"))
    )
    (net (code "141") (name "Net-(LS1-1)") (class "Default")
      (node (ref "C5") (pin "2") (pinfunction "2_2") (pintype "passive"))
      (node (ref "D2") (pin "A") (pinfunction "A_A") (pintype "passive"))
      (node (ref "LS1") (pin "-") (pinfunction "1_-") (pintype "passive"))
      (node (ref "Q3") (pin "3") (pinfunction "C_3") (pintype "passive"))
    )
    (net (code "142") (name "Net-(Q1-B)") (class "Default")
      (node (ref "C2") (pin "1") (pinfunction "1_1") (pintype "passive"))
      (node (ref "Q1") (pin "2") (pinfunction "B_2") (pintype "passive"))
      (node (ref "R2") (pin "1") (pinfunction "1_1") (pintype "passive"))
      (node (ref "X1") (pin "1") (pinfunction "1_1") (pintype "passive"))
    )
    (net (code "143") (name "Net-(Q1-C)") (class "Default")
      (node (ref "C1") (pin "2") (pinfunction "2_2") (pintype "passive"))
      (node (ref "Q1") (pin "1") (pinfunction "C_1") (pintype "passive"))
      (node (ref "R1") (pin "2") (pinfunction "2_2") (pintype "passive"))
      (node (ref "R2") (pin "2") (pinfunction "2_2") (pintype "passive"))
      (node (ref "Z23") (pin "9") (pinfunction "I0_9") (pintype "input"))
    )
    (net (code "144") (name "Net-(Q3-B)") (class "Default")
      (node (ref "Q3") (pin "2") (pinfunction "B_2") (pintype "passive"))
      (node (ref "R9") (pin "1") (pinfunction "1_1") (pintype "passive"))
    )
    (net (code "145") (name "Net-(R27-Pad2)") (class "Default")
      (node (ref "R27") (pin "2") (pinfunction "2_2") (pintype "passive"))
      (node (ref "R45") (pin "1") (pinfunction "1_1") (pintype "passive"))
      (node (ref "S1") (pin "5") (pinfunction "5_5") (pintype "passive"))
    )
    (net (code "146") (name "Net-(R43-Pad2)") (class "Default")
      (node (ref "R43") (pin "2") (pinfunction "2_2") (pintype "passive"))
      (node (ref "R47") (pin "1") (pinfunction "1_1") (pintype "passive"))
      (node (ref "S1") (pin "6") (pinfunction "6_6") (pintype "passive"))
    )
    (net (code "147") (name "Net-(R46-Pad1)") (class "Default")
      (node (ref "R46") (pin "1") (pinfunction "1_1") (pintype "passive"))
      (node (ref "R8") (pin "2") (pinfunction "2_2") (pintype "passive"))
      (node (ref "S1") (pin "4") (pinfunction "4_4") (pintype "passive"))
    )
    (net (code "148") (name "Net-(U2-IN+)") (class "Default")
      (node (ref "R4") (pin "S") (pinfunction "S_S") (pintype "passive"))
      (node (ref "U2") (pin "3") (pinfunction "IN+_3") (pintype "input"))
    )
    (net (code "149") (name "Net-(U2-IN-)") (class "Default")
      (node (ref "R32") (pin "2") (pinfunction "2_2") (pintype "passive"))
      (node (ref "R33") (pin "2") (pinfunction "2_2") (pintype "passive"))
      (node (ref "U2") (pin "4") (pinfunction "IN-_4") (pintype "input"))
    )
    (net (code "150") (name "Net-(U2-OUT)") (class "Default")
      (node (ref "R33") (pin "1") (pinfunction "1_1") (pintype "passive"))
      (node (ref "R34") (pin "2") (pinfunction "2_2") (pintype "passive"))
      (node (ref "U2") (pin "1") (pinfunction "OUT_1") (pintype "output"))
    )
    (net (code "151") (name "Net-(Z1-2-~{CE})") (class "Default")
      (node (ref "Z1-2") (pin "20") (pinfunction "~{CE}_20") (pintype "input"))
      (node (ref "Z1-2") (pin "22") (pinfunction "~{OE}/VPP_22") (pintype "input"))
      (node (ref "Z22") (pin "8") (pinfunction "O_8") (pintype "output"))
    )
    (net (code "152") (name "Net-(Z1B-CLK)") (class "Default")
      (node (ref "Z1") (pin "11") (pinfunction "CLK_11") (pintype "input"))
      (node (ref "Z41") (pin "8") (pinfunction "O_8") (pintype "output"))
    )
    (net (code "153") (name "Net-(Z1B-Q)") (class "Default")
      (node (ref "Z1") (pin "9") (pinfunction "Q_9") (pintype "output"))
      (node (ref "Z31") (pin "9") (pinfunction "I0_9") (pintype "input"))
    )
    (net (code "154") (name "Net-(Z3-4A-~{CE})") (class "Default")
      (node (ref "JP3") (pin "2") (pinfunction "2_2") (pintype "passive"))
      (node (ref "Z3-4") (pin "20") (pinfunction "~{CE}_20") (pintype "input"))
    )
    (net (code "155") (name "Net-(Z5-6A-A10)") (class "Default")
      (node (ref "JP11") (pin "2") (pinfunction "2_2") (pintype "passive"))
      (node (ref "Z5-6") (pin "6") (pinfunction "A10_6") (pintype "input"))
    )
    (net (code "156") (name "Net-(Z5-6A-A11)") (class "Default")
      (node (ref "JP11") (pin "4") (pinfunction "4_4") (pintype "passive"))
      (node (ref "Z5-6") (pin "7") (pinfunction "A11_7") (pintype "input"))
    )
    (net (code "157") (name "Net-(Z5-6A-A12)") (class "Default")
      (node (ref "JP11") (pin "6") (pinfunction "6_6") (pintype "passive"))
      (node (ref "Z5-6") (pin "8") (pinfunction "A12_8") (pintype "input"))
    )
    (net (code "158") (name "Net-(Z5-6A-A13)") (class "Default")
      (node (ref "JP11") (pin "8") (pinfunction "8_8") (pintype "passive"))
      (node (ref "Z5-6") (pin "9") (pinfunction "A13_9") (pintype "input"))
    )
    (net (code "159") (name "Net-(Z5-6A-A14)") (class "Default")
      (node (ref "JP11") (pin "10") (pinfunction "10_10") (pintype "passive"))
      (node (ref "Z5-6") (pin "10") (pinfunction "A14_10") (pintype "input"))
    )
    (net (code "160") (name "Net-(Z7-8A-A10)") (class "Default")
      (node (ref "JP12") (pin "2") (pinfunction "2_2") (pintype "passive"))
      (node (ref "Z7-8") (pin "6") (pinfunction "A10_6") (pintype "input"))
    )
    (net (code "161") (name "Net-(Z7-8A-A11)") (class "Default")
      (node (ref "JP12") (pin "4") (pinfunction "4_4") (pintype "passive"))
      (node (ref "Z7-8") (pin "7") (pinfunction "A11_7") (pintype "input"))
    )
    (net (code "162") (name "Net-(Z7-8A-A12)") (class "Default")
      (node (ref "JP12") (pin "6") (pinfunction "6_6") (pintype "passive"))
      (node (ref "Z7-8") (pin "8") (pinfunction "A12_8") (pintype "input"))
    )
    (net (code "163") (name "Net-(Z7-8A-A13)") (class "Default")
      (node (ref "JP12") (pin "8") (pinfunction "8_8") (pintype "passive"))
      (node (ref "Z7-8") (pin "9") (pinfunction "A13_9") (pintype "input"))
    )
    (net (code "164") (name "Net-(Z7-8A-A14)") (class "Default")
      (node (ref "JP12") (pin "10") (pinfunction "10_10") (pintype "passive"))
      (node (ref "Z7-8") (pin "10") (pinfunction "A14_10") (pintype "input"))
    )
    (net (code "165") (name "Net-(Z10A-CLR)") (class "Default")
      (node (ref "Z10") (pin "2") (pinfunction "CLR_2") (pintype "input"))
      (node (ref "Z21") (pin "8") (pinfunction "O_8") (pintype "output"))
    )
    (net (code "166") (name "Net-(Z11A-CLR)") (class "Default")
      (node (ref "Z11") (pin "12") (pinfunction "CLR_12") (pintype "input"))
      (node (ref "Z11") (pin "2") (pinfunction "CLR_2") (pintype "input"))
      (node (ref "Z20") (pin "3") (pinfunction "O_3") (pintype "output"))
    )
    (net (code "167") (name "Net-(Z14A-1G)") (class "Default")
      (node (ref "Z14") (pin "1") (pinfunction "1G_1") (pintype "input"))
      (node (ref "Z14") (pin "15") (pinfunction "2G_15") (pintype "input"))
      (node (ref "Z23") (pin "2") (pinfunction "I1_2") (pintype "input"))
      (node (ref "Z26") (pin "8") (pinfunction "O_8") (pintype "output"))
    )
    (net (code "168") (name "Net-(Z15A-1G)") (class "Default")
      (node (ref "D11") (pin "C") (pinfunction "C_C") (pintype "passive"))
      (node (ref "JP14") (pin "1") (pinfunction "1_1") (pintype "passive"))
      (node (ref "R26") (pin "2") (pinfunction "2_2") (pintype "passive"))
      (node (ref "Z15") (pin "1") (pinfunction "1G_1") (pintype "input"))
      (node (ref "Z15") (pin "15") (pinfunction "2G_15") (pintype "input"))
      (node (ref "Z16") (pin "1") (pinfunction "1G_1") (pintype "input"))
      (node (ref "Z16") (pin "14") (pinfunction "2A2_14") (pintype "input"))
      (node (ref "Z24") (pin "2") (pinfunction "I0_2") (pintype "input"))
      (node (ref "Z24") (pin "5") (pinfunction "I0_5") (pintype "input"))
      (node (ref "Z26") (pin "13") (pinfunction "I1_13") (pintype "input"))
    )
    (net (code "169") (name "Net-(Z16A-2Y2)") (class "Default")
      (node (ref "D11") (pin "A") (pinfunction "A_A") (pintype "passive"))
      (node (ref "Z16") (pin "13") (pinfunction "2Y2_13") (pintype "tri_state"))
    )
    (net (code "170") (name "Net-(Z17A-1G)") (class "Default")
      (node (ref "Z17") (pin "1") (pinfunction "1G_1") (pintype "input"))
      (node (ref "Z17") (pin "15") (pinfunction "2G_15") (pintype "input"))
      (node (ref "Z18") (pin "1") (pinfunction "1G_1") (pintype "input"))
      (node (ref "Z23") (pin "6") (pinfunction "O_6") (pintype "output"))
    )
    (net (code "171") (name "Net-(Z18A-1Y2)") (class "Default")
      (node (ref "R23") (pin "2") (pinfunction "2_2") (pintype "passive"))
      (node (ref "Z18") (pin "5") (pinfunction "1Y2_5") (pintype "tri_state"))
      (node (ref "Z7-8") (pin "24") (pinfunction "A2_24") (pintype "input"))
    )
    (net (code "172") (name "Net-(Z18A-1Y3)") (class "Default")
      (node (ref "R22") (pin "2") (pinfunction "2_2") (pintype "passive"))
      (node (ref "Z18") (pin "7") (pinfunction "1Y3_7") (pintype "tri_state"))
      (node (ref "Z7-8") (pin "23") (pinfunction "A1_23") (pintype "input"))
    )
    (net (code "173") (name "Net-(Z18A-1Y4)") (class "Default")
      (node (ref "R21") (pin "2") (pinfunction "2_2") (pintype "passive"))
      (node (ref "Z18") (pin "9") (pinfunction "1Y4_9") (pintype "tri_state"))
      (node (ref "Z7-8") (pin "21") (pinfunction "A0_21") (pintype "input"))
    )
    (net (code "174") (name "Net-(Z18A-2A2)") (class "Default")
      (node (ref "C3") (pin "2") (pinfunction "2_2") (pintype "passive"))
      (node (ref "R5") (pin "2") (pinfunction "2_2") (pintype "passive"))
      (node (ref "R7") (pin "1") (pinfunction "1_1") (pintype "passive"))
      (node (ref "Z18") (pin "14") (pinfunction "2A2_14") (pintype "input"))
    )
    (net (code "175") (name "Net-(Z19A-O)") (class "Default")
      (node (ref "Z19") (pin "3") (pinfunction "O_3") (pintype "output"))
      (node (ref "Z20") (pin "4") (pinfunction "I0_4") (pintype "input"))
    )
    (net (code "176") (name "Net-(Z19B-I0)") (class "Default")
      (node (ref "Z19") (pin "4") (pinfunction "I0_4") (pintype "input"))
      (node (ref "Z20") (pin "9") (pinfunction "I0_9") (pintype "input"))
      (node (ref "Z22") (pin "6") (pinfunction "O_6") (pintype "output"))
    )
    (net (code "177") (name "Net-(Z19B-O)") (class "Default")
      (node (ref "Z19") (pin "6") (pinfunction "O_6") (pintype "output"))
      (node (ref "Z28") (pin "15") (pinfunction "SH/~{LD}_15") (pintype "input"))
    )
    (net (code "178") (name "Net-(Z20A-I0)") (class "Default")
      (node (ref "Z20") (pin "1") (pinfunction "I0_1") (pintype "input"))
      (node (ref "Z21") (pin "13") (pinfunction "I2_13") (pintype "input"))
      (node (ref "Z21") (pin "6") (pinfunction "O_6") (pintype "output"))
    )
    (net (code "179") (name "Net-(Z20B-I1)") (class "Default")
      (node (ref "Z20") (pin "5") (pinfunction "I1_5") (pintype "input"))
      (node (ref "Z25") (pin "1") (pinfunction "O_1") (pintype "output"))
    )
    (net (code "180") (name "Net-(Z20C-O)") (class "Default")
      (node (ref "Z20") (pin "8") (pinfunction "O_8") (pintype "output"))
      (node (ref "Z27") (pin "11") (pinfunction "CLK_11") (pintype "input"))
    )
    (net (code "181") (name "Net-(Z20D-O)") (class "Default")
      (node (ref "Z20") (pin "11") (pinfunction "O_11") (pintype "output"))
      (node (ref "Z27") (pin "12") (pinfunction "D_12") (pintype "input"))
    )
    (net (code "182") (name "Net-(Z22A-I1)") (class "Default")
      (node (ref "Z22") (pin "2") (pinfunction "I1_2") (pintype "input"))
      (node (ref "Z25") (pin "13") (pinfunction "O_13") (pintype "output"))
    )
    (net (code "183") (name "Net-(Z22C-I0)") (class "Default")
      (node (ref "Z22") (pin "9") (pinfunction "I0_9") (pintype "input"))
      (node (ref "Z29") (pin "15") (pinfunction "Y0_15") (pintype "output"))
    )
    (net (code "184") (name "Net-(Z22C-I1)") (class "Default")
      (node (ref "Z22") (pin "10") (pinfunction "I1_10") (pintype "input"))
      (node (ref "Z29") (pin "14") (pinfunction "Y1_14") (pintype "output"))
    )
    (net (code "185") (name "Net-(Z23A-O)") (class "Default")
      (node (ref "Z23") (pin "3") (pinfunction "O_3") (pintype "output"))
      (node (ref "Z24") (pin "12") (pinfunction "I1_12") (pintype "input"))
    )
    (net (code "186") (name "Net-(Z23B-I0)") (class "Default")
      (node (ref "Z23") (pin "4") (pinfunction "I0_4") (pintype "input"))
      (node (ref "Z24") (pin "1") (pinfunction "O_1") (pintype "output"))
      (node (ref "Z5-6") (pin "20") (pinfunction "~{CE}_20") (pintype "input"))
    )
    (net (code "187") (name "Net-(Z23D-I0)") (class "Default")
      (node (ref "JP4") (pin "2") (pinfunction "2_2") (pintype "passive"))
      (node (ref "Z23") (pin "12") (pinfunction "I0_12") (pintype "input"))
    )
    (net (code "188") (name "Net-(Z23D-I1)") (class "Default")
      (node (ref "Z23") (pin "13") (pinfunction "I1_13") (pintype "input"))
      (node (ref "Z28") (pin "13") (pinfunction "QH_13") (pintype "output"))
    )
    (net (code "189") (name "Net-(Z23D-O)") (class "Default")
      (node (ref "R35") (pin "2") (pinfunction "2_2") (pintype "passive"))
      (node (ref "Z23") (pin "11") (pinfunction "O_11") (pintype "output"))
    )
    (net (code "190") (name "Net-(Z24A-I1)") (class "Default")
      (node (ref "Z24") (pin "3") (pinfunction "I1_3") (pintype "input"))
      (node (ref "Z24") (pin "4") (pinfunction "O_4") (pintype "output"))
      (node (ref "Z7-8") (pin "20") (pinfunction "~{CE}_20") (pintype "input"))
    )
    (net (code "191") (name "Net-(Z24C-I0)") (class "Default")
      (node (ref "Z24") (pin "8") (pinfunction "I0_8") (pintype "input"))
      (node (ref "Z25") (pin "10") (pinfunction "O_10") (pintype "output"))
      (node (ref "Z27") (pin "3") (pinfunction "CLK_3") (pintype "input"))
    )
    (net (code "192") (name "Net-(Z24C-I1)") (class "Default")
      (node (ref "R9") (pin "2") (pinfunction "2_2") (pintype "passive"))
      (node (ref "Z24") (pin "13") (pinfunction "O_13") (pintype "output"))
      (node (ref "Z24") (pin "9") (pinfunction "I1_9") (pintype "input"))
    )
    (net (code "193") (name "Net-(Z24C-O)") (class "Default")
      (node (ref "Z24") (pin "10") (pinfunction "O_10") (pintype "output"))
      (node (ref "Z24") (pin "11") (pinfunction "I0_11") (pintype "input"))
    )
    (net (code "194") (name "Net-(Z25C-I0)") (class "Default")
      (node (ref "Z25") (pin "8") (pinfunction "I0_8") (pintype "input"))
      (node (ref "Z26") (pin "6") (pinfunction "O_6") (pintype "output"))
      (node (ref "Z26") (pin "9") (pinfunction "I0_9") (pintype "input"))
    )
    (net (code "195") (name "Net-(Z26A-I1)") (class "Default")
      (node (ref "R26") (pin "1") (pinfunction "1_1") (pintype "passive"))
      (node (ref "Z26") (pin "2") (pinfunction "I1_2") (pintype "input"))
      (node (ref "Z29") (pin "13") (pinfunction "Y2_13") (pintype "output"))
    )
    (net (code "196") (name "Net-(Z27A-Q)") (class "Default")
      (node (ref "R10") (pin "2") (pinfunction "2_2") (pintype "passive"))
      (node (ref "Z27") (pin "5") (pinfunction "Q_5") (pintype "output"))
    )
    (net (code "197") (name "Net-(Z27B-~{Q})") (class "Default")
      (node (ref "JP4") (pin "3") (pinfunction "3_3") (pintype "passive"))
      (node (ref "Z27") (pin "8") (pinfunction "~{Q}_8") (pintype "output"))
    )
    (net (code "198") (name "Net-(Z28A-A)") (class "Default")
      (node (ref "R200") (pin "2") (pinfunction "2_2") (pintype "passive"))
      (node (ref "Z28") (pin "2") (pinfunction "A_2") (pintype "input"))
      (node (ref "Z7-8") (pin "11") (pinfunction "DQ0_11") (pintype "bidirectional"))
    )
    (net (code "199") (name "Net-(Z28A-B)") (class "Default")
      (node (ref "R201") (pin "2") (pinfunction "2_2") (pintype "passive"))
      (node (ref "Z28") (pin "3") (pinfunction "B_3") (pintype "input"))
      (node (ref "Z7-8") (pin "12") (pinfunction "DQ1_12") (pintype "bidirectional"))
    )
    (net (code "200") (name "Net-(Z28A-C)") (class "Default")
      (node (ref "R202") (pin "2") (pinfunction "2_2") (pintype "passive"))
      (node (ref "Z28") (pin "4") (pinfunction "C_4") (pintype "input"))
      (node (ref "Z7-8") (pin "13") (pinfunction "DQ2_13") (pintype "bidirectional"))
    )
    (net (code "201") (name "Net-(Z28A-CLK)") (class "Default")
      (node (ref "C23") (pin "2") (pinfunction "2_2") (pintype "passive"))
      (node (ref "R44") (pin "A") (pinfunction "A_A") (pintype "passive"))
      (node (ref "Z28") (pin "7") (pinfunction "CLK_7") (pintype "input"))
    )
    (net (code "202") (name "Net-(Z28A-D)") (class "Default")
      (node (ref "R203") (pin "2") (pinfunction "2_2") (pintype "passive"))
      (node (ref "Z28") (pin "5") (pinfunction "D_5") (pintype "input"))
      (node (ref "Z7-8") (pin "15") (pinfunction "DQ3_15") (pintype "bidirectional"))
    )
    (net (code "203") (name "Net-(Z28A-E)") (class "Default")
      (node (ref "R204") (pin "2") (pinfunction "2_2") (pintype "passive"))
      (node (ref "Z28") (pin "10") (pinfunction "E_10") (pintype "input"))
      (node (ref "Z7-8") (pin "16") (pinfunction "DQ4_16") (pintype "bidirectional"))
    )
    (net (code "204") (name "Net-(Z28A-F)") (class "Default")
      (node (ref "R205") (pin "2") (pinfunction "2_2") (pintype "passive"))
      (node (ref "Z28") (pin "11") (pinfunction "F_11") (pintype "input"))
      (node (ref "Z7-8") (pin "17") (pinfunction "DQ5_17") (pintype "bidirectional"))
    )
    (net (code "205") (name "Net-(Z28A-G)") (class "Default")
      (node (ref "R206") (pin "2") (pinfunction "2_2") (pintype "passive"))
      (node (ref "Z28") (pin "12") (pinfunction "G_12") (pintype "input"))
      (node (ref "Z7-8") (pin "18") (pinfunction "DQ6_18") (pintype "bidirectional"))
    )
    (net (code "206") (name "Net-(Z28A-H)") (class "Default")
      (node (ref "R207") (pin "2") (pinfunction "2_2") (pintype "passive"))
      (node (ref "Z28") (pin "14") (pinfunction "H_14") (pintype "input"))
      (node (ref "Z7-8") (pin "19") (pinfunction "DQ7_19") (pintype "bidirectional"))
    )
    (net (code "207") (name "Net-(Z29A-Y3)") (class "Default")
      (node (ref "JP3") (pin "1") (pinfunction "1_1") (pintype "passive"))
      (node (ref "Z29") (pin "12") (pinfunction "Y3_12") (pintype "output"))
      (node (ref "Z31") (pin "3") (pinfunction "I0_3") (pintype "input"))
    )
    (net (code "208") (name "Net-(Z29A-Y4)") (class "Default")
      (node (ref "Z29") (pin "11") (pinfunction "Y4_11") (pintype "output"))
      (node (ref "Z31") (pin "4") (pinfunction "I1_4") (pintype "input"))
    )
    (net (code "209") (name "Net-(Z29A-Y5)") (class "Default")
      (node (ref "Z29") (pin "10") (pinfunction "Y5_10") (pintype "output"))
      (node (ref "Z31") (pin "5") (pinfunction "I2_5") (pintype "input"))
    )
    (net (code "210") (name "Net-(Z29A-Y6)") (class "Default")
      (node (ref "Z29") (pin "9") (pinfunction "Y6_9") (pintype "output"))
      (node (ref "Z31") (pin "2") (pinfunction "I1_2") (pintype "input"))
    )
    (net (code "211") (name "Net-(Z29A-Y7)") (class "Default")
      (node (ref "Z29") (pin "7") (pinfunction "Y7_7") (pintype "output"))
      (node (ref "Z31") (pin "13") (pinfunction "I2_13") (pintype "input"))
    )
    (net (code "212") (name "Net-(Z30A-O)") (class "Default")
      (node (ref "Z30") (pin "3") (pinfunction "O_3") (pintype "output"))
      (node (ref "Z5-6") (pin "22") (pinfunction "~{OE}_22") (pintype "input"))
      (node (ref "Z7-8") (pin "22") (pinfunction "~{OE}_22") (pintype "input"))
    )
    (net (code "213") (name "Net-(Z31A-I0)") (class "Default")
      (node (ref "Z31") (pin "1") (pinfunction "I0_1") (pintype "input"))
      (node (ref "Z31") (pin "6") (pinfunction "O_6") (pintype "output"))
    )
    (net (code "214") (name "Net-(Z31A-O)") (class "Default")
      (node (ref "JP3") (pin "3") (pinfunction "3_3") (pintype "passive"))
      (node (ref "Z31") (pin "12") (pinfunction "O_12") (pintype "output"))
    )
    (net (code "215") (name "Net-(Z31C-I1)") (class "Default")
      (node (ref "R35") (pin "1") (pinfunction "1_1") (pintype "passive"))
      (node (ref "Z31") (pin "10") (pinfunction "I1_10") (pintype "input"))
    )
    (net (code "216") (name "Net-(Z31C-O)") (class "Default")
      (node (ref "R3") (pin "A") (pinfunction "A_A") (pintype "passive"))
      (node (ref "Z31") (pin "8") (pinfunction "O_8") (pintype "output"))
    )
    (net (code "217") (name "Net-(Z41A-O)") (class "Default")
      (node (ref "Z41") (pin "3") (pinfunction "O_3") (pintype "output"))
      (node (ref "Z41") (pin "4") (pinfunction "I0_4") (pintype "input"))
    )
    (net (code "218") (name "Net-(Z41B-O)") (class "Default")
      (node (ref "Z41") (pin "10") (pinfunction "I1_10") (pintype "input"))
      (node (ref "Z41") (pin "6") (pinfunction "O_6") (pintype "output"))
    )
    (net (code "219") (name "VCC") (class "Default")
      (node (ref "11B1") (pin "1") (pinfunction "P_1") (pintype "passive"))
      (node (ref "4A") (pin "1") (pinfunction "P_1") (pintype "passive"))
      (node (ref "C12") (pin "+") (pinfunction "+_+") (pintype "passive"))
      (node (ref "C13") (pin "2") (pinfunction "2_2") (pintype "passive"))
      (node (ref "C14") (pin "2") (pinfunction "2_2") (pintype "passive"))
      (node (ref "C15") (pin "2") (pinfunction "2_2") (pintype "passive"))
      (node (ref "C16") (pin "2") (pinfunction "2_2") (pintype "passive"))
      (node (ref "C17") (pin "2") (pinfunction "2_2") (pintype "passive"))
      (node (ref "C18") (pin "2") (pinfunction "2_2") (pintype "passive"))
      (node (ref "C19") (pin "2") (pinfunction "2_2") (pintype "passive"))
      (node (ref "C20") (pin "2") (pinfunction "2_2") (pintype "passive"))
      (node (ref "C21") (pin "2") (pinfunction "2_2") (pintype "passive"))
      (node (ref "D2") (pin "C") (pinfunction "C_C") (pintype "passive"))
      (node (ref "JP2") (pin "11") (pinfunction "11_11") (pintype "passive"))
      (node (ref "JP8") (pin "1") (pinfunction "1_1") (pintype "passive"))
      (node (ref "JP8") (pin "2") (pinfunction "2_2") (pintype "passive"))
      (node (ref "LS1") (pin "+") (pinfunction "2_+") (pintype "passive"))
      (node (ref "R1") (pin "1") (pinfunction "1_1") (pintype "passive"))
      (node (ref "R24") (pin "2") (pinfunction "2_2") (pintype "passive"))
      (node (ref "R25") (pin "2") (pinfunction "2_2") (pintype "passive"))
      (node (ref "R27") (pin "1") (pinfunction "1_1") (pintype "passive"))
      (node (ref "R28") (pin "1") (pinfunction "1_1") (pintype "passive"))
      (node (ref "R3") (pin "E") (pinfunction "E_E") (pintype "passive"))
      (node (ref "R36") (pin "2") (pinfunction "2_2") (pintype "passive"))
      (node (ref "R37") (pin "2") (pinfunction "2_2") (pintype "passive"))
      (node (ref "R38") (pin "2") (pinfunction "2_2") (pintype "passive"))
      (node (ref "R39") (pin "2") (pinfunction "2_2") (pintype "passive"))
      (node (ref "R40") (pin "2") (pinfunction "2_2") (pintype "passive"))
      (node (ref "R41") (pin "2") (pinfunction "2_2") (pintype "passive"))
      (node (ref "R43") (pin "1") (pinfunction "1_1") (pintype "passive"))
      (node (ref "R7") (pin "2") (pinfunction "2_2") (pintype "passive"))
      (node (ref "R8") (pin "1") (pinfunction "1_1") (pintype "passive"))
      (node (ref "RN1") (pin "1") (pinfunction "1_1") (pintype "passive"))
      (node (ref "U1") (pin "3") (pinfunction "VO_3") (pintype "passive"))
      (node (ref "U2") (pin "5") (pinfunction "VCC_5") (pintype "power_in"))
      (node (ref "Z0") (pin "11") (pinfunction "VCC_11") (pintype "power_in"))
      (node (ref "Z1") (pin "10") (pinfunction "PRE_10") (pintype "input"))
      (node (ref "Z1") (pin "12") (pinfunction "D_12") (pintype "input"))
      (node (ref "Z1-2") (pin "28") (pinfunction "VCC_28") (pintype "power_in"))
      (node (ref "Z16") (pin "12") (pinfunction "2A1_12") (pintype "input"))
      (node (ref "Z18") (pin "12") (pinfunction "2A1_12") (pintype "input"))
      (node (ref "Z19") (pin "13") (pinfunction "I1_13") (pintype "input"))
      (node (ref "Z22") (pin "11") (pinfunction "I2_11") (pintype "input"))
      (node (ref "Z23") (pin "1") (pinfunction "I0_1") (pintype "input"))
      (node (ref "Z23") (pin "5") (pinfunction "I1_5") (pintype "input"))
      (node (ref "Z27") (pin "1") (pinfunction "CLR_1") (pintype "input"))
      (node (ref "Z27") (pin "10") (pinfunction "PRE_10") (pintype "input"))
      (node (ref "Z27") (pin "13") (pinfunction "CLR_13") (pintype "input"))
      (node (ref "Z27") (pin "4") (pinfunction "PRE_4") (pintype "input"))
      (node (ref "Z28") (pin "9") (pinfunction "CLR_9") (pintype "input"))
      (node (ref "Z29") (pin "6") (pinfunction "G1_6") (pintype "input"))
      (node (ref "Z31") (pin "11") (pinfunction "I2_11") (pintype "input"))
      (node (ref "Z41") (pin "1") (pinfunction "I0_1") (pintype "input"))
      (node (ref "Z41") (pin "9") (pinfunction "I0_9") (pintype "input"))
    )
    (net (code "220") (name "unconnected-(10A1-P-Pad1)") (class "Default")
      (node (ref "10A1") (pin "1") (pinfunction "P_1") (pintype "passive"))
    )
    (net (code "221") (name "unconnected-(EAR-SWITCH-PadSW)") (class "Default")
      (node (ref "EAR") (pin "SW") (pinfunction "SWITCH_SW") (pintype "passive"))
    )
    (net (code "222") (name "unconnected-(JP7-Pad3)") (class "Default")
      (node (ref "JP7") (pin "3") (pinfunction "3_3") (pintype "passive"))
    )
    (net (code "223") (name "unconnected-(MIC-SWITCH-PadSW)") (class "Default")
      (node (ref "MIC") (pin "SW") (pinfunction "SWITCH_SW") (pintype "passive"))
    )
    (net (code "224") (name "unconnected-(POWER-SWITCH-PadSW)") (class "Default")
      (node (ref "POWER") (pin "SW") (pinfunction "SWITCH_SW") (pintype "passive"))
    )
    (net (code "225") (name "unconnected-(Z1A-Q-Pad5)") (class "Default")
      (node (ref "Z1") (pin "5") (pinfunction "Q_5") (pintype "output"))
    )
    (net (code "226") (name "unconnected-(Z1A-~{Q}-Pad6)") (class "Default")
      (node (ref "Z1") (pin "6") (pinfunction "~{Q}_6") (pintype "output"))
    )
    (net (code "227") (name "unconnected-(Z1B-~{Q}-Pad8)") (class "Default")
      (node (ref "Z1") (pin "8") (pinfunction "~{Q}_8") (pintype "output"))
    )
    (net (code "228") (name "unconnected-(Z9B-QB-Pad10)") (class "Default")
      (node (ref "Z9") (pin "10") (pinfunction "QB_10") (pintype "output"))
    )
    (net (code "229") (name "unconnected-(Z9B-QC-Pad9)") (class "Default")
      (node (ref "Z9") (pin "9") (pinfunction "QC_9") (pintype "output"))
    )
    (net (code "230") (name "unconnected-(Z9B-QD-Pad8)") (class "Default")
      (node (ref "Z9") (pin "8") (pinfunction "QD_8") (pintype "output"))
    )
    (net (code "231") (name "unconnected-(Z10B-QD-Pad8)") (class "Default")
      (node (ref "Z10") (pin "8") (pinfunction "QD_8") (pintype "output"))
    )
    (net (code "232") (name "unconnected-(Z11B-QC-Pad9)") (class "Default")
      (node (ref "Z11") (pin "9") (pinfunction "QC_9") (pintype "output"))
    )
    (net (code "233") (name "unconnected-(Z11B-QD-Pad8)") (class "Default")
      (node (ref "Z11") (pin "8") (pinfunction "QD_8") (pintype "output"))
    )
    (net (code "234") (name "unconnected-(Z16A-2Y1-Pad11)") (class "Default")
      (node (ref "Z16") (pin "11") (pinfunction "2Y1_11") (pintype "tri_state"))
    )
    (net (code "235") (name "unconnected-(Z18A-2Y1-Pad11)") (class "Default")
      (node (ref "Z18") (pin "11") (pinfunction "2Y1_11") (pintype "tri_state"))
    )
    (net (code "236") (name "unconnected-(Z27A-~{Q}-Pad6)") (class "Default")
      (node (ref "Z27") (pin "6") (pinfunction "~{Q}_6") (pintype "output"))
    )
    (net (code "237") (name "unconnected-(Z41D-O-Pad11)") (class "Default")
      (node (ref "Z41") (pin "11") (pinfunction "O_11") (pintype "output"))
    )
  )
)
